# GD2.net
KiCad netlist of a schematic drawn in Altium Designer
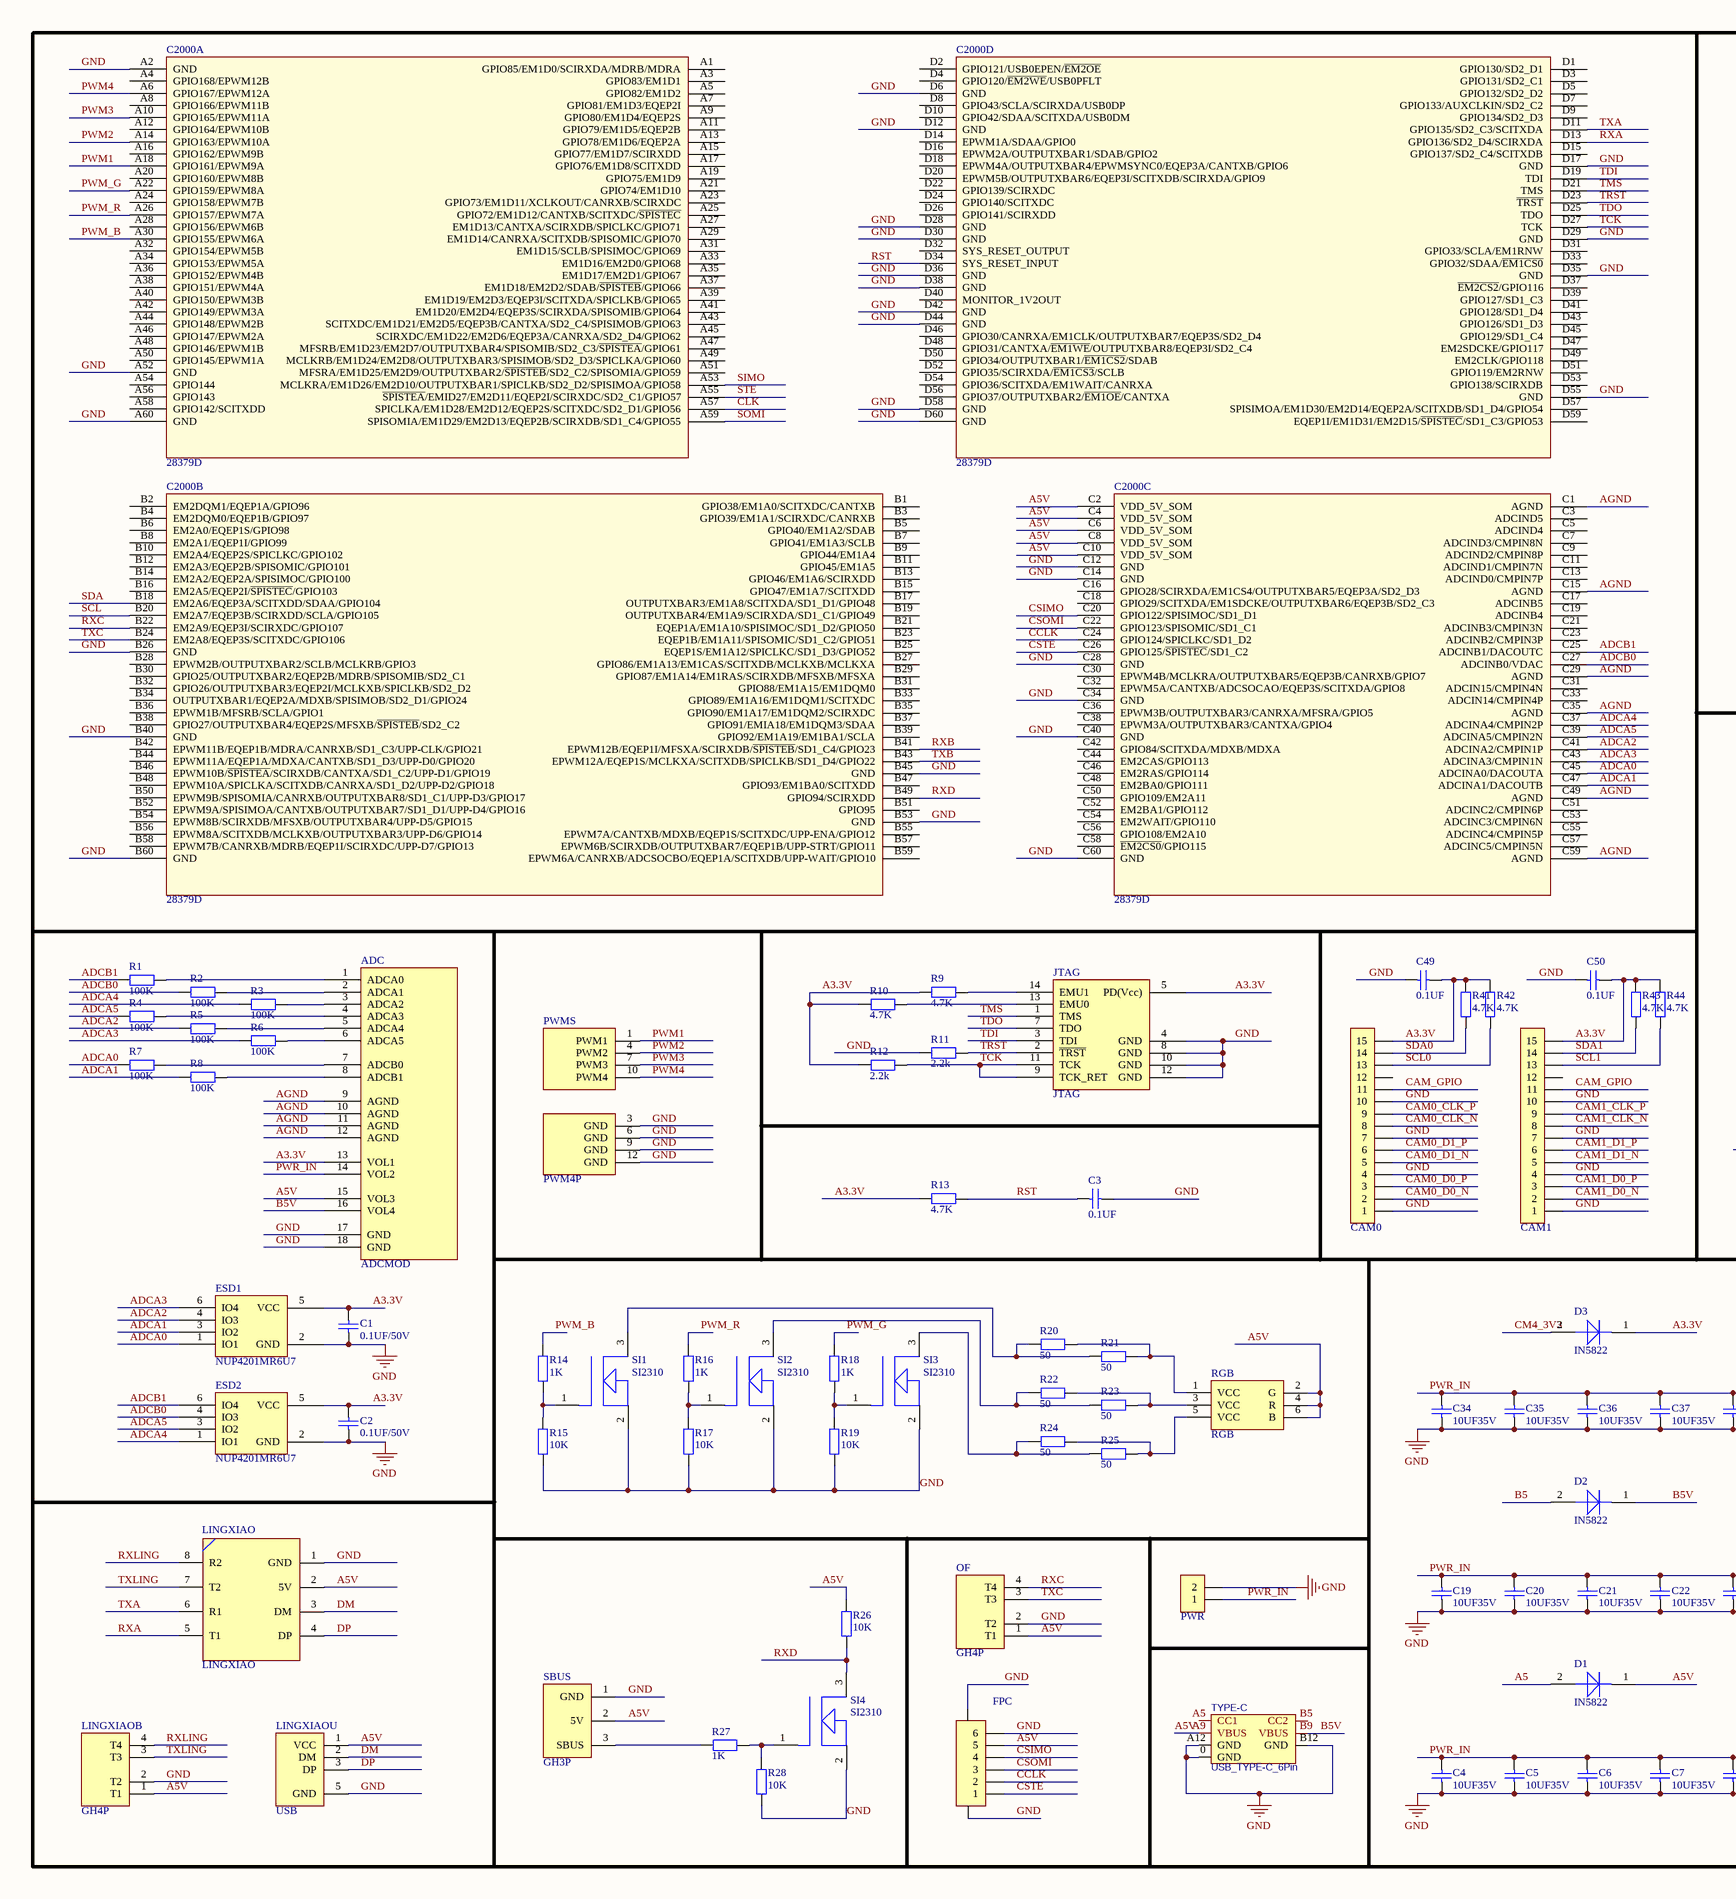
[diagram p0: GD2.SchDoc, left]
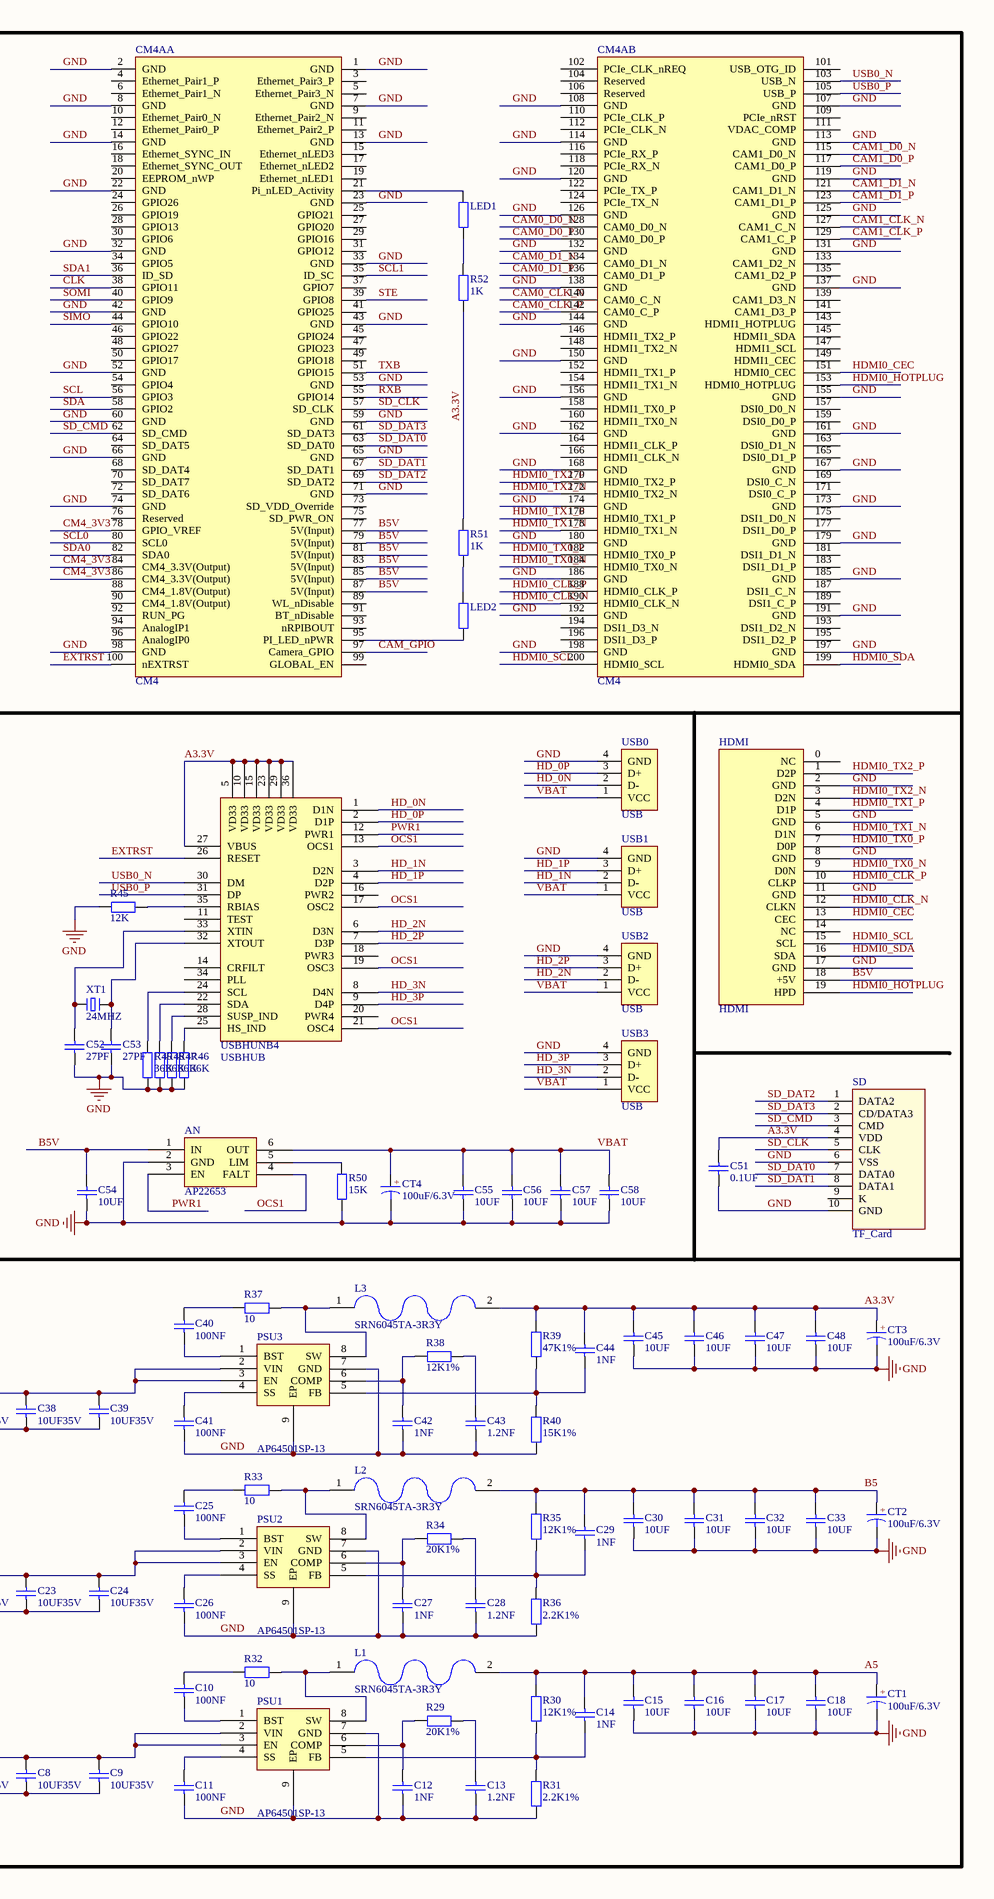
[diagram p1: GD2.SchDoc, right]

(export (version "E")
  (design (tool "Eeschema 10.0.6"))
  (components
    (comp (ref "ADC") (value "ADCMOD") (footprint "ADCMOD") (libsource (lib "LINGXIAO") (part "ADCMOD")))
    (comp (ref "AN") (value "AP22653") (footprint "SOT23-6") (libsource (lib "LINGXIAO") (part "AP22653")))
    (comp (ref "C1")
      (value "0.1UF/50V")
      (footprint "C0603_L")
      (description "贴片电容/MLCC电容")
      (libsource (lib "0.1 - 电阻-电容-电感-晶振-晶体-磁珠-电位器-法拉电容-馈通电容") (part "C"))
    )
    (comp (ref "C2")
      (value "0.1UF/50V")
      (footprint "C0603_L")
      (description "贴片电容/MLCC电容")
      (libsource (lib "0.1 - 电阻-电容-电感-晶振-晶体-磁珠-电位器-法拉电容-馈通电容") (part "C"))
    )
    (comp (ref "C3")
      (value "0.1UF")
      (footprint "C0603_L")
      (description "贴片电容/MLCC电容")
      (libsource (lib "0.1 - 电阻-电容-电感-晶振-晶体-磁珠-电位器-法拉电容-馈通电容") (part "C"))
    )
    (comp (ref "C4")
      (value "10UF35V")
      (footprint "C0603_L")
      (description "贴片电容/MLCC电容")
      (libsource (lib "0.1 - 电阻-电容-电感-晶振-晶体-磁珠-电位器-法拉电容-馈通电容") (part "C"))
    )
    (comp (ref "C5")
      (value "10UF35V")
      (footprint "C0603_L")
      (description "贴片电容/MLCC电容")
      (libsource (lib "0.1 - 电阻-电容-电感-晶振-晶体-磁珠-电位器-法拉电容-馈通电容") (part "C"))
    )
    (comp (ref "C6")
      (value "10UF35V")
      (footprint "C0603_L")
      (description "贴片电容/MLCC电容")
      (libsource (lib "0.1 - 电阻-电容-电感-晶振-晶体-磁珠-电位器-法拉电容-馈通电容") (part "C"))
    )
    (comp (ref "C7")
      (value "10UF35V")
      (footprint "C0603_L")
      (description "贴片电容/MLCC电容")
      (libsource (lib "0.1 - 电阻-电容-电感-晶振-晶体-磁珠-电位器-法拉电容-馈通电容") (part "C"))
    )
    (comp (ref "C8")
      (value "10UF35V")
      (footprint "C0603_L")
      (description "贴片电容/MLCC电容")
      (libsource (lib "0.1 - 电阻-电容-电感-晶振-晶体-磁珠-电位器-法拉电容-馈通电容") (part "C"))
    )
    (comp (ref "C9")
      (value "10UF35V")
      (footprint "C0603_L")
      (description "贴片电容/MLCC电容")
      (libsource (lib "0.1 - 电阻-电容-电感-晶振-晶体-磁珠-电位器-法拉电容-馈通电容") (part "C"))
    )
    (comp (ref "C10")
      (value "100NF")
      (footprint "C0603_L")
      (description "贴片电容/MLCC电容")
      (libsource (lib "0.1 - 电阻-电容-电感-晶振-晶体-磁珠-电位器-法拉电容-馈通电容") (part "C"))
    )
    (comp (ref "C11")
      (value "100NF")
      (footprint "C0603_L")
      (description "贴片电容/MLCC电容")
      (libsource (lib "0.1 - 电阻-电容-电感-晶振-晶体-磁珠-电位器-法拉电容-馈通电容") (part "C"))
    )
    (comp (ref "C12")
      (value "1NF")
      (footprint "C0603_L")
      (description "贴片电容/MLCC电容")
      (libsource (lib "0.1 - 电阻-电容-电感-晶振-晶体-磁珠-电位器-法拉电容-馈通电容") (part "C"))
    )
    (comp (ref "C13")
      (value "1.2NF")
      (footprint "C0603_L")
      (description "贴片电容/MLCC电容")
      (libsource (lib "0.1 - 电阻-电容-电感-晶振-晶体-磁珠-电位器-法拉电容-馈通电容") (part "C"))
    )
    (comp (ref "C14")
      (value "1NF")
      (footprint "C0603_L")
      (description "贴片电容/MLCC电容")
      (libsource (lib "0.1 - 电阻-电容-电感-晶振-晶体-磁珠-电位器-法拉电容-馈通电容") (part "C"))
    )
    (comp (ref "C15")
      (value "10UF")
      (footprint "C0603_L")
      (description "贴片电容/MLCC电容")
      (libsource (lib "0.1 - 电阻-电容-电感-晶振-晶体-磁珠-电位器-法拉电容-馈通电容") (part "C"))
    )
    (comp (ref "C16")
      (value "10UF")
      (footprint "C0603_L")
      (description "贴片电容/MLCC电容")
      (libsource (lib "0.1 - 电阻-电容-电感-晶振-晶体-磁珠-电位器-法拉电容-馈通电容") (part "C"))
    )
    (comp (ref "C17")
      (value "10UF")
      (footprint "C0603_L")
      (description "贴片电容/MLCC电容")
      (libsource (lib "0.1 - 电阻-电容-电感-晶振-晶体-磁珠-电位器-法拉电容-馈通电容") (part "C"))
    )
    (comp (ref "C18")
      (value "10UF")
      (footprint "C0603_L")
      (description "贴片电容/MLCC电容")
      (libsource (lib "0.1 - 电阻-电容-电感-晶振-晶体-磁珠-电位器-法拉电容-馈通电容") (part "C"))
    )
    (comp (ref "C19")
      (value "10UF35V")
      (footprint "C0603_L")
      (description "贴片电容/MLCC电容")
      (libsource (lib "0.1 - 电阻-电容-电感-晶振-晶体-磁珠-电位器-法拉电容-馈通电容") (part "C"))
    )
    (comp (ref "C20")
      (value "10UF35V")
      (footprint "C0603_L")
      (description "贴片电容/MLCC电容")
      (libsource (lib "0.1 - 电阻-电容-电感-晶振-晶体-磁珠-电位器-法拉电容-馈通电容") (part "C"))
    )
    (comp (ref "C21")
      (value "10UF35V")
      (footprint "C0603_L")
      (description "贴片电容/MLCC电容")
      (libsource (lib "0.1 - 电阻-电容-电感-晶振-晶体-磁珠-电位器-法拉电容-馈通电容") (part "C"))
    )
    (comp (ref "C22")
      (value "10UF35V")
      (footprint "C0603_L")
      (description "贴片电容/MLCC电容")
      (libsource (lib "0.1 - 电阻-电容-电感-晶振-晶体-磁珠-电位器-法拉电容-馈通电容") (part "C"))
    )
    (comp (ref "C23")
      (value "10UF35V")
      (footprint "C0603_L")
      (description "贴片电容/MLCC电容")
      (libsource (lib "0.1 - 电阻-电容-电感-晶振-晶体-磁珠-电位器-法拉电容-馈通电容") (part "C"))
    )
    (comp (ref "C24")
      (value "10UF35V")
      (footprint "C0603_L")
      (description "贴片电容/MLCC电容")
      (libsource (lib "0.1 - 电阻-电容-电感-晶振-晶体-磁珠-电位器-法拉电容-馈通电容") (part "C"))
    )
    (comp (ref "C25")
      (value "100NF")
      (footprint "C0603_L")
      (description "贴片电容/MLCC电容")
      (libsource (lib "0.1 - 电阻-电容-电感-晶振-晶体-磁珠-电位器-法拉电容-馈通电容") (part "C"))
    )
    (comp (ref "C26")
      (value "100NF")
      (footprint "C0603_L")
      (description "贴片电容/MLCC电容")
      (libsource (lib "0.1 - 电阻-电容-电感-晶振-晶体-磁珠-电位器-法拉电容-馈通电容") (part "C"))
    )
    (comp (ref "C27")
      (value "1NF")
      (footprint "C0603_L")
      (description "贴片电容/MLCC电容")
      (libsource (lib "0.1 - 电阻-电容-电感-晶振-晶体-磁珠-电位器-法拉电容-馈通电容") (part "C"))
    )
    (comp (ref "C28")
      (value "1.2NF")
      (footprint "C0603_L")
      (description "贴片电容/MLCC电容")
      (libsource (lib "0.1 - 电阻-电容-电感-晶振-晶体-磁珠-电位器-法拉电容-馈通电容") (part "C"))
    )
    (comp (ref "C29")
      (value "1NF")
      (footprint "C0603_L")
      (description "贴片电容/MLCC电容")
      (libsource (lib "0.1 - 电阻-电容-电感-晶振-晶体-磁珠-电位器-法拉电容-馈通电容") (part "C"))
    )
    (comp (ref "C30")
      (value "10UF")
      (footprint "C0603_L")
      (description "贴片电容/MLCC电容")
      (libsource (lib "0.1 - 电阻-电容-电感-晶振-晶体-磁珠-电位器-法拉电容-馈通电容") (part "C"))
    )
    (comp (ref "C31")
      (value "10UF")
      (footprint "C0603_L")
      (description "贴片电容/MLCC电容")
      (libsource (lib "0.1 - 电阻-电容-电感-晶振-晶体-磁珠-电位器-法拉电容-馈通电容") (part "C"))
    )
    (comp (ref "C32")
      (value "10UF")
      (footprint "C0603_L")
      (description "贴片电容/MLCC电容")
      (libsource (lib "0.1 - 电阻-电容-电感-晶振-晶体-磁珠-电位器-法拉电容-馈通电容") (part "C"))
    )
    (comp (ref "C33")
      (value "10UF")
      (footprint "C0603_L")
      (description "贴片电容/MLCC电容")
      (libsource (lib "0.1 - 电阻-电容-电感-晶振-晶体-磁珠-电位器-法拉电容-馈通电容") (part "C"))
    )
    (comp (ref "C34")
      (value "10UF35V")
      (footprint "C0603_L")
      (description "贴片电容/MLCC电容")
      (libsource (lib "0.1 - 电阻-电容-电感-晶振-晶体-磁珠-电位器-法拉电容-馈通电容") (part "C"))
    )
    (comp (ref "C35")
      (value "10UF35V")
      (footprint "C0603_L")
      (description "贴片电容/MLCC电容")
      (libsource (lib "0.1 - 电阻-电容-电感-晶振-晶体-磁珠-电位器-法拉电容-馈通电容") (part "C"))
    )
    (comp (ref "C36")
      (value "10UF35V")
      (footprint "C0603_L")
      (description "贴片电容/MLCC电容")
      (libsource (lib "0.1 - 电阻-电容-电感-晶振-晶体-磁珠-电位器-法拉电容-馈通电容") (part "C"))
    )
    (comp (ref "C37")
      (value "10UF35V")
      (footprint "C0603_L")
      (description "贴片电容/MLCC电容")
      (libsource (lib "0.1 - 电阻-电容-电感-晶振-晶体-磁珠-电位器-法拉电容-馈通电容") (part "C"))
    )
    (comp (ref "C38")
      (value "10UF35V")
      (footprint "C0603_L")
      (description "贴片电容/MLCC电容")
      (libsource (lib "0.1 - 电阻-电容-电感-晶振-晶体-磁珠-电位器-法拉电容-馈通电容") (part "C"))
    )
    (comp (ref "C39")
      (value "10UF35V")
      (footprint "C0603_L")
      (description "贴片电容/MLCC电容")
      (libsource (lib "0.1 - 电阻-电容-电感-晶振-晶体-磁珠-电位器-法拉电容-馈通电容") (part "C"))
    )
    (comp (ref "C40")
      (value "100NF")
      (footprint "C0603_L")
      (description "贴片电容/MLCC电容")
      (libsource (lib "0.1 - 电阻-电容-电感-晶振-晶体-磁珠-电位器-法拉电容-馈通电容") (part "C"))
    )
    (comp (ref "C41")
      (value "100NF")
      (footprint "C0603_L")
      (description "贴片电容/MLCC电容")
      (libsource (lib "0.1 - 电阻-电容-电感-晶振-晶体-磁珠-电位器-法拉电容-馈通电容") (part "C"))
    )
    (comp (ref "C42")
      (value "1NF")
      (footprint "C0603_L")
      (description "贴片电容/MLCC电容")
      (libsource (lib "0.1 - 电阻-电容-电感-晶振-晶体-磁珠-电位器-法拉电容-馈通电容") (part "C"))
    )
    (comp (ref "C43")
      (value "1.2NF")
      (footprint "C0603_L")
      (description "贴片电容/MLCC电容")
      (libsource (lib "0.1 - 电阻-电容-电感-晶振-晶体-磁珠-电位器-法拉电容-馈通电容") (part "C"))
    )
    (comp (ref "C44")
      (value "1NF")
      (footprint "C0603_L")
      (description "贴片电容/MLCC电容")
      (libsource (lib "0.1 - 电阻-电容-电感-晶振-晶体-磁珠-电位器-法拉电容-馈通电容") (part "C"))
    )
    (comp (ref "C45")
      (value "10UF")
      (footprint "C0603_L")
      (description "贴片电容/MLCC电容")
      (libsource (lib "0.1 - 电阻-电容-电感-晶振-晶体-磁珠-电位器-法拉电容-馈通电容") (part "C"))
    )
    (comp (ref "C46")
      (value "10UF")
      (footprint "C0603_L")
      (description "贴片电容/MLCC电容")
      (libsource (lib "0.1 - 电阻-电容-电感-晶振-晶体-磁珠-电位器-法拉电容-馈通电容") (part "C"))
    )
    (comp (ref "C47")
      (value "10UF")
      (footprint "C0603_L")
      (description "贴片电容/MLCC电容")
      (libsource (lib "0.1 - 电阻-电容-电感-晶振-晶体-磁珠-电位器-法拉电容-馈通电容") (part "C"))
    )
    (comp (ref "C48")
      (value "10UF")
      (footprint "C0603_L")
      (description "贴片电容/MLCC电容")
      (libsource (lib "0.1 - 电阻-电容-电感-晶振-晶体-磁珠-电位器-法拉电容-馈通电容") (part "C"))
    )
    (comp (ref "C49")
      (value "0.1UF")
      (footprint "C0603_L")
      (description "贴片电容/MLCC电容")
      (libsource (lib "0.1 - 电阻-电容-电感-晶振-晶体-磁珠-电位器-法拉电容-馈通电容") (part "C"))
    )
    (comp (ref "C50")
      (value "0.1UF")
      (footprint "C0603_L")
      (description "贴片电容/MLCC电容")
      (libsource (lib "0.1 - 电阻-电容-电感-晶振-晶体-磁珠-电位器-法拉电容-馈通电容") (part "C"))
    )
    (comp (ref "C51")
      (value "0.1UF")
      (footprint "C0603_L")
      (description "贴片电容/MLCC电容")
      (libsource (lib "0.1 - 电阻-电容-电感-晶振-晶体-磁珠-电位器-法拉电容-馈通电容") (part "C"))
    )
    (comp (ref "C52")
      (value "27PF")
      (footprint "C0603_L")
      (description "贴片电容/MLCC电容")
      (libsource (lib "0.1 - 电阻-电容-电感-晶振-晶体-磁珠-电位器-法拉电容-馈通电容") (part "C"))
    )
    (comp (ref "C53")
      (value "27PF")
      (footprint "C0603_L")
      (description "贴片电容/MLCC电容")
      (libsource (lib "0.1 - 电阻-电容-电感-晶振-晶体-磁珠-电位器-法拉电容-馈通电容") (part "C"))
    )
    (comp (ref "C54")
      (value "10UF")
      (footprint "C0603_L")
      (description "贴片电容/MLCC电容")
      (libsource (lib "0.1 - 电阻-电容-电感-晶振-晶体-磁珠-电位器-法拉电容-馈通电容") (part "C"))
    )
    (comp (ref "C55")
      (value "10UF")
      (footprint "C0603_L")
      (description "贴片电容/MLCC电容")
      (libsource (lib "0.1 - 电阻-电容-电感-晶振-晶体-磁珠-电位器-法拉电容-馈通电容") (part "C"))
    )
    (comp (ref "C56")
      (value "10UF")
      (footprint "C0603_L")
      (description "贴片电容/MLCC电容")
      (libsource (lib "0.1 - 电阻-电容-电感-晶振-晶体-磁珠-电位器-法拉电容-馈通电容") (part "C"))
    )
    (comp (ref "C57")
      (value "10UF")
      (footprint "C0603_L")
      (description "贴片电容/MLCC电容")
      (libsource (lib "0.1 - 电阻-电容-电感-晶振-晶体-磁珠-电位器-法拉电容-馈通电容") (part "C"))
    )
    (comp (ref "C58")
      (value "10UF")
      (footprint "C0603_L")
      (description "贴片电容/MLCC电容")
      (libsource (lib "0.1 - 电阻-电容-电感-晶振-晶体-磁珠-电位器-法拉电容-馈通电容") (part "C"))
    )
    (comp (ref "C2000") (value "28379D") (footprint "28379D") (libsource (lib "LINGXIAO") (part "28379D")))
    (comp (ref "CAM0")
      (value "CON-15P")
      (footprint "FPC1.0-WT-15P")
      (description "15P连接器")
      (libsource (lib "5.0 - 1.00mm连接器(FPC1.0_SH1.0_1.0排针排母)") (part "Header 15"))
    )
    (comp (ref "CAM1")
      (value "CON-15P")
      (footprint "FPC1.0-WT-15P")
      (description "15P连接器")
      (libsource (lib "5.0 - 1.00mm连接器(FPC1.0_SH1.0_1.0排针排母)") (part "Header 15"))
    )
    (comp (ref "CM4A") (value "CM4") (footprint "CM4") (libsource (lib "LINGXIAO") (part "CM4")))
    (comp (ref "CT1")
      (value "100uF/6.3V")
      (footprint "C_3216")
      (description "贴片钽电容")
      (libsource (lib "0.1 - 电阻-电容-电感-晶振-晶体-磁珠-电位器-法拉电容-馈通电容") (part "CT"))
    )
    (comp (ref "CT2")
      (value "100uF/6.3V")
      (footprint "C_3216")
      (description "贴片钽电容")
      (libsource (lib "0.1 - 电阻-电容-电感-晶振-晶体-磁珠-电位器-法拉电容-馈通电容") (part "CT"))
    )
    (comp (ref "CT3")
      (value "100uF/6.3V")
      (footprint "C_3216")
      (description "贴片钽电容")
      (libsource (lib "0.1 - 电阻-电容-电感-晶振-晶体-磁珠-电位器-法拉电容-馈通电容") (part "CT"))
    )
    (comp (ref "CT4")
      (value "100uF/6.3V")
      (footprint "C_3216")
      (description "贴片钽电容")
      (libsource (lib "0.1 - 电阻-电容-电感-晶振-晶体-磁珠-电位器-法拉电容-馈通电容") (part "CT"))
    )
    (comp (ref "D1") (value "IN5822") (footprint "IN5819") (libsource (lib "LINGXIAO") (part "IN5819")))
    (comp (ref "D2") (value "IN5822") (footprint "IN5819") (libsource (lib "LINGXIAO") (part "IN5819")))
    (comp (ref "D3") (value "IN5822") (footprint "IN5819") (libsource (lib "LINGXIAO") (part "IN5819")))
    (comp (ref "ESD1")
      (value "NUP4201MR6U7")
      (footprint "TSOP-6")
      (libsource (lib "LINGXIAO") (part "NUP4201MR6U7"))
    )
    (comp (ref "ESD2")
      (value "NUP4201MR6U7")
      (footprint "TSOP-6")
      (libsource (lib "LINGXIAO") (part "NUP4201MR6U7"))
    )
    (comp (ref "FPC")
      (value "CON-6P")
      (footprint "FPC1.0-WT-6P")
      (description "6P连接器")
      (libsource (lib "5.0 - 1.00mm连接器(FPC1.0_SH1.0_1.0排针排母)") (part "Header 6"))
    )
    (comp (ref "HDMI") (value "HDMI") (footprint "HDMI_A") (libsource (lib "LINGXIAO") (part "HDMI")))
    (comp (ref "JTAG") (value "JTAG") (footprint "JTAG") (libsource (lib "LINGXIAO") (part "JTAG")))
    (comp (ref "L1")
      (value "SRN6045TA-3R3Y")
      (footprint "CD42")
      (libsource (lib "LINGXIAO") (part "SRN6045TA-3R3Y"))
    )
    (comp (ref "L2")
      (value "SRN6045TA-3R3Y")
      (footprint "CD42")
      (libsource (lib "LINGXIAO") (part "SRN6045TA-3R3Y"))
    )
    (comp (ref "L3")
      (value "SRN6045TA-3R3Y")
      (footprint "CD42")
      (libsource (lib "LINGXIAO") (part "SRN6045TA-3R3Y"))
    )
    (comp (ref "LED1")
      (value "~")
      (footprint "R0805_L")
      (description "贴片电阻")
      (libsource (lib "0.1 - 电阻-电容-电感-晶振-晶体-磁珠-电位器-法拉电容-馈通电容") (part "R"))
    )
    (comp (ref "LED2")
      (value "~")
      (footprint "R0805_L")
      (description "贴片电阻")
      (libsource (lib "0.1 - 电阻-电容-电感-晶振-晶体-磁珠-电位器-法拉电容-馈通电容") (part "R"))
    )
    (comp (ref "LINGXIAO")
      (value "LINGXIAO")
      (footprint "LINGXIAO")
      (libsource (lib "LINGXIAO") (part "LINGXIAO"))
    )
    (comp (ref "LINGXIAOB") (value "GH4P") (footprint "GH4P") (libsource (lib "LINGXIAO") (part "GH4P")))
    (comp (ref "LINGXIAOU") (value "USB") (footprint "USB") (libsource (lib "LINGXIAO") (part "USB")))
    (comp (ref "OF") (value "GH4P") (footprint "GH4P") (libsource (lib "LINGXIAO") (part "GH4P")))
    (comp (ref "PSU1")
      (value "AP64501SP-13")
      (footprint "SOIP-8")
      (libsource (lib "LINGXIAO") (part "AP64501SP-13"))
    )
    (comp (ref "PSU2")
      (value "AP64501SP-13")
      (footprint "SOIP-8")
      (libsource (lib "LINGXIAO") (part "AP64501SP-13"))
    )
    (comp (ref "PSU3")
      (value "AP64501SP-13")
      (footprint "SOIP-8")
      (libsource (lib "LINGXIAO") (part "AP64501SP-13"))
    )
    (comp (ref "PWMS") (value "PWM4P") (footprint "PWM4P") (libsource (lib "LINGXIAO") (part "PWM4P")))
    (comp (ref "PWR")
      (value "HDR-1X2")
      (footprint "KF2EDGK5.08-WI-2P")
      (description "2P接插件")
      (libsource (lib "6.1 - 5.08mm连接器(KF2EDGK5.08)") (part "Header 2"))
    )
    (comp (ref "R1")
      (value "100K")
      (footprint "R0603_L")
      (description "贴片电阻")
      (libsource (lib "0.1 - 电阻-电容-电感-晶振-晶体-磁珠-电位器-法拉电容-馈通电容") (part "R"))
    )
    (comp (ref "R2")
      (value "100K")
      (footprint "R0603_L")
      (description "贴片电阻")
      (libsource (lib "0.1 - 电阻-电容-电感-晶振-晶体-磁珠-电位器-法拉电容-馈通电容") (part "R"))
    )
    (comp (ref "R3")
      (value "100K")
      (footprint "R0603_L")
      (description "贴片电阻")
      (libsource (lib "0.1 - 电阻-电容-电感-晶振-晶体-磁珠-电位器-法拉电容-馈通电容") (part "R"))
    )
    (comp (ref "R4")
      (value "100K")
      (footprint "R0603_L")
      (description "贴片电阻")
      (libsource (lib "0.1 - 电阻-电容-电感-晶振-晶体-磁珠-电位器-法拉电容-馈通电容") (part "R"))
    )
    (comp (ref "R5")
      (value "100K")
      (footprint "R0603_L")
      (description "贴片电阻")
      (libsource (lib "0.1 - 电阻-电容-电感-晶振-晶体-磁珠-电位器-法拉电容-馈通电容") (part "R"))
    )
    (comp (ref "R6")
      (value "100K")
      (footprint "R0603_L")
      (description "贴片电阻")
      (libsource (lib "0.1 - 电阻-电容-电感-晶振-晶体-磁珠-电位器-法拉电容-馈通电容") (part "R"))
    )
    (comp (ref "R7")
      (value "100K")
      (footprint "R0603_L")
      (description "贴片电阻")
      (libsource (lib "0.1 - 电阻-电容-电感-晶振-晶体-磁珠-电位器-法拉电容-馈通电容") (part "R"))
    )
    (comp (ref "R8")
      (value "100K")
      (footprint "R0603_L")
      (description "贴片电阻")
      (libsource (lib "0.1 - 电阻-电容-电感-晶振-晶体-磁珠-电位器-法拉电容-馈通电容") (part "R"))
    )
    (comp (ref "R9")
      (value "4.7K")
      (footprint "R0603_L")
      (description "贴片电阻")
      (libsource (lib "0.1 - 电阻-电容-电感-晶振-晶体-磁珠-电位器-法拉电容-馈通电容") (part "R"))
    )
    (comp (ref "R10")
      (value "4.7K")
      (footprint "R0603_L")
      (description "贴片电阻")
      (libsource (lib "0.1 - 电阻-电容-电感-晶振-晶体-磁珠-电位器-法拉电容-馈通电容") (part "R"))
    )
    (comp (ref "R11")
      (value "2.2k")
      (footprint "R0603_L")
      (description "贴片电阻")
      (libsource (lib "0.1 - 电阻-电容-电感-晶振-晶体-磁珠-电位器-法拉电容-馈通电容") (part "R"))
    )
    (comp (ref "R12")
      (value "2.2k")
      (footprint "R0603_L")
      (description "贴片电阻")
      (libsource (lib "0.1 - 电阻-电容-电感-晶振-晶体-磁珠-电位器-法拉电容-馈通电容") (part "R"))
    )
    (comp (ref "R13")
      (value "4.7K")
      (footprint "R0603_L")
      (description "贴片电阻")
      (libsource (lib "0.1 - 电阻-电容-电感-晶振-晶体-磁珠-电位器-法拉电容-馈通电容") (part "R"))
    )
    (comp (ref "R14")
      (value "1K")
      (footprint "R0603_L")
      (description "贴片电阻")
      (libsource (lib "0.1 - 电阻-电容-电感-晶振-晶体-磁珠-电位器-法拉电容-馈通电容") (part "R"))
    )
    (comp (ref "R15")
      (value "10K")
      (footprint "R0603_L")
      (description "贴片电阻")
      (libsource (lib "0.1 - 电阻-电容-电感-晶振-晶体-磁珠-电位器-法拉电容-馈通电容") (part "R"))
    )
    (comp (ref "R16")
      (value "1K")
      (footprint "R0603_L")
      (description "贴片电阻")
      (libsource (lib "0.1 - 电阻-电容-电感-晶振-晶体-磁珠-电位器-法拉电容-馈通电容") (part "R"))
    )
    (comp (ref "R17")
      (value "10K")
      (footprint "R0603_L")
      (description "贴片电阻")
      (libsource (lib "0.1 - 电阻-电容-电感-晶振-晶体-磁珠-电位器-法拉电容-馈通电容") (part "R"))
    )
    (comp (ref "R18")
      (value "1K")
      (footprint "R0603_L")
      (description "贴片电阻")
      (libsource (lib "0.1 - 电阻-电容-电感-晶振-晶体-磁珠-电位器-法拉电容-馈通电容") (part "R"))
    )
    (comp (ref "R19")
      (value "10K")
      (footprint "R0603_L")
      (description "贴片电阻")
      (libsource (lib "0.1 - 电阻-电容-电感-晶振-晶体-磁珠-电位器-法拉电容-馈通电容") (part "R"))
    )
    (comp (ref "R20")
      (value "50")
      (footprint "R0603_L")
      (description "贴片电阻")
      (libsource (lib "0.1 - 电阻-电容-电感-晶振-晶体-磁珠-电位器-法拉电容-馈通电容") (part "R"))
    )
    (comp (ref "R21")
      (value "50")
      (footprint "R0603_L")
      (description "贴片电阻")
      (libsource (lib "0.1 - 电阻-电容-电感-晶振-晶体-磁珠-电位器-法拉电容-馈通电容") (part "R"))
    )
    (comp (ref "R22")
      (value "50")
      (footprint "R0603_L")
      (description "贴片电阻")
      (libsource (lib "0.1 - 电阻-电容-电感-晶振-晶体-磁珠-电位器-法拉电容-馈通电容") (part "R"))
    )
    (comp (ref "R23")
      (value "50")
      (footprint "R0603_L")
      (description "贴片电阻")
      (libsource (lib "0.1 - 电阻-电容-电感-晶振-晶体-磁珠-电位器-法拉电容-馈通电容") (part "R"))
    )
    (comp (ref "R24")
      (value "50")
      (footprint "R0603_L")
      (description "贴片电阻")
      (libsource (lib "0.1 - 电阻-电容-电感-晶振-晶体-磁珠-电位器-法拉电容-馈通电容") (part "R"))
    )
    (comp (ref "R25")
      (value "50")
      (footprint "R0603_L")
      (description "贴片电阻")
      (libsource (lib "0.1 - 电阻-电容-电感-晶振-晶体-磁珠-电位器-法拉电容-馈通电容") (part "R"))
    )
    (comp (ref "R26")
      (value "10K")
      (footprint "R0603_L")
      (description "贴片电阻")
      (libsource (lib "0.1 - 电阻-电容-电感-晶振-晶体-磁珠-电位器-法拉电容-馈通电容") (part "R"))
    )
    (comp (ref "R27")
      (value "1K")
      (footprint "R0603_L")
      (description "贴片电阻")
      (libsource (lib "0.1 - 电阻-电容-电感-晶振-晶体-磁珠-电位器-法拉电容-馈通电容") (part "R"))
    )
    (comp (ref "R28")
      (value "10K")
      (footprint "R0603_L")
      (description "贴片电阻")
      (libsource (lib "0.1 - 电阻-电容-电感-晶振-晶体-磁珠-电位器-法拉电容-馈通电容") (part "R"))
    )
    (comp (ref "R29")
      (value "20K1%")
      (footprint "R0603_L")
      (description "贴片电阻")
      (libsource (lib "0.1 - 电阻-电容-电感-晶振-晶体-磁珠-电位器-法拉电容-馈通电容") (part "R"))
    )
    (comp (ref "R30")
      (value "12K1%")
      (footprint "R0603_L")
      (description "贴片电阻")
      (libsource (lib "0.1 - 电阻-电容-电感-晶振-晶体-磁珠-电位器-法拉电容-馈通电容") (part "R"))
    )
    (comp (ref "R31")
      (value "2.2K1%")
      (footprint "R0603_L")
      (description "贴片电阻")
      (libsource (lib "0.1 - 电阻-电容-电感-晶振-晶体-磁珠-电位器-法拉电容-馈通电容") (part "R"))
    )
    (comp (ref "R32")
      (value "10")
      (footprint "R0603_L")
      (description "贴片电阻")
      (libsource (lib "0.1 - 电阻-电容-电感-晶振-晶体-磁珠-电位器-法拉电容-馈通电容") (part "R"))
    )
    (comp (ref "R33")
      (value "10")
      (footprint "R0603_L")
      (description "贴片电阻")
      (libsource (lib "0.1 - 电阻-电容-电感-晶振-晶体-磁珠-电位器-法拉电容-馈通电容") (part "R"))
    )
    (comp (ref "R34")
      (value "20K1%")
      (footprint "R0603_L")
      (description "贴片电阻")
      (libsource (lib "0.1 - 电阻-电容-电感-晶振-晶体-磁珠-电位器-法拉电容-馈通电容") (part "R"))
    )
    (comp (ref "R35")
      (value "12K1%")
      (footprint "R0603_L")
      (description "贴片电阻")
      (libsource (lib "0.1 - 电阻-电容-电感-晶振-晶体-磁珠-电位器-法拉电容-馈通电容") (part "R"))
    )
    (comp (ref "R36")
      (value "2.2K1%")
      (footprint "R0603_L")
      (description "贴片电阻")
      (libsource (lib "0.1 - 电阻-电容-电感-晶振-晶体-磁珠-电位器-法拉电容-馈通电容") (part "R"))
    )
    (comp (ref "R37")
      (value "10")
      (footprint "R0603_L")
      (description "贴片电阻")
      (libsource (lib "0.1 - 电阻-电容-电感-晶振-晶体-磁珠-电位器-法拉电容-馈通电容") (part "R"))
    )
    (comp (ref "R38")
      (value "12K1%")
      (footprint "R0603_L")
      (description "贴片电阻")
      (libsource (lib "0.1 - 电阻-电容-电感-晶振-晶体-磁珠-电位器-法拉电容-馈通电容") (part "R"))
    )
    (comp (ref "R39")
      (value "47K1%")
      (footprint "R0603_L")
      (description "贴片电阻")
      (libsource (lib "0.1 - 电阻-电容-电感-晶振-晶体-磁珠-电位器-法拉电容-馈通电容") (part "R"))
    )
    (comp (ref "R40")
      (value "15K1%")
      (footprint "R0603_L")
      (description "贴片电阻")
      (libsource (lib "0.1 - 电阻-电容-电感-晶振-晶体-磁珠-电位器-法拉电容-馈通电容") (part "R"))
    )
    (comp (ref "R41")
      (value "4.7K")
      (footprint "R0603_L")
      (description "贴片电阻")
      (libsource (lib "0.1 - 电阻-电容-电感-晶振-晶体-磁珠-电位器-法拉电容-馈通电容") (part "R"))
    )
    (comp (ref "R42")
      (value "4.7K")
      (footprint "R0603_L")
      (description "贴片电阻")
      (libsource (lib "0.1 - 电阻-电容-电感-晶振-晶体-磁珠-电位器-法拉电容-馈通电容") (part "R"))
    )
    (comp (ref "R43")
      (value "4.7K")
      (footprint "R0603_L")
      (description "贴片电阻")
      (libsource (lib "0.1 - 电阻-电容-电感-晶振-晶体-磁珠-电位器-法拉电容-馈通电容") (part "R"))
    )
    (comp (ref "R44")
      (value "4.7K")
      (footprint "R0603_L")
      (description "贴片电阻")
      (libsource (lib "0.1 - 电阻-电容-电感-晶振-晶体-磁珠-电位器-法拉电容-馈通电容") (part "R"))
    )
    (comp (ref "R45")
      (value "12K")
      (footprint "R0603_L")
      (description "贴片电阻")
      (libsource (lib "0.1 - 电阻-电容-电感-晶振-晶体-磁珠-电位器-法拉电容-馈通电容") (part "R"))
    )
    (comp (ref "R46")
      (value "36K")
      (footprint "R0603_L")
      (description "贴片电阻")
      (libsource (lib "0.1 - 电阻-电容-电感-晶振-晶体-磁珠-电位器-法拉电容-馈通电容") (part "R"))
    )
    (comp (ref "R47")
      (value "36K")
      (footprint "R0603_L")
      (description "贴片电阻")
      (libsource (lib "0.1 - 电阻-电容-电感-晶振-晶体-磁珠-电位器-法拉电容-馈通电容") (part "R"))
    )
    (comp (ref "R48")
      (value "36K")
      (footprint "R0603_L")
      (description "贴片电阻")
      (libsource (lib "0.1 - 电阻-电容-电感-晶振-晶体-磁珠-电位器-法拉电容-馈通电容") (part "R"))
    )
    (comp (ref "R49")
      (value "36K")
      (footprint "R0603_L")
      (description "贴片电阻")
      (libsource (lib "0.1 - 电阻-电容-电感-晶振-晶体-磁珠-电位器-法拉电容-馈通电容") (part "R"))
    )
    (comp (ref "R50")
      (value "15K")
      (footprint "R0603_L")
      (description "贴片电阻")
      (libsource (lib "0.1 - 电阻-电容-电感-晶振-晶体-磁珠-电位器-法拉电容-馈通电容") (part "R"))
    )
    (comp (ref "R51")
      (value "1K")
      (footprint "R0603_L")
      (description "贴片电阻")
      (libsource (lib "0.1 - 电阻-电容-电感-晶振-晶体-磁珠-电位器-法拉电容-馈通电容") (part "R"))
    )
    (comp (ref "R52")
      (value "1K")
      (footprint "R0603_L")
      (description "贴片电阻")
      (libsource (lib "0.1 - 电阻-电容-电感-晶振-晶体-磁珠-电位器-法拉电容-馈通电容") (part "R"))
    )
    (comp (ref "RGB") (value "RGB") (footprint "RGB") (libsource (lib "LINGXIAO") (part "RGB")))
    (comp (ref "SBUS") (value "GH3P") (footprint "GH3P") (libsource (lib "LINGXIAO") (part "GH3P")))
    (comp (ref "SD")
      (value "TF_Card")
      (footprint "Micro SD")
      (description "TF卡座")
      (libsource (lib "0.6 - 电源_RJ45以太网_音频_SD-TF_SIM_ USB Type-C_HDMI插座") (part "TF_Card"))
    )
    (comp (ref "SI1") (value "SI2310") (footprint "SI2310") (libsource (lib "LINGXIAO") (part "SI2310")))
    (comp (ref "SI2") (value "SI2310") (footprint "SI2310") (libsource (lib "LINGXIAO") (part "SI2310")))
    (comp (ref "SI3") (value "SI2310") (footprint "SI2310") (libsource (lib "LINGXIAO") (part "SI2310")))
    (comp (ref "SI4") (value "SI2310") (footprint "SI2310") (libsource (lib "LINGXIAO") (part "SI2310")))
    (comp (ref "TYPE-C")
      (value "USB_TYPE-C_6Pin")
      (footprint "USB-C-SMD_6P")
      (description "USB_TYPE-C_6Pin母座")
      (libsource (lib "0.6 - 电源_RJ45以太网_音频_SD-TF_SIM_ USB Type-C_HDMI插座") (part "USB_TYPE-C_6Pin"))
    )
    (comp (ref "USB0")
      (value "USB")
      (footprint "USB2.0_Type-A_DIP_F_1")
      (description "USB2.0_Type-A母座")
      (libsource (lib "0.6 - 电源_RJ45以太网_音频_SD-TF_SIM_ USB Type-C_HDMI插座") (part "USB2.0_Type-A_F"))
    )
    (comp (ref "USB1")
      (value "USB")
      (footprint "USB2.0_Type-A_DIP_F_1")
      (description "USB2.0_Type-A母座")
      (libsource (lib "0.6 - 电源_RJ45以太网_音频_SD-TF_SIM_ USB Type-C_HDMI插座") (part "USB2.0_Type-A_F"))
    )
    (comp (ref "USB2")
      (value "USB")
      (footprint "USB2.0_Type-A_DIP_F_1")
      (description "USB2.0_Type-A母座")
      (libsource (lib "0.6 - 电源_RJ45以太网_音频_SD-TF_SIM_ USB Type-C_HDMI插座") (part "USB2.0_Type-A_F"))
    )
    (comp (ref "USB3")
      (value "USB")
      (footprint "USB2.0_Type-A_DIP_F_1")
      (description "USB2.0_Type-A母座")
      (libsource (lib "0.6 - 电源_RJ45以太网_音频_SD-TF_SIM_ USB Type-C_HDMI插座") (part "USB2.0_Type-A_F"))
    )
    (comp (ref "USBHUNB4") (value "USBHUB") (footprint "QFN36") (libsource (lib "LINGXIAO") (part "USBHUB")))
    (comp (ref "XT1")
      (value "24MHZ")
      (footprint "XTAL-5032-2P")
      (description "2脚无源晶振(谐振器）")
      (libsource (lib "0.1 - 电阻-电容-电感-晶振-晶体-磁珠-电位器-法拉电容-馈通电容") (part "XTAL-2P"))
    )
  )
  (nets
    (net (code "1") (name "/A3.3V") (class "Default")
      (node (ref "ADC") (pin "13") (pinfunction "VOL1_13") (pintype "passive"))
      (node (ref "C1") (pin "2") (pinfunction "2_2") (pintype "passive"))
      (node (ref "C2") (pin "2") (pinfunction "2_2") (pintype "passive"))
      (node (ref "C44") (pin "2") (pinfunction "2_2") (pintype "passive"))
      (node (ref "C45") (pin "2") (pinfunction "2_2") (pintype "passive"))
      (node (ref "C46") (pin "2") (pinfunction "2_2") (pintype "passive"))
      (node (ref "C47") (pin "2") (pinfunction "2_2") (pintype "passive"))
      (node (ref "C48") (pin "2") (pinfunction "2_2") (pintype "passive"))
      (node (ref "C49") (pin "1") (pinfunction "1_1") (pintype "passive"))
      (node (ref "C50") (pin "1") (pinfunction "1_1") (pintype "passive"))
      (node (ref "C51") (pin "2") (pinfunction "2_2") (pintype "passive"))
      (node (ref "CAM0") (pin "15") (pinfunction "15_15") (pintype "passive"))
      (node (ref "CAM1") (pin "15") (pinfunction "15_15") (pintype "passive"))
      (node (ref "CT3") (pin "1") (pinfunction "A_1") (pintype "passive"))
      (node (ref "D3") (pin "1") (pinfunction "T1_1") (pintype "passive"))
      (node (ref "ESD1") (pin "5") (pinfunction "VCC_5") (pintype "passive"))
      (node (ref "ESD2") (pin "5") (pinfunction "VCC_5") (pintype "passive"))
      (node (ref "JTAG") (pin "5") (pinfunction "PD(Vcc)_5") (pintype "passive"))
      (node (ref "L3") (pin "2") (pinfunction "T3_2") (pintype "passive"))
      (node (ref "R10") (pin "1") (pinfunction "1_1") (pintype "passive"))
      (node (ref "R12") (pin "1") (pinfunction "1_1") (pintype "passive"))
      (node (ref "R13") (pin "2") (pinfunction "2_2") (pintype "passive"))
      (node (ref "R39") (pin "2") (pinfunction "2_2") (pintype "passive"))
      (node (ref "R41") (pin "2") (pinfunction "2_2") (pintype "passive"))
      (node (ref "R42") (pin "2") (pinfunction "2_2") (pintype "passive"))
      (node (ref "R43") (pin "2") (pinfunction "2_2") (pintype "passive"))
      (node (ref "R44") (pin "2") (pinfunction "2_2") (pintype "passive"))
      (node (ref "R51") (pin "2") (pinfunction "2_2") (pintype "passive"))
      (node (ref "R52") (pin "1") (pinfunction "1_1") (pintype "passive"))
      (node (ref "R9") (pin "1") (pinfunction "1_1") (pintype "passive"))
      (node (ref "SD") (pin "4") (pinfunction "VDD_4") (pintype "passive"))
      (node (ref "USBHUNB4") (pin "10") (pinfunction "VD33_10") (pintype "passive"))
      (node (ref "USBHUNB4") (pin "15") (pinfunction "VD33_15") (pintype "passive"))
      (node (ref "USBHUNB4") (pin "23") (pinfunction "VD33_23") (pintype "passive"))
      (node (ref "USBHUNB4") (pin "27") (pinfunction "VBUS_27") (pintype "passive"))
      (node (ref "USBHUNB4") (pin "29") (pinfunction "VD33_29") (pintype "passive"))
      (node (ref "USBHUNB4") (pin "36") (pinfunction "VD33_36") (pintype "passive"))
      (node (ref "USBHUNB4") (pin "5") (pinfunction "VD33_5") (pintype "passive"))
    )
    (net (code "2") (name "/A5") (class "Default")
      (node (ref "C14") (pin "2") (pinfunction "2_2") (pintype "passive"))
      (node (ref "C15") (pin "2") (pinfunction "2_2") (pintype "passive"))
      (node (ref "C16") (pin "2") (pinfunction "2_2") (pintype "passive"))
      (node (ref "C17") (pin "2") (pinfunction "2_2") (pintype "passive"))
      (node (ref "C18") (pin "2") (pinfunction "2_2") (pintype "passive"))
      (node (ref "CT1") (pin "1") (pinfunction "A_1") (pintype "passive"))
      (node (ref "D1") (pin "2") (pinfunction "T2_2") (pintype "passive"))
      (node (ref "L1") (pin "2") (pinfunction "T3_2") (pintype "passive"))
      (node (ref "R30") (pin "2") (pinfunction "2_2") (pintype "passive"))
    )
    (net (code "3") (name "/A5V") (class "Default")
      (node (ref "ADC") (pin "15") (pinfunction "VOL3_15") (pintype "passive"))
      (node (ref "C2000") (pin "C10") (pinfunction "VDD_5V_SOM_C10") (pintype "power_in"))
      (node (ref "C2000") (pin "C2") (pinfunction "VDD_5V_SOM_C2") (pintype "power_in"))
      (node (ref "C2000") (pin "C4") (pinfunction "VDD_5V_SOM_C4") (pintype "power_in"))
      (node (ref "C2000") (pin "C6") (pinfunction "VDD_5V_SOM_C6") (pintype "power_in"))
      (node (ref "C2000") (pin "C8") (pinfunction "VDD_5V_SOM_C8") (pintype "power_in"))
      (node (ref "D1") (pin "1") (pinfunction "T1_1") (pintype "passive"))
      (node (ref "FPC") (pin "5") (pinfunction "5_5") (pintype "passive"))
      (node (ref "LINGXIAO") (pin "2") (pinfunction "5V_2") (pintype "passive"))
      (node (ref "LINGXIAOB") (pin "1") (pinfunction "T1_1") (pintype "passive"))
      (node (ref "LINGXIAOU") (pin "1") (pinfunction "VCC_1") (pintype "passive"))
      (node (ref "OF") (pin "1") (pinfunction "T1_1") (pintype "passive"))
      (node (ref "R26") (pin "2") (pinfunction "2_2") (pintype "passive"))
      (node (ref "RGB") (pin "2") (pinfunction "G_2") (pintype "passive"))
      (node (ref "RGB") (pin "4") (pinfunction "R_4") (pintype "passive"))
      (node (ref "RGB") (pin "6") (pinfunction "B_6") (pintype "passive"))
      (node (ref "SBUS") (pin "2") (pinfunction "5V_2") (pintype "passive"))
      (node (ref "TYPE-C") (pin "A9") (pinfunction "VBUS_A9") (pintype "passive"))
    )
    (net (code "4") (name "/ADCA0") (class "Default")
      (node (ref "C2000") (pin "C45") (pinfunction "ADCINA0/DACOUTA_C45") (pintype "passive"))
      (node (ref "ESD1") (pin "1") (pinfunction "IO1_1") (pintype "passive"))
      (node (ref "R7") (pin "1") (pinfunction "1_1") (pintype "passive"))
    )
    (net (code "5") (name "/ADCA1") (class "Default")
      (node (ref "C2000") (pin "C47") (pinfunction "ADCINA1/DACOUTB_C47") (pintype "passive"))
      (node (ref "ESD1") (pin "3") (pinfunction "IO2_3") (pintype "passive"))
      (node (ref "R8") (pin "1") (pinfunction "1_1") (pintype "passive"))
    )
    (net (code "6") (name "/ADCA2") (class "Default")
      (node (ref "C2000") (pin "C41") (pinfunction "ADCINA2/CMPIN1P_C41") (pintype "passive"))
      (node (ref "ESD1") (pin "4") (pinfunction "IO3_4") (pintype "passive"))
      (node (ref "R5") (pin "1") (pinfunction "1_1") (pintype "passive"))
    )
    (net (code "7") (name "/ADCA3") (class "Default")
      (node (ref "C2000") (pin "C43") (pinfunction "ADCINA3/CMPIN1N_C43") (pintype "passive"))
      (node (ref "ESD1") (pin "6") (pinfunction "IO4_6") (pintype "passive"))
      (node (ref "R6") (pin "1") (pinfunction "1_1") (pintype "passive"))
    )
    (net (code "8") (name "/ADCA4") (class "Default")
      (node (ref "C2000") (pin "C37") (pinfunction "ADCINA4/CMPIN2P_C37") (pintype "passive"))
      (node (ref "ESD2") (pin "1") (pinfunction "IO1_1") (pintype "passive"))
      (node (ref "R3") (pin "1") (pinfunction "1_1") (pintype "passive"))
    )
    (net (code "9") (name "/ADCA5") (class "Default")
      (node (ref "C2000") (pin "C39") (pinfunction "ADCINA5/CMPIN2N_C39") (pintype "passive"))
      (node (ref "ESD2") (pin "3") (pinfunction "IO2_3") (pintype "passive"))
      (node (ref "R4") (pin "1") (pinfunction "1_1") (pintype "passive"))
    )
    (net (code "10") (name "/ADCB0") (class "Default")
      (node (ref "C2000") (pin "C27") (pinfunction "ADCINB0/VDAC_C27") (pintype "passive"))
      (node (ref "ESD2") (pin "4") (pinfunction "IO3_4") (pintype "passive"))
      (node (ref "R2") (pin "1") (pinfunction "1_1") (pintype "passive"))
    )
    (net (code "11") (name "/ADCB1") (class "Default")
      (node (ref "C2000") (pin "C25") (pinfunction "ADCINB1/DACOUTC_C25") (pintype "passive"))
      (node (ref "ESD2") (pin "6") (pinfunction "IO4_6") (pintype "passive"))
      (node (ref "R1") (pin "1") (pinfunction "1_1") (pintype "passive"))
    )
    (net (code "12") (name "/AGND") (class "Default")
      (node (ref "ADC") (pin "10") (pinfunction "AGND_10") (pintype "passive"))
      (node (ref "ADC") (pin "11") (pinfunction "AGND_11") (pintype "passive"))
      (node (ref "ADC") (pin "12") (pinfunction "AGND_12") (pintype "passive"))
      (node (ref "ADC") (pin "9") (pinfunction "AGND_9") (pintype "passive"))
      (node (ref "C2000") (pin "C1") (pinfunction "AGND_C1") (pintype "power_in"))
      (node (ref "C2000") (pin "C15") (pinfunction "AGND_C15") (pintype "power_in"))
      (node (ref "C2000") (pin "C29") (pinfunction "AGND_C29") (pintype "power_in"))
      (node (ref "C2000") (pin "C35") (pinfunction "AGND_C35") (pintype "power_in"))
      (node (ref "C2000") (pin "C49") (pinfunction "AGND_C49") (pintype "power_in"))
      (node (ref "C2000") (pin "C59") (pinfunction "AGND_C59") (pintype "power_in"))
    )
    (net (code "13") (name "/B5") (class "Default")
      (node (ref "C29") (pin "2") (pinfunction "2_2") (pintype "passive"))
      (node (ref "C30") (pin "2") (pinfunction "2_2") (pintype "passive"))
      (node (ref "C31") (pin "2") (pinfunction "2_2") (pintype "passive"))
      (node (ref "C32") (pin "2") (pinfunction "2_2") (pintype "passive"))
      (node (ref "C33") (pin "2") (pinfunction "2_2") (pintype "passive"))
      (node (ref "CT2") (pin "1") (pinfunction "A_1") (pintype "passive"))
      (node (ref "D2") (pin "2") (pinfunction "T2_2") (pintype "passive"))
      (node (ref "L2") (pin "2") (pinfunction "T3_2") (pintype "passive"))
      (node (ref "R35") (pin "2") (pinfunction "2_2") (pintype "passive"))
    )
    (net (code "14") (name "/B5V") (class "Default")
      (node (ref "ADC") (pin "16") (pinfunction "VOL4_16") (pintype "passive"))
      (node (ref "AN") (pin "1") (pinfunction "IN_1") (pintype "passive"))
      (node (ref "C54") (pin "2") (pinfunction "2_2") (pintype "passive"))
      (node (ref "CM4A") (pin "77") (pinfunction "5V(Input)_77") (pintype "passive"))
      (node (ref "CM4A") (pin "79") (pinfunction "5V(Input)_79") (pintype "passive"))
      (node (ref "CM4A") (pin "81") (pinfunction "5V(Input)_81") (pintype "passive"))
      (node (ref "CM4A") (pin "83") (pinfunction "5V(Input)_83") (pintype "passive"))
      (node (ref "CM4A") (pin "85") (pinfunction "5V(Input)_85") (pintype "passive"))
      (node (ref "CM4A") (pin "87") (pinfunction "5V(Input)_87") (pintype "passive"))
      (node (ref "D2") (pin "1") (pinfunction "T1_1") (pintype "passive"))
      (node (ref "HDMI") (pin "18") (pinfunction "+5V_18") (pintype "passive"))
      (node (ref "TYPE-C") (pin "B9") (pinfunction "VBUS_B9") (pintype "passive"))
    )
    (net (code "15") (name "/CAM0_CLK_N") (class "Default")
      (node (ref "CAM0") (pin "8") (pinfunction "8_8") (pintype "passive"))
      (node (ref "CM4A") (pin "140") (pinfunction "CAM0_C_N_140") (pintype "passive"))
    )
    (net (code "16") (name "/CAM0_CLK_P") (class "Default")
      (node (ref "CAM0") (pin "9") (pinfunction "9_9") (pintype "passive"))
      (node (ref "CM4A") (pin "142") (pinfunction "CAM0_C_P_142") (pintype "passive"))
    )
    (net (code "17") (name "/CAM0_D0_N") (class "Default")
      (node (ref "CAM0") (pin "2") (pinfunction "2_2") (pintype "passive"))
      (node (ref "CM4A") (pin "128") (pinfunction "CAM0_D0_N_128") (pintype "passive"))
    )
    (net (code "18") (name "/CAM0_D0_P") (class "Default")
      (node (ref "CAM0") (pin "3") (pinfunction "3_3") (pintype "passive"))
      (node (ref "CM4A") (pin "130") (pinfunction "CAM0_D0_P_130") (pintype "passive"))
    )
    (net (code "19") (name "/CAM0_D1_N") (class "Default")
      (node (ref "CAM0") (pin "5") (pinfunction "5_5") (pintype "passive"))
      (node (ref "CM4A") (pin "134") (pinfunction "CAM0_D1_N_134") (pintype "passive"))
    )
    (net (code "20") (name "/CAM0_D1_P") (class "Default")
      (node (ref "CAM0") (pin "6") (pinfunction "6_6") (pintype "passive"))
      (node (ref "CM4A") (pin "136") (pinfunction "CAM0_D1_P_136") (pintype "passive"))
    )
    (net (code "21") (name "/CAM1_CLK_N") (class "Default")
      (node (ref "CAM1") (pin "8") (pinfunction "8_8") (pintype "passive"))
      (node (ref "CM4A") (pin "127") (pinfunction "CAM1_C_N_127") (pintype "passive"))
    )
    (net (code "22") (name "/CAM1_CLK_P") (class "Default")
      (node (ref "CAM1") (pin "9") (pinfunction "9_9") (pintype "passive"))
      (node (ref "CM4A") (pin "129") (pinfunction "CAM1_C_P_129") (pintype "passive"))
    )
    (net (code "23") (name "/CAM1_D0_N") (class "Default")
      (node (ref "CAM1") (pin "2") (pinfunction "2_2") (pintype "passive"))
      (node (ref "CM4A") (pin "115") (pinfunction "CAM1_D0_N_115") (pintype "passive"))
    )
    (net (code "24") (name "/CAM1_D0_P") (class "Default")
      (node (ref "CAM1") (pin "3") (pinfunction "3_3") (pintype "passive"))
      (node (ref "CM4A") (pin "117") (pinfunction "CAM1_D0_P_117") (pintype "passive"))
    )
    (net (code "25") (name "/CAM1_D1_N") (class "Default")
      (node (ref "CAM1") (pin "5") (pinfunction "5_5") (pintype "passive"))
      (node (ref "CM4A") (pin "121") (pinfunction "CAM1_D1_N_121") (pintype "passive"))
    )
    (net (code "26") (name "/CAM1_D1_P") (class "Default")
      (node (ref "CAM1") (pin "6") (pinfunction "6_6") (pintype "passive"))
      (node (ref "CM4A") (pin "123") (pinfunction "CAM1_D1_P_123") (pintype "passive"))
    )
    (net (code "27") (name "/CAM_GPIO") (class "Default")
      (node (ref "CAM0") (pin "11") (pinfunction "11_11") (pintype "passive"))
      (node (ref "CAM1") (pin "11") (pinfunction "11_11") (pintype "passive"))
      (node (ref "CM4A") (pin "97") (pinfunction "Camera_GPIO_97") (pintype "passive"))
    )
    (net (code "28") (name "/CCLK") (class "Default")
      (node (ref "C2000") (pin "C24") (pinfunction "GPIO124/SPICLKC/SD1_D2_C24") (pintype "passive"))
      (node (ref "FPC") (pin "2") (pinfunction "2_2") (pintype "passive"))
    )
    (net (code "29") (name "/CLK") (class "Default")
      (node (ref "C2000") (pin "A57") (pinfunction "SPICLKA/EM1D28/EM2D12/EQEP2S/SCITXDC/SD2_D1/GPIO56_A57") (pintype "passive"))
      (node (ref "CM4A") (pin "38") (pinfunction "GPIO11_38") (pintype "passive"))
    )
    (net (code "30") (name "/CM4_3V3") (class "Default")
      (node (ref "CM4A") (pin "78") (pinfunction "GPIO_VREF_78") (pintype "passive"))
      (node (ref "CM4A") (pin "84") (pinfunction "CM4_3.3V(Output)_84") (pintype "passive"))
      (node (ref "CM4A") (pin "86") (pinfunction "CM4_3.3V(Output)_86") (pintype "passive"))
      (node (ref "D3") (pin "2") (pinfunction "T2_2") (pintype "passive"))
    )
    (net (code "31") (name "/CSIMO") (class "Default")
      (node (ref "C2000") (pin "C20") (pinfunction "GPIO122/SPISIMOC/SD1_D1_C20") (pintype "passive"))
      (node (ref "FPC") (pin "4") (pinfunction "4_4") (pintype "passive"))
    )
    (net (code "32") (name "/CSOMI") (class "Default")
      (node (ref "C2000") (pin "C22") (pinfunction "GPIO123/SPISOMIC/SD1_C1_C22") (pintype "passive"))
      (node (ref "FPC") (pin "3") (pinfunction "3_3") (pintype "passive"))
    )
    (net (code "33") (name "/CSTE") (class "Default")
      (node (ref "C2000") (pin "C26") (pinfunction "GPIO125/~{SPISTEC}/SD1_C2_C26") (pintype "passive"))
      (node (ref "FPC") (pin "1") (pinfunction "1_1") (pintype "passive"))
    )
    (net (code "34") (name "/DM") (class "Default")
      (node (ref "LINGXIAO") (pin "3") (pinfunction "DM_3") (pintype "passive"))
      (node (ref "LINGXIAOU") (pin "2") (pinfunction "DM_2") (pintype "passive"))
    )
    (net (code "35") (name "/DP") (class "Default")
      (node (ref "LINGXIAO") (pin "4") (pinfunction "DP_4") (pintype "passive"))
      (node (ref "LINGXIAOU") (pin "3") (pinfunction "DP_3") (pintype "passive"))
    )
    (net (code "36") (name "/EXTRST") (class "Default")
      (node (ref "CM4A") (pin "100") (pinfunction "nEXTRST_100") (pintype "passive"))
      (node (ref "USBHUNB4") (pin "26") (pinfunction "RESET_26") (pintype "passive"))
    )
    (net (code "37") (name "/HDMI0_CEC") (class "Default")
      (node (ref "CM4A") (pin "151") (pinfunction "HDMI0_CEC_151") (pintype "passive"))
      (node (ref "HDMI") (pin "13") (pinfunction "CEC_13") (pintype "passive"))
    )
    (net (code "38") (name "/HDMI0_CLK_N") (class "Default")
      (node (ref "CM4A") (pin "190") (pinfunction "HDMI0_CLK_N_190") (pintype "passive"))
      (node (ref "HDMI") (pin "12") (pinfunction "CLKN_12") (pintype "passive"))
    )
    (net (code "39") (name "/HDMI0_CLK_P") (class "Default")
      (node (ref "CM4A") (pin "188") (pinfunction "HDMI0_CLK_P_188") (pintype "passive"))
      (node (ref "HDMI") (pin "10") (pinfunction "CLKP_10") (pintype "passive"))
    )
    (net (code "40") (name "/HDMI0_HOTPLUG") (class "Default")
      (node (ref "CM4A") (pin "153") (pinfunction "HDMI0_HOTPLUG_153") (pintype "passive"))
      (node (ref "HDMI") (pin "19") (pinfunction "HPD_19") (pintype "passive"))
    )
    (net (code "41") (name "/HDMI0_SCL") (class "Default")
      (node (ref "CM4A") (pin "200") (pinfunction "HDMI0_SCL_200") (pintype "passive"))
      (node (ref "HDMI") (pin "15") (pinfunction "SCL_15") (pintype "passive"))
    )
    (net (code "42") (name "/HDMI0_SDA") (class "Default")
      (node (ref "CM4A") (pin "199") (pinfunction "HDMI0_SDA_199") (pintype "passive"))
      (node (ref "HDMI") (pin "16") (pinfunction "SDA_16") (pintype "passive"))
    )
    (net (code "43") (name "/HDMI0_TX0_N") (class "Default")
      (node (ref "CM4A") (pin "184") (pinfunction "HDMI0_TX0_N_184") (pintype "passive"))
      (node (ref "HDMI") (pin "9") (pinfunction "D0N_9") (pintype "passive"))
    )
    (net (code "44") (name "/HDMI0_TX0_P") (class "Default")
      (node (ref "CM4A") (pin "182") (pinfunction "HDMI0_TX0_P_182") (pintype "passive"))
      (node (ref "HDMI") (pin "7") (pinfunction "D0P_7") (pintype "passive"))
    )
    (net (code "45") (name "/HDMI0_TX1_N") (class "Default")
      (node (ref "CM4A") (pin "178") (pinfunction "HDMI0_TX1_N_178") (pintype "passive"))
      (node (ref "HDMI") (pin "6") (pinfunction "D1N_6") (pintype "passive"))
    )
    (net (code "46") (name "/HDMI0_TX1_P") (class "Default")
      (node (ref "CM4A") (pin "176") (pinfunction "HDMI0_TX1_P_176") (pintype "passive"))
      (node (ref "HDMI") (pin "4") (pinfunction "D1P_4") (pintype "passive"))
    )
    (net (code "47") (name "/HDMI0_TX2_N") (class "Default")
      (node (ref "CM4A") (pin "172") (pinfunction "HDMI0_TX2_N_172") (pintype "passive"))
      (node (ref "HDMI") (pin "3") (pinfunction "D2N_3") (pintype "passive"))
    )
    (net (code "48") (name "/HDMI0_TX2_P") (class "Default")
      (node (ref "CM4A") (pin "170") (pinfunction "HDMI0_TX2_P_170") (pintype "passive"))
      (node (ref "HDMI") (pin "1") (pinfunction "D2P_1") (pintype "passive"))
    )
    (net (code "49") (name "/HD_0N") (class "Default")
      (node (ref "USB0") (pin "2") (pinfunction "D-_2") (pintype "passive"))
      (node (ref "USBHUNB4") (pin "1") (pinfunction "D1N_1") (pintype "passive"))
    )
    (net (code "50") (name "/HD_0P") (class "Default")
      (node (ref "USB0") (pin "3") (pinfunction "D+_3") (pintype "passive"))
      (node (ref "USBHUNB4") (pin "2") (pinfunction "D1P_2") (pintype "passive"))
    )
    (net (code "51") (name "/HD_1N") (class "Default")
      (node (ref "USB1") (pin "2") (pinfunction "D-_2") (pintype "passive"))
      (node (ref "USBHUNB4") (pin "3") (pinfunction "D2N_3") (pintype "passive"))
    )
    (net (code "52") (name "/HD_1P") (class "Default")
      (node (ref "USB1") (pin "3") (pinfunction "D+_3") (pintype "passive"))
      (node (ref "USBHUNB4") (pin "4") (pinfunction "D2P_4") (pintype "passive"))
    )
    (net (code "53") (name "/HD_2N") (class "Default")
      (node (ref "USB2") (pin "2") (pinfunction "D-_2") (pintype "passive"))
      (node (ref "USBHUNB4") (pin "6") (pinfunction "D3N_6") (pintype "passive"))
    )
    (net (code "54") (name "/HD_2P") (class "Default")
      (node (ref "USB2") (pin "3") (pinfunction "D+_3") (pintype "passive"))
      (node (ref "USBHUNB4") (pin "7") (pinfunction "D3P_7") (pintype "passive"))
    )
    (net (code "55") (name "/HD_3N") (class "Default")
      (node (ref "USB3") (pin "2") (pinfunction "D-_2") (pintype "passive"))
      (node (ref "USBHUNB4") (pin "8") (pinfunction "D4N_8") (pintype "passive"))
    )
    (net (code "56") (name "/HD_3P") (class "Default")
      (node (ref "USB3") (pin "3") (pinfunction "D+_3") (pintype "passive"))
      (node (ref "USBHUNB4") (pin "9") (pinfunction "D4P_9") (pintype "passive"))
    )
    (net (code "57") (name "/OCS1") (class "Default")
      (node (ref "AN") (pin "4") (pinfunction "FALT_4") (pintype "passive"))
      (node (ref "USBHUNB4") (pin "13") (pinfunction "OCS1_13") (pintype "passive"))
      (node (ref "USBHUNB4") (pin "17") (pinfunction "OSC2_17") (pintype "passive"))
      (node (ref "USBHUNB4") (pin "19") (pinfunction "OSC3_19") (pintype "passive"))
      (node (ref "USBHUNB4") (pin "21") (pinfunction "OSC4_21") (pintype "passive"))
    )
    (net (code "58") (name "/PWM1") (class "Default")
      (node (ref "C2000") (pin "A18") (pinfunction "GPIO161/EPWM9A_A18") (pintype "passive"))
      (node (ref "PWMS") (pin "1") (pinfunction "PWM1_1") (pintype "passive"))
    )
    (net (code "59") (name "/PWM2") (class "Default")
      (node (ref "C2000") (pin "A14") (pinfunction "GPIO163/EPWM10A_A14") (pintype "passive"))
      (node (ref "PWMS") (pin "4") (pinfunction "PWM2_4") (pintype "passive"))
    )
    (net (code "60") (name "/PWM3") (class "Default")
      (node (ref "C2000") (pin "A10") (pinfunction "GPIO165/EPWM11A_A10") (pintype "passive"))
      (node (ref "PWMS") (pin "7") (pinfunction "PWM3_7") (pintype "passive"))
    )
    (net (code "61") (name "/PWM4") (class "Default")
      (node (ref "C2000") (pin "A6") (pinfunction "GPIO167/EPWM12A_A6") (pintype "passive"))
      (node (ref "PWMS") (pin "10") (pinfunction "PWM4_10") (pintype "passive"))
    )
    (net (code "62") (name "/PWM_B") (class "Default")
      (node (ref "C2000") (pin "A30") (pinfunction "GPIO155/EPWM6A_A30") (pintype "passive"))
      (node (ref "R14") (pin "2") (pinfunction "2_2") (pintype "passive"))
    )
    (net (code "63") (name "/PWM_G") (class "Default")
      (node (ref "C2000") (pin "A22") (pinfunction "GPIO159/EPWM8A_A22") (pintype "passive"))
      (node (ref "R18") (pin "2") (pinfunction "2_2") (pintype "passive"))
    )
    (net (code "64") (name "/PWM_R") (class "Default")
      (node (ref "C2000") (pin "A26") (pinfunction "GPIO157/EPWM7A_A26") (pintype "passive"))
      (node (ref "R16") (pin "2") (pinfunction "2_2") (pintype "passive"))
    )
    (net (code "65") (name "/PWR1") (class "Default")
      (node (ref "AN") (pin "3") (pinfunction "EN_3") (pintype "passive"))
      (node (ref "USBHUNB4") (pin "12") (pinfunction "PWR1_12") (pintype "passive"))
    )
    (net (code "66") (name "/PWR_IN") (class "Default")
      (node (ref "ADC") (pin "14") (pinfunction "VOL2_14") (pintype "passive"))
      (node (ref "C19") (pin "2") (pinfunction "2_2") (pintype "passive"))
      (node (ref "C20") (pin "2") (pinfunction "2_2") (pintype "passive"))
      (node (ref "C21") (pin "2") (pinfunction "2_2") (pintype "passive"))
      (node (ref "C22") (pin "2") (pinfunction "2_2") (pintype "passive"))
      (node (ref "C23") (pin "2") (pinfunction "2_2") (pintype "passive"))
      (node (ref "C24") (pin "2") (pinfunction "2_2") (pintype "passive"))
      (node (ref "C34") (pin "2") (pinfunction "2_2") (pintype "passive"))
      (node (ref "C35") (pin "2") (pinfunction "2_2") (pintype "passive"))
      (node (ref "C36") (pin "2") (pinfunction "2_2") (pintype "passive"))
      (node (ref "C37") (pin "2") (pinfunction "2_2") (pintype "passive"))
      (node (ref "C38") (pin "2") (pinfunction "2_2") (pintype "passive"))
      (node (ref "C39") (pin "2") (pinfunction "2_2") (pintype "passive"))
      (node (ref "C4") (pin "2") (pinfunction "2_2") (pintype "passive"))
      (node (ref "C5") (pin "2") (pinfunction "2_2") (pintype "passive"))
      (node (ref "C6") (pin "2") (pinfunction "2_2") (pintype "passive"))
      (node (ref "C7") (pin "2") (pinfunction "2_2") (pintype "passive"))
      (node (ref "C8") (pin "2") (pinfunction "2_2") (pintype "passive"))
      (node (ref "C9") (pin "2") (pinfunction "2_2") (pintype "passive"))
      (node (ref "PSU1") (pin "2") (pinfunction "VIN_2") (pintype "passive"))
      (node (ref "PSU1") (pin "3") (pinfunction "EN_3") (pintype "passive"))
      (node (ref "PSU2") (pin "2") (pinfunction "VIN_2") (pintype "passive"))
      (node (ref "PSU2") (pin "3") (pinfunction "EN_3") (pintype "passive"))
      (node (ref "PSU3") (pin "2") (pinfunction "VIN_2") (pintype "passive"))
      (node (ref "PSU3") (pin "3") (pinfunction "EN_3") (pintype "passive"))
      (node (ref "PWR") (pin "1") (pinfunction "1_1") (pintype "passive"))
    )
    (net (code "67") (name "/RST") (class "Default")
      (node (ref "C2000") (pin "D34") (pinfunction "SYS_RESET_INPUT_D34") (pintype "passive"))
      (node (ref "C3") (pin "2") (pinfunction "2_2") (pintype "passive"))
      (node (ref "R13") (pin "1") (pinfunction "1_1") (pintype "passive"))
    )
    (net (code "68") (name "/RXA") (class "Default")
      (node (ref "C2000") (pin "D13") (pinfunction "GPIO136/SD2_D4/SCIRXDA_D13") (pintype "passive"))
      (node (ref "LINGXIAO") (pin "5") (pinfunction "T1_5") (pintype "passive"))
    )
    (net (code "69") (name "/RXB") (class "Default")
      (node (ref "C2000") (pin "B41") (pinfunction "EPWM12B/EQEP1I/MFSXA/SCIRXDB/~{SPISTEB}/SD1_C4/GPIO23_B41") (pintype "passive"))
      (node (ref "CM4A") (pin "55") (pinfunction "GPIO14_55") (pintype "passive"))
    )
    (net (code "70") (name "/RXC") (class "Default")
      (node (ref "C2000") (pin "B22") (pinfunction "EM2A9/EQEP3I/SCIRXDC/GPIO107_B22") (pintype "passive"))
      (node (ref "OF") (pin "4") (pinfunction "T4_4") (pintype "passive"))
    )
    (net (code "71") (name "/RXD") (class "Default")
      (node (ref "C2000") (pin "B49") (pinfunction "GPIO94/SCIRXDD_B49") (pintype "passive"))
      (node (ref "R26") (pin "1") (pinfunction "1_1") (pintype "passive"))
      (node (ref "SI4") (pin "3") (pinfunction "B_3") (pintype "passive"))
    )
    (net (code "72") (name "/RXLING") (class "Default")
      (node (ref "LINGXIAO") (pin "8") (pinfunction "R2_8") (pintype "passive"))
      (node (ref "LINGXIAOB") (pin "4") (pinfunction "T4_4") (pintype "passive"))
    )
    (net (code "73") (name "/SCL") (class "Default")
      (node (ref "C2000") (pin "B20") (pinfunction "EM2A7/EQEP3B/SCIRXDD/SCLA/GPIO105_B20") (pintype "passive"))
      (node (ref "CM4A") (pin "56") (pinfunction "GPIO3_56") (pintype "passive"))
    )
    (net (code "74") (name "/SCL0") (class "Default")
      (node (ref "CAM0") (pin "13") (pinfunction "13_13") (pintype "passive"))
      (node (ref "CM4A") (pin "80") (pinfunction "SCL0_80") (pintype "passive"))
      (node (ref "R42") (pin "1") (pinfunction "1_1") (pintype "passive"))
    )
    (net (code "75") (name "/SCL1") (class "Default")
      (node (ref "CAM1") (pin "13") (pinfunction "13_13") (pintype "passive"))
      (node (ref "CM4A") (pin "35") (pinfunction "ID_SC_35") (pintype "passive"))
      (node (ref "R44") (pin "1") (pinfunction "1_1") (pintype "passive"))
    )
    (net (code "76") (name "/SDA") (class "Default")
      (node (ref "C2000") (pin "B18") (pinfunction "EM2A6/EQEP3A/SCITXDD/SDAA/GPIO104_B18") (pintype "passive"))
      (node (ref "CM4A") (pin "58") (pinfunction "GPIO2_58") (pintype "passive"))
    )
    (net (code "77") (name "/SDA0") (class "Default")
      (node (ref "CAM0") (pin "14") (pinfunction "14_14") (pintype "passive"))
      (node (ref "CM4A") (pin "82") (pinfunction "SDA0_82") (pintype "passive"))
      (node (ref "R41") (pin "1") (pinfunction "1_1") (pintype "passive"))
    )
    (net (code "78") (name "/SDA1") (class "Default")
      (node (ref "CAM1") (pin "14") (pinfunction "14_14") (pintype "passive"))
      (node (ref "CM4A") (pin "36") (pinfunction "ID_SD_36") (pintype "passive"))
      (node (ref "R43") (pin "1") (pinfunction "1_1") (pintype "passive"))
    )
    (net (code "79") (name "/SD_CLK") (class "Default")
      (node (ref "CM4A") (pin "57") (pinfunction "SD_CLK_57") (pintype "passive"))
      (node (ref "SD") (pin "5") (pinfunction "CLK_5") (pintype "passive"))
    )
    (net (code "80") (name "/SD_CMD") (class "Default")
      (node (ref "CM4A") (pin "62") (pinfunction "SD_CMD_62") (pintype "passive"))
      (node (ref "SD") (pin "3") (pinfunction "CMD_3") (pintype "passive"))
    )
    (net (code "81") (name "/SD_DAT0") (class "Default")
      (node (ref "CM4A") (pin "63") (pinfunction "SD_DAT0_63") (pintype "passive"))
      (node (ref "SD") (pin "7") (pinfunction "DATA0_7") (pintype "passive"))
    )
    (net (code "82") (name "/SD_DAT1") (class "Default")
      (node (ref "CM4A") (pin "67") (pinfunction "SD_DAT1_67") (pintype "passive"))
      (node (ref "SD") (pin "8") (pinfunction "DATA1_8") (pintype "passive"))
    )
    (net (code "83") (name "/SD_DAT2") (class "Default")
      (node (ref "CM4A") (pin "69") (pinfunction "SD_DAT2_69") (pintype "passive"))
      (node (ref "SD") (pin "1") (pinfunction "DATA2_1") (pintype "passive"))
    )
    (net (code "84") (name "/SD_DAT3") (class "Default")
      (node (ref "CM4A") (pin "61") (pinfunction "SD_DAT3_61") (pintype "passive"))
      (node (ref "SD") (pin "2") (pinfunction "CD/DATA3_2") (pintype "passive"))
    )
    (net (code "85") (name "/SIMO") (class "Default")
      (node (ref "C2000") (pin "A53") (pinfunction "MCLKRA/EM1D26/EM2D10/OUTPUTXBAR1/SPICLKB/SD2_D2/SPISIMOA/GPIO58_A53") (pintype "passive"))
      (node (ref "CM4A") (pin "44") (pinfunction "GPIO10_44") (pintype "passive"))
    )
    (net (code "86") (name "/SOMI") (class "Default")
      (node (ref "C2000") (pin "A59") (pinfunction "SPISOMIA/EM1D29/EM2D13/EQEP2B/SCIRXDB/SD1_C4/GPIO55_A59") (pintype "passive"))
      (node (ref "CM4A") (pin "40") (pinfunction "GPIO9_40") (pintype "passive"))
    )
    (net (code "87") (name "/STE") (class "Default")
      (node (ref "C2000") (pin "A55") (pinfunction "~{SPISTEA}/EMID27/EM2D11/EQEP2I/SCIRXDC/SD2_C1/GPIO57_A55") (pintype "passive"))
      (node (ref "CM4A") (pin "39") (pinfunction "GPIO8_39") (pintype "passive"))
    )
    (net (code "88") (name "/TCK") (class "Default")
      (node (ref "C2000") (pin "D27") (pinfunction "TCK_D27") (pintype "passive"))
      (node (ref "JTAG") (pin "11") (pinfunction "TCK_11") (pintype "passive"))
      (node (ref "JTAG") (pin "9") (pinfunction "TCK_RET_9") (pintype "passive"))
      (node (ref "R12") (pin "2") (pinfunction "2_2") (pintype "passive"))
    )
    (net (code "89") (name "/TDI") (class "Default")
      (node (ref "C2000") (pin "D19") (pinfunction "TDI_D19") (pintype "passive"))
      (node (ref "JTAG") (pin "3") (pinfunction "TDI_3") (pintype "passive"))
    )
    (net (code "90") (name "/TDO") (class "Default")
      (node (ref "C2000") (pin "D25") (pinfunction "TDO_D25") (pintype "passive"))
      (node (ref "JTAG") (pin "7") (pinfunction "TDO_7") (pintype "passive"))
    )
    (net (code "91") (name "/TMS") (class "Default")
      (node (ref "C2000") (pin "D21") (pinfunction "TMS_D21") (pintype "passive"))
      (node (ref "JTAG") (pin "1") (pinfunction "TMS_1") (pintype "passive"))
    )
    (net (code "92") (name "/TRST") (class "Default")
      (node (ref "C2000") (pin "D23") (pinfunction "~{TRST}_D23") (pintype "passive"))
      (node (ref "JTAG") (pin "2") (pinfunction "~{TRST}_2") (pintype "passive"))
      (node (ref "R11") (pin "2") (pinfunction "2_2") (pintype "passive"))
    )
    (net (code "93") (name "/TXA") (class "Default")
      (node (ref "C2000") (pin "D11") (pinfunction "GPIO135/SD2_C3/SCITXDA_D11") (pintype "passive"))
      (node (ref "LINGXIAO") (pin "6") (pinfunction "R1_6") (pintype "passive"))
    )
    (net (code "94") (name "/TXB") (class "Default")
      (node (ref "C2000") (pin "B43") (pinfunction "EPWM12A/EQEP1S/MCLKXA/SCITXDB/SPICLKB/SD1_D4/GPIO22_B43") (pintype "passive"))
      (node (ref "CM4A") (pin "51") (pinfunction "GPIO15_51") (pintype "passive"))
    )
    (net (code "95") (name "/TXC") (class "Default")
      (node (ref "C2000") (pin "B24") (pinfunction "EM2A8/EQEP3S/SCITXDC/GPIO106_B24") (pintype "passive"))
      (node (ref "OF") (pin "3") (pinfunction "T3_3") (pintype "passive"))
    )
    (net (code "96") (name "/TXLING") (class "Default")
      (node (ref "LINGXIAO") (pin "7") (pinfunction "T2_7") (pintype "passive"))
      (node (ref "LINGXIAOB") (pin "3") (pinfunction "T3_3") (pintype "passive"))
    )
    (net (code "97") (name "/USB0_N") (class "Default")
      (node (ref "CM4A") (pin "103") (pinfunction "USB_N_103") (pintype "passive"))
      (node (ref "USBHUNB4") (pin "30") (pinfunction "DM_30") (pintype "passive"))
    )
    (net (code "98") (name "/USB0_P") (class "Default")
      (node (ref "CM4A") (pin "105") (pinfunction "USB_P_105") (pintype "passive"))
      (node (ref "USBHUNB4") (pin "31") (pinfunction "DP_31") (pintype "passive"))
    )
    (net (code "99") (name "/VBAT") (class "Default")
      (node (ref "AN") (pin "6") (pinfunction "OUT_6") (pintype "passive"))
      (node (ref "C55") (pin "2") (pinfunction "2_2") (pintype "passive"))
      (node (ref "C56") (pin "2") (pinfunction "2_2") (pintype "passive"))
      (node (ref "C57") (pin "2") (pinfunction "2_2") (pintype "passive"))
      (node (ref "C58") (pin "2") (pinfunction "2_2") (pintype "passive"))
      (node (ref "CT4") (pin "1") (pinfunction "A_1") (pintype "passive"))
      (node (ref "USB0") (pin "1") (pinfunction "VCC_1") (pintype "passive"))
      (node (ref "USB1") (pin "1") (pinfunction "VCC_1") (pintype "passive"))
      (node (ref "USB2") (pin "1") (pinfunction "VCC_1") (pintype "passive"))
      (node (ref "USB3") (pin "1") (pinfunction "VCC_1") (pintype "passive"))
    )
    (net (code "100") (name "GND") (class "Default")
      (node (ref "ADC") (pin "17") (pinfunction "GND_17") (pintype "passive"))
      (node (ref "ADC") (pin "18") (pinfunction "GND_18") (pintype "passive"))
      (node (ref "AN") (pin "2") (pinfunction "GND_2") (pintype "passive"))
      (node (ref "C1") (pin "1") (pinfunction "1_1") (pintype "passive"))
      (node (ref "C11") (pin "1") (pinfunction "1_1") (pintype "passive"))
      (node (ref "C12") (pin "1") (pinfunction "1_1") (pintype "passive"))
      (node (ref "C13") (pin "1") (pinfunction "1_1") (pintype "passive"))
      (node (ref "C15") (pin "1") (pinfunction "1_1") (pintype "passive"))
      (node (ref "C16") (pin "1") (pinfunction "1_1") (pintype "passive"))
      (node (ref "C17") (pin "1") (pinfunction "1_1") (pintype "passive"))
      (node (ref "C18") (pin "1") (pinfunction "1_1") (pintype "passive"))
      (node (ref "C19") (pin "1") (pinfunction "1_1") (pintype "passive"))
      (node (ref "C2") (pin "1") (pinfunction "1_1") (pintype "passive"))
      (node (ref "C20") (pin "1") (pinfunction "1_1") (pintype "passive"))
      (node (ref "C2000") (pin "A2") (pinfunction "GND_A2") (pintype "power_in"))
      (node (ref "C2000") (pin "A52") (pinfunction "GND_A52") (pintype "power_in"))
      (node (ref "C2000") (pin "A60") (pinfunction "GND_A60") (pintype "power_in"))
      (node (ref "C2000") (pin "B26") (pinfunction "GND_B26") (pintype "power_in"))
      (node (ref "C2000") (pin "B40") (pinfunction "GND_B40") (pintype "power_in"))
      (node (ref "C2000") (pin "B45") (pinfunction "GND_B45") (pintype "power_in"))
      (node (ref "C2000") (pin "B53") (pinfunction "GND_B53") (pintype "power_in"))
      (node (ref "C2000") (pin "B60") (pinfunction "GND_B60") (pintype "power_in"))
      (node (ref "C2000") (pin "C12") (pinfunction "GND_C12") (pintype "power_in"))
      (node (ref "C2000") (pin "C14") (pinfunction "GND_C14") (pintype "power_in"))
      (node (ref "C2000") (pin "C28") (pinfunction "GND_C28") (pintype "power_in"))
      (node (ref "C2000") (pin "C34") (pinfunction "GND_C34") (pintype "power_in"))
      (node (ref "C2000") (pin "C40") (pinfunction "GND_C40") (pintype "power_in"))
      (node (ref "C2000") (pin "C60") (pinfunction "GND_C60") (pintype "power_in"))
      (node (ref "C2000") (pin "D12") (pinfunction "GND_D12") (pintype "power_in"))
      (node (ref "C2000") (pin "D17") (pinfunction "GND_D17") (pintype "power_in"))
      (node (ref "C2000") (pin "D28") (pinfunction "GND_D28") (pintype "power_in"))
      (node (ref "C2000") (pin "D29") (pinfunction "GND_D29") (pintype "power_in"))
      (node (ref "C2000") (pin "D30") (pinfunction "GND_D30") (pintype "power_in"))
      (node (ref "C2000") (pin "D35") (pinfunction "GND_D35") (pintype "power_in"))
      (node (ref "C2000") (pin "D36") (pinfunction "GND_D36") (pintype "power_in"))
      (node (ref "C2000") (pin "D38") (pinfunction "GND_D38") (pintype "power_in"))
      (node (ref "C2000") (pin "D42") (pinfunction "GND_D42") (pintype "power_in"))
      (node (ref "C2000") (pin "D44") (pinfunction "GND_D44") (pintype "power_in"))
      (node (ref "C2000") (pin "D55") (pinfunction "GND_D55") (pintype "power_in"))
      (node (ref "C2000") (pin "D58") (pinfunction "GND_D58") (pintype "power_in"))
      (node (ref "C2000") (pin "D6") (pinfunction "GND_D6") (pintype "power_in"))
      (node (ref "C2000") (pin "D60") (pinfunction "GND_D60") (pintype "power_in"))
      (node (ref "C21") (pin "1") (pinfunction "1_1") (pintype "passive"))
      (node (ref "C22") (pin "1") (pinfunction "1_1") (pintype "passive"))
      (node (ref "C23") (pin "1") (pinfunction "1_1") (pintype "passive"))
      (node (ref "C24") (pin "1") (pinfunction "1_1") (pintype "passive"))
      (node (ref "C26") (pin "1") (pinfunction "1_1") (pintype "passive"))
      (node (ref "C27") (pin "1") (pinfunction "1_1") (pintype "passive"))
      (node (ref "C28") (pin "1") (pinfunction "1_1") (pintype "passive"))
      (node (ref "C3") (pin "1") (pinfunction "1_1") (pintype "passive"))
      (node (ref "C30") (pin "1") (pinfunction "1_1") (pintype "passive"))
      (node (ref "C31") (pin "1") (pinfunction "1_1") (pintype "passive"))
      (node (ref "C32") (pin "1") (pinfunction "1_1") (pintype "passive"))
      (node (ref "C33") (pin "1") (pinfunction "1_1") (pintype "passive"))
      (node (ref "C34") (pin "1") (pinfunction "1_1") (pintype "passive"))
      (node (ref "C35") (pin "1") (pinfunction "1_1") (pintype "passive"))
      (node (ref "C36") (pin "1") (pinfunction "1_1") (pintype "passive"))
      (node (ref "C37") (pin "1") (pinfunction "1_1") (pintype "passive"))
      (node (ref "C38") (pin "1") (pinfunction "1_1") (pintype "passive"))
      (node (ref "C39") (pin "1") (pinfunction "1_1") (pintype "passive"))
      (node (ref "C4") (pin "1") (pinfunction "1_1") (pintype "passive"))
      (node (ref "C41") (pin "1") (pinfunction "1_1") (pintype "passive"))
      (node (ref "C42") (pin "1") (pinfunction "1_1") (pintype "passive"))
      (node (ref "C43") (pin "1") (pinfunction "1_1") (pintype "passive"))
      (node (ref "C45") (pin "1") (pinfunction "1_1") (pintype "passive"))
      (node (ref "C46") (pin "1") (pinfunction "1_1") (pintype "passive"))
      (node (ref "C47") (pin "1") (pinfunction "1_1") (pintype "passive"))
      (node (ref "C48") (pin "1") (pinfunction "1_1") (pintype "passive"))
      (node (ref "C49") (pin "2") (pinfunction "2_2") (pintype "passive"))
      (node (ref "C5") (pin "1") (pinfunction "1_1") (pintype "passive"))
      (node (ref "C50") (pin "2") (pinfunction "2_2") (pintype "passive"))
      (node (ref "C51") (pin "1") (pinfunction "1_1") (pintype "passive"))
      (node (ref "C52") (pin "1") (pinfunction "1_1") (pintype "passive"))
      (node (ref "C53") (pin "1") (pinfunction "1_1") (pintype "passive"))
      (node (ref "C54") (pin "1") (pinfunction "1_1") (pintype "passive"))
      (node (ref "C55") (pin "1") (pinfunction "1_1") (pintype "passive"))
      (node (ref "C56") (pin "1") (pinfunction "1_1") (pintype "passive"))
      (node (ref "C57") (pin "1") (pinfunction "1_1") (pintype "passive"))
      (node (ref "C58") (pin "1") (pinfunction "1_1") (pintype "passive"))
      (node (ref "C6") (pin "1") (pinfunction "1_1") (pintype "passive"))
      (node (ref "C7") (pin "1") (pinfunction "1_1") (pintype "passive"))
      (node (ref "C8") (pin "1") (pinfunction "1_1") (pintype "passive"))
      (node (ref "C9") (pin "1") (pinfunction "1_1") (pintype "passive"))
      (node (ref "CAM0") (pin "1") (pinfunction "1_1") (pintype "passive"))
      (node (ref "CAM0") (pin "10") (pinfunction "10_10") (pintype "passive"))
      (node (ref "CAM0") (pin "4") (pinfunction "4_4") (pintype "passive"))
      (node (ref "CAM0") (pin "7") (pinfunction "7_7") (pintype "passive"))
      (node (ref "CAM1") (pin "1") (pinfunction "1_1") (pintype "passive"))
      (node (ref "CAM1") (pin "10") (pinfunction "10_10") (pintype "passive"))
      (node (ref "CAM1") (pin "4") (pinfunction "4_4") (pintype "passive"))
      (node (ref "CAM1") (pin "7") (pinfunction "7_7") (pintype "passive"))
      (node (ref "CM4A") (pin "1") (pinfunction "GND_1") (pintype "passive"))
      (node (ref "CM4A") (pin "107") (pinfunction "GND_107") (pintype "passive"))
      (node (ref "CM4A") (pin "108") (pinfunction "GND_108") (pintype "passive"))
      (node (ref "CM4A") (pin "113") (pinfunction "GND_113") (pintype "passive"))
      (node (ref "CM4A") (pin "114") (pinfunction "GND_114") (pintype "passive"))
      (node (ref "CM4A") (pin "119") (pinfunction "GND_119") (pintype "passive"))
      (node (ref "CM4A") (pin "120") (pinfunction "GND_120") (pintype "passive"))
      (node (ref "CM4A") (pin "125") (pinfunction "GND_125") (pintype "passive"))
      (node (ref "CM4A") (pin "126") (pinfunction "GND_126") (pintype "passive"))
      (node (ref "CM4A") (pin "13") (pinfunction "GND_13") (pintype "passive"))
      (node (ref "CM4A") (pin "131") (pinfunction "GND_131") (pintype "passive"))
      (node (ref "CM4A") (pin "132") (pinfunction "GND_132") (pintype "passive"))
      (node (ref "CM4A") (pin "137") (pinfunction "GND_137") (pintype "passive"))
      (node (ref "CM4A") (pin "138") (pinfunction "GND_138") (pintype "passive"))
      (node (ref "CM4A") (pin "14") (pinfunction "GND_14") (pintype "passive"))
      (node (ref "CM4A") (pin "144") (pinfunction "GND_144") (pintype "passive"))
      (node (ref "CM4A") (pin "150") (pinfunction "GND_150") (pintype "passive"))
      (node (ref "CM4A") (pin "155") (pinfunction "GND_155") (pintype "passive"))
      (node (ref "CM4A") (pin "156") (pinfunction "GND_156") (pintype "passive"))
      (node (ref "CM4A") (pin "161") (pinfunction "GND_161") (pintype "passive"))
      (node (ref "CM4A") (pin "162") (pinfunction "GND_162") (pintype "passive"))
      (node (ref "CM4A") (pin "167") (pinfunction "GND_167") (pintype "passive"))
      (node (ref "CM4A") (pin "168") (pinfunction "GND_168") (pintype "passive"))
      (node (ref "CM4A") (pin "173") (pinfunction "GND_173") (pintype "passive"))
      (node (ref "CM4A") (pin "174") (pinfunction "GND_174") (pintype "passive"))
      (node (ref "CM4A") (pin "179") (pinfunction "GND_179") (pintype "passive"))
      (node (ref "CM4A") (pin "180") (pinfunction "GND_180") (pintype "passive"))
      (node (ref "CM4A") (pin "185") (pinfunction "GND_185") (pintype "passive"))
      (node (ref "CM4A") (pin "186") (pinfunction "GND_186") (pintype "passive"))
      (node (ref "CM4A") (pin "191") (pinfunction "GND_191") (pintype "passive"))
      (node (ref "CM4A") (pin "192") (pinfunction "GND_192") (pintype "passive"))
      (node (ref "CM4A") (pin "197") (pinfunction "GND_197") (pintype "passive"))
      (node (ref "CM4A") (pin "198") (pinfunction "GND_198") (pintype "passive"))
      (node (ref "CM4A") (pin "2") (pinfunction "GND_2") (pintype "passive"))
      (node (ref "CM4A") (pin "22") (pinfunction "GND_22") (pintype "passive"))
      (node (ref "CM4A") (pin "23") (pinfunction "GND_23") (pintype "passive"))
      (node (ref "CM4A") (pin "32") (pinfunction "GND_32") (pintype "passive"))
      (node (ref "CM4A") (pin "33") (pinfunction "GND_33") (pintype "passive"))
      (node (ref "CM4A") (pin "42") (pinfunction "GND_42") (pintype "passive"))
      (node (ref "CM4A") (pin "43") (pinfunction "GND_43") (pintype "passive"))
      (node (ref "CM4A") (pin "52") (pinfunction "GND_52") (pintype "passive"))
      (node (ref "CM4A") (pin "53") (pinfunction "GND_53") (pintype "passive"))
      (node (ref "CM4A") (pin "59") (pinfunction "GND_59") (pintype "passive"))
      (node (ref "CM4A") (pin "60") (pinfunction "GND_60") (pintype "passive"))
      (node (ref "CM4A") (pin "65") (pinfunction "GND_65") (pintype "passive"))
      (node (ref "CM4A") (pin "66") (pinfunction "GND_66") (pintype "passive"))
      (node (ref "CM4A") (pin "7") (pinfunction "GND_7") (pintype "passive"))
      (node (ref "CM4A") (pin "71") (pinfunction "GND_71") (pintype "passive"))
      (node (ref "CM4A") (pin "74") (pinfunction "GND_74") (pintype "passive"))
      (node (ref "CM4A") (pin "8") (pinfunction "GND_8") (pintype "passive"))
      (node (ref "CM4A") (pin "98") (pinfunction "GND_98") (pintype "passive"))
      (node (ref "CT1") (pin "2") (pinfunction "K_2") (pintype "passive"))
      (node (ref "CT2") (pin "2") (pinfunction "K_2") (pintype "passive"))
      (node (ref "CT3") (pin "2") (pinfunction "K_2") (pintype "passive"))
      (node (ref "CT4") (pin "2") (pinfunction "K_2") (pintype "passive"))
      (node (ref "ESD1") (pin "2") (pinfunction "GND_2") (pintype "passive"))
      (node (ref "ESD2") (pin "2") (pinfunction "GND_2") (pintype "passive"))
      (node (ref "FPC") (pin "0") (pinfunction "0_0") (pintype "passive"))
      (node (ref "FPC") (pin "6") (pinfunction "6_6") (pintype "passive"))
      (node (ref "HDMI") (pin "11") (pinfunction "GND_11") (pintype "passive"))
      (node (ref "HDMI") (pin "17") (pinfunction "GND_17") (pintype "passive"))
      (node (ref "HDMI") (pin "2") (pinfunction "GND_2") (pintype "passive"))
      (node (ref "HDMI") (pin "5") (pinfunction "GND_5") (pintype "passive"))
      (node (ref "HDMI") (pin "8") (pinfunction "GND_8") (pintype "passive"))
      (node (ref "JTAG") (pin "10") (pinfunction "GND_10") (pintype "passive"))
      (node (ref "JTAG") (pin "12") (pinfunction "GND_12") (pintype "passive"))
      (node (ref "JTAG") (pin "4") (pinfunction "GND_4") (pintype "passive"))
      (node (ref "JTAG") (pin "8") (pinfunction "GND_8") (pintype "passive"))
      (node (ref "LINGXIAO") (pin "1") (pinfunction "GND_1") (pintype "passive"))
      (node (ref "LINGXIAOB") (pin "2") (pinfunction "T2_2") (pintype "passive"))
      (node (ref "LINGXIAOU") (pin "5") (pinfunction "GND_5") (pintype "passive"))
      (node (ref "OF") (pin "2") (pinfunction "T2_2") (pintype "passive"))
      (node (ref "PSU1") (pin "7") (pinfunction "GND_7") (pintype "passive"))
      (node (ref "PSU1") (pin "9") (pinfunction "EP_9") (pintype "passive"))
      (node (ref "PSU2") (pin "7") (pinfunction "GND_7") (pintype "passive"))
      (node (ref "PSU2") (pin "9") (pinfunction "EP_9") (pintype "passive"))
      (node (ref "PSU3") (pin "7") (pinfunction "GND_7") (pintype "passive"))
      (node (ref "PSU3") (pin "9") (pinfunction "EP_9") (pintype "passive"))
      (node (ref "PWMS") (pin "12") (pinfunction "GND_12") (pintype "passive"))
      (node (ref "PWMS") (pin "3") (pinfunction "GND_3") (pintype "passive"))
      (node (ref "PWMS") (pin "6") (pinfunction "GND_6") (pintype "passive"))
      (node (ref "PWMS") (pin "9") (pinfunction "GND_9") (pintype "passive"))
      (node (ref "PWR") (pin "2") (pinfunction "2_2") (pintype "passive"))
      (node (ref "R11") (pin "1") (pinfunction "1_1") (pintype "passive"))
      (node (ref "R15") (pin "1") (pinfunction "1_1") (pintype "passive"))
      (node (ref "R17") (pin "1") (pinfunction "1_1") (pintype "passive"))
      (node (ref "R19") (pin "1") (pinfunction "1_1") (pintype "passive"))
      (node (ref "R28") (pin "2") (pinfunction "2_2") (pintype "passive"))
      (node (ref "R31") (pin "1") (pinfunction "1_1") (pintype "passive"))
      (node (ref "R36") (pin "1") (pinfunction "1_1") (pintype "passive"))
      (node (ref "R40") (pin "1") (pinfunction "1_1") (pintype "passive"))
      (node (ref "R45") (pin "1") (pinfunction "1_1") (pintype "passive"))
      (node (ref "R46") (pin "1") (pinfunction "1_1") (pintype "passive"))
      (node (ref "R47") (pin "1") (pinfunction "1_1") (pintype "passive"))
      (node (ref "R48") (pin "1") (pinfunction "1_1") (pintype "passive"))
      (node (ref "R49") (pin "1") (pinfunction "1_1") (pintype "passive"))
      (node (ref "R50") (pin "1") (pinfunction "1_1") (pintype "passive"))
      (node (ref "SBUS") (pin "1") (pinfunction "GND_1") (pintype "passive"))
      (node (ref "SD") (pin "10") (pinfunction "GND_10") (pintype "passive"))
      (node (ref "SD") (pin "6") (pinfunction "VSS_6") (pintype "passive"))
      (node (ref "SI1") (pin "2") (pinfunction "B_2") (pintype "passive"))
      (node (ref "SI2") (pin "2") (pinfunction "B_2") (pintype "passive"))
      (node (ref "SI3") (pin "2") (pinfunction "B_2") (pintype "passive"))
      (node (ref "SI4") (pin "2") (pinfunction "B_2") (pintype "passive"))
      (node (ref "TYPE-C") (pin "0") (pinfunction "GND_0") (pintype "passive"))
      (node (ref "TYPE-C") (pin "A12") (pinfunction "GND_A12") (pintype "passive"))
      (node (ref "TYPE-C") (pin "B12") (pinfunction "GND_B12") (pintype "passive"))
      (node (ref "USB0") (pin "4") (pinfunction "GND_4") (pintype "passive"))
      (node (ref "USB1") (pin "4") (pinfunction "GND_4") (pintype "passive"))
      (node (ref "USB2") (pin "4") (pinfunction "GND_4") (pintype "passive"))
      (node (ref "USB3") (pin "4") (pinfunction "GND_4") (pintype "passive"))
    )
    (net (code "101") (name "Net-(ADC-ADCA0)") (class "Default")
      (node (ref "ADC") (pin "1") (pinfunction "ADCA0_1") (pintype "passive"))
      (node (ref "R1") (pin "2") (pinfunction "2_2") (pintype "passive"))
    )
    (net (code "102") (name "Net-(ADC-ADCA1)") (class "Default")
      (node (ref "ADC") (pin "2") (pinfunction "ADCA1_2") (pintype "passive"))
      (node (ref "R2") (pin "2") (pinfunction "2_2") (pintype "passive"))
    )
    (net (code "103") (name "Net-(ADC-ADCA2)") (class "Default")
      (node (ref "ADC") (pin "3") (pinfunction "ADCA2_3") (pintype "passive"))
      (node (ref "R3") (pin "2") (pinfunction "2_2") (pintype "passive"))
    )
    (net (code "104") (name "Net-(ADC-ADCA3)") (class "Default")
      (node (ref "ADC") (pin "4") (pinfunction "ADCA3_4") (pintype "passive"))
      (node (ref "R4") (pin "2") (pinfunction "2_2") (pintype "passive"))
    )
    (net (code "105") (name "Net-(ADC-ADCA4)") (class "Default")
      (node (ref "ADC") (pin "5") (pinfunction "ADCA4_5") (pintype "passive"))
      (node (ref "R5") (pin "2") (pinfunction "2_2") (pintype "passive"))
    )
    (net (code "106") (name "Net-(ADC-ADCA5)") (class "Default")
      (node (ref "ADC") (pin "6") (pinfunction "ADCA5_6") (pintype "passive"))
      (node (ref "R6") (pin "2") (pinfunction "2_2") (pintype "passive"))
    )
    (net (code "107") (name "Net-(ADC-ADCB0)") (class "Default")
      (node (ref "ADC") (pin "7") (pinfunction "ADCB0_7") (pintype "passive"))
      (node (ref "R7") (pin "2") (pinfunction "2_2") (pintype "passive"))
    )
    (net (code "108") (name "Net-(ADC-ADCB1)") (class "Default")
      (node (ref "ADC") (pin "8") (pinfunction "ADCB1_8") (pintype "passive"))
      (node (ref "R8") (pin "2") (pinfunction "2_2") (pintype "passive"))
    )
    (net (code "109") (name "Net-(AN-LIM)") (class "Default")
      (node (ref "AN") (pin "5") (pinfunction "LIM_5") (pintype "passive"))
      (node (ref "R50") (pin "2") (pinfunction "2_2") (pintype "passive"))
    )
    (net (code "110") (name "Net-(C10-Pad2)") (class "Default")
      (node (ref "C10") (pin "2") (pinfunction "2_2") (pintype "passive"))
      (node (ref "R32") (pin "1") (pinfunction "1_1") (pintype "passive"))
    )
    (net (code "111") (name "Net-(C13-Pad2)") (class "Default")
      (node (ref "C13") (pin "2") (pinfunction "2_2") (pintype "passive"))
      (node (ref "R29") (pin "1") (pinfunction "1_1") (pintype "passive"))
    )
    (net (code "112") (name "Net-(C25-Pad2)") (class "Default")
      (node (ref "C25") (pin "2") (pinfunction "2_2") (pintype "passive"))
      (node (ref "R33") (pin "1") (pinfunction "1_1") (pintype "passive"))
    )
    (net (code "113") (name "Net-(C28-Pad2)") (class "Default")
      (node (ref "C28") (pin "2") (pinfunction "2_2") (pintype "passive"))
      (node (ref "R34") (pin "1") (pinfunction "1_1") (pintype "passive"))
    )
    (net (code "114") (name "Net-(C40-Pad2)") (class "Default")
      (node (ref "C40") (pin "2") (pinfunction "2_2") (pintype "passive"))
      (node (ref "R37") (pin "1") (pinfunction "1_1") (pintype "passive"))
    )
    (net (code "115") (name "Net-(C43-Pad2)") (class "Default")
      (node (ref "C43") (pin "2") (pinfunction "2_2") (pintype "passive"))
      (node (ref "R38") (pin "1") (pinfunction "1_1") (pintype "passive"))
    )
    (net (code "116") (name "Net-(CM4AA-PI_LED_nPWR)") (class "Default")
      (node (ref "CM4A") (pin "95") (pinfunction "PI_LED_nPWR_95") (pintype "passive"))
      (node (ref "LED2") (pin "1") (pinfunction "1_1") (pintype "passive"))
    )
    (net (code "117") (name "Net-(CM4AA-Pi_nLED_Activity)") (class "Default")
      (node (ref "CM4A") (pin "21") (pinfunction "Pi_nLED_Activity_21") (pintype "passive"))
      (node (ref "LED1") (pin "2") (pinfunction "2_2") (pintype "passive"))
    )
    (net (code "118") (name "Net-(JTAG-EMU0)") (class "Default")
      (node (ref "JTAG") (pin "13") (pinfunction "EMU0_13") (pintype "passive"))
      (node (ref "R10") (pin "2") (pinfunction "2_2") (pintype "passive"))
    )
    (net (code "119") (name "Net-(JTAG-EMU1)") (class "Default")
      (node (ref "JTAG") (pin "14") (pinfunction "EMU1_14") (pintype "passive"))
      (node (ref "R9") (pin "2") (pinfunction "2_2") (pintype "passive"))
    )
    (net (code "120") (name "Net-(L1-T4)") (class "Default")
      (node (ref "L1") (pin "1") (pinfunction "T4_1") (pintype "passive"))
      (node (ref "PSU1") (pin "8") (pinfunction "SW_8") (pintype "passive"))
      (node (ref "R32") (pin "2") (pinfunction "2_2") (pintype "passive"))
    )
    (net (code "121") (name "Net-(L2-T4)") (class "Default")
      (node (ref "L2") (pin "1") (pinfunction "T4_1") (pintype "passive"))
      (node (ref "PSU2") (pin "8") (pinfunction "SW_8") (pintype "passive"))
      (node (ref "R33") (pin "2") (pinfunction "2_2") (pintype "passive"))
    )
    (net (code "122") (name "Net-(L3-T4)") (class "Default")
      (node (ref "L3") (pin "1") (pinfunction "T4_1") (pintype "passive"))
      (node (ref "PSU3") (pin "8") (pinfunction "SW_8") (pintype "passive"))
      (node (ref "R37") (pin "2") (pinfunction "2_2") (pintype "passive"))
    )
    (net (code "123") (name "Net-(LED1-Pad1)") (class "Default")
      (node (ref "LED1") (pin "1") (pinfunction "1_1") (pintype "passive"))
      (node (ref "R52") (pin "2") (pinfunction "2_2") (pintype "passive"))
    )
    (net (code "124") (name "Net-(LED2-Pad2)") (class "Default")
      (node (ref "LED2") (pin "2") (pinfunction "2_2") (pintype "passive"))
      (node (ref "R51") (pin "1") (pinfunction "1_1") (pintype "passive"))
    )
    (net (code "125") (name "Net-(PSU1-BST)") (class "Default")
      (node (ref "C10") (pin "1") (pinfunction "1_1") (pintype "passive"))
      (node (ref "PSU1") (pin "1") (pinfunction "BST_1") (pintype "passive"))
    )
    (net (code "126") (name "Net-(PSU1-COMP)") (class "Default")
      (node (ref "C12") (pin "2") (pinfunction "2_2") (pintype "passive"))
      (node (ref "PSU1") (pin "6") (pinfunction "COMP_6") (pintype "passive"))
      (node (ref "R29") (pin "2") (pinfunction "2_2") (pintype "passive"))
    )
    (net (code "127") (name "Net-(PSU1-FB)") (class "Default")
      (node (ref "C14") (pin "1") (pinfunction "1_1") (pintype "passive"))
      (node (ref "PSU1") (pin "5") (pinfunction "FB_5") (pintype "passive"))
      (node (ref "R30") (pin "1") (pinfunction "1_1") (pintype "passive"))
      (node (ref "R31") (pin "2") (pinfunction "2_2") (pintype "passive"))
    )
    (net (code "128") (name "Net-(PSU1-SS)") (class "Default")
      (node (ref "C11") (pin "2") (pinfunction "2_2") (pintype "passive"))
      (node (ref "PSU1") (pin "4") (pinfunction "SS_4") (pintype "passive"))
    )
    (net (code "129") (name "Net-(PSU2-BST)") (class "Default")
      (node (ref "C25") (pin "1") (pinfunction "1_1") (pintype "passive"))
      (node (ref "PSU2") (pin "1") (pinfunction "BST_1") (pintype "passive"))
    )
    (net (code "130") (name "Net-(PSU2-COMP)") (class "Default")
      (node (ref "C27") (pin "2") (pinfunction "2_2") (pintype "passive"))
      (node (ref "PSU2") (pin "6") (pinfunction "COMP_6") (pintype "passive"))
      (node (ref "R34") (pin "2") (pinfunction "2_2") (pintype "passive"))
    )
    (net (code "131") (name "Net-(PSU2-FB)") (class "Default")
      (node (ref "C29") (pin "1") (pinfunction "1_1") (pintype "passive"))
      (node (ref "PSU2") (pin "5") (pinfunction "FB_5") (pintype "passive"))
      (node (ref "R35") (pin "1") (pinfunction "1_1") (pintype "passive"))
      (node (ref "R36") (pin "2") (pinfunction "2_2") (pintype "passive"))
    )
    (net (code "132") (name "Net-(PSU2-SS)") (class "Default")
      (node (ref "C26") (pin "2") (pinfunction "2_2") (pintype "passive"))
      (node (ref "PSU2") (pin "4") (pinfunction "SS_4") (pintype "passive"))
    )
    (net (code "133") (name "Net-(PSU3-BST)") (class "Default")
      (node (ref "C40") (pin "1") (pinfunction "1_1") (pintype "passive"))
      (node (ref "PSU3") (pin "1") (pinfunction "BST_1") (pintype "passive"))
    )
    (net (code "134") (name "Net-(PSU3-COMP)") (class "Default")
      (node (ref "C42") (pin "2") (pinfunction "2_2") (pintype "passive"))
      (node (ref "PSU3") (pin "6") (pinfunction "COMP_6") (pintype "passive"))
      (node (ref "R38") (pin "2") (pinfunction "2_2") (pintype "passive"))
    )
    (net (code "135") (name "Net-(PSU3-FB)") (class "Default")
      (node (ref "C44") (pin "1") (pinfunction "1_1") (pintype "passive"))
      (node (ref "PSU3") (pin "5") (pinfunction "FB_5") (pintype "passive"))
      (node (ref "R39") (pin "1") (pinfunction "1_1") (pintype "passive"))
      (node (ref "R40") (pin "2") (pinfunction "2_2") (pintype "passive"))
    )
    (net (code "136") (name "Net-(PSU3-SS)") (class "Default")
      (node (ref "C41") (pin "2") (pinfunction "2_2") (pintype "passive"))
      (node (ref "PSU3") (pin "4") (pinfunction "SS_4") (pintype "passive"))
    )
    (net (code "137") (name "Net-(R14-Pad1)") (class "Default")
      (node (ref "R14") (pin "1") (pinfunction "1_1") (pintype "passive"))
      (node (ref "R15") (pin "2") (pinfunction "2_2") (pintype "passive"))
      (node (ref "SI1") (pin "1") (pinfunction "B_1") (pintype "passive"))
    )
    (net (code "138") (name "Net-(R16-Pad1)") (class "Default")
      (node (ref "R16") (pin "1") (pinfunction "1_1") (pintype "passive"))
      (node (ref "R17") (pin "2") (pinfunction "2_2") (pintype "passive"))
      (node (ref "SI2") (pin "1") (pinfunction "B_1") (pintype "passive"))
    )
    (net (code "139") (name "Net-(R18-Pad1)") (class "Default")
      (node (ref "R18") (pin "1") (pinfunction "1_1") (pintype "passive"))
      (node (ref "R19") (pin "2") (pinfunction "2_2") (pintype "passive"))
      (node (ref "SI3") (pin "1") (pinfunction "B_1") (pintype "passive"))
    )
    (net (code "140") (name "Net-(R20-Pad1)") (class "Default")
      (node (ref "R20") (pin "1") (pinfunction "1_1") (pintype "passive"))
      (node (ref "R21") (pin "1") (pinfunction "1_1") (pintype "passive"))
      (node (ref "RGB") (pin "1") (pinfunction "VCC_1") (pintype "passive"))
    )
    (net (code "141") (name "Net-(R20-Pad2)") (class "Default")
      (node (ref "R20") (pin "2") (pinfunction "2_2") (pintype "passive"))
      (node (ref "R21") (pin "2") (pinfunction "2_2") (pintype "passive"))
      (node (ref "SI1") (pin "3") (pinfunction "B_3") (pintype "passive"))
    )
    (net (code "142") (name "Net-(R22-Pad1)") (class "Default")
      (node (ref "R22") (pin "1") (pinfunction "1_1") (pintype "passive"))
      (node (ref "R23") (pin "1") (pinfunction "1_1") (pintype "passive"))
      (node (ref "RGB") (pin "3") (pinfunction "VCC_3") (pintype "passive"))
    )
    (net (code "143") (name "Net-(R22-Pad2)") (class "Default")
      (node (ref "R22") (pin "2") (pinfunction "2_2") (pintype "passive"))
      (node (ref "R23") (pin "2") (pinfunction "2_2") (pintype "passive"))
      (node (ref "SI2") (pin "3") (pinfunction "B_3") (pintype "passive"))
    )
    (net (code "144") (name "Net-(R24-Pad1)") (class "Default")
      (node (ref "R24") (pin "1") (pinfunction "1_1") (pintype "passive"))
      (node (ref "R25") (pin "1") (pinfunction "1_1") (pintype "passive"))
      (node (ref "RGB") (pin "5") (pinfunction "VCC_5") (pintype "passive"))
    )
    (net (code "145") (name "Net-(R24-Pad2)") (class "Default")
      (node (ref "R24") (pin "2") (pinfunction "2_2") (pintype "passive"))
      (node (ref "R25") (pin "2") (pinfunction "2_2") (pintype "passive"))
      (node (ref "SI3") (pin "3") (pinfunction "B_3") (pintype "passive"))
    )
    (net (code "146") (name "Net-(R27-Pad1)") (class "Default")
      (node (ref "R27") (pin "1") (pinfunction "1_1") (pintype "passive"))
      (node (ref "R28") (pin "1") (pinfunction "1_1") (pintype "passive"))
      (node (ref "SI4") (pin "1") (pinfunction "B_1") (pintype "passive"))
    )
    (net (code "147") (name "Net-(SBUS-SBUS)") (class "Default")
      (node (ref "R27") (pin "2") (pinfunction "2_2") (pintype "passive"))
      (node (ref "SBUS") (pin "3") (pinfunction "SBUS_3") (pintype "passive"))
    )
    (net (code "148") (name "Net-(USBHUNB4-HS_IND)") (class "Default")
      (node (ref "R46") (pin "2") (pinfunction "2_2") (pintype "passive"))
      (node (ref "USBHUNB4") (pin "25") (pinfunction "HS_IND_25") (pintype "passive"))
    )
    (net (code "149") (name "Net-(USBHUNB4-RBIAS)") (class "Default")
      (node (ref "R45") (pin "2") (pinfunction "2_2") (pintype "passive"))
      (node (ref "USBHUNB4") (pin "35") (pinfunction "RBIAS_35") (pintype "passive"))
    )
    (net (code "150") (name "Net-(USBHUNB4-SCL)") (class "Default")
      (node (ref "R49") (pin "2") (pinfunction "2_2") (pintype "passive"))
      (node (ref "USBHUNB4") (pin "24") (pinfunction "SCL_24") (pintype "passive"))
    )
    (net (code "151") (name "Net-(USBHUNB4-SDA)") (class "Default")
      (node (ref "R48") (pin "2") (pinfunction "2_2") (pintype "passive"))
      (node (ref "USBHUNB4") (pin "22") (pinfunction "SDA_22") (pintype "passive"))
    )
    (net (code "152") (name "Net-(USBHUNB4-SUSP_IND)") (class "Default")
      (node (ref "R47") (pin "2") (pinfunction "2_2") (pintype "passive"))
      (node (ref "USBHUNB4") (pin "28") (pinfunction "SUSP_IND_28") (pintype "passive"))
    )
    (net (code "153") (name "Net-(USBHUNB4-XTIN)") (class "Default")
      (node (ref "C52") (pin "2") (pinfunction "2_2") (pintype "passive"))
      (node (ref "USBHUNB4") (pin "33") (pinfunction "XTIN_33") (pintype "passive"))
      (node (ref "XT1") (pin "1") (pinfunction "1_1") (pintype "passive"))
    )
    (net (code "154") (name "Net-(USBHUNB4-XTOUT)") (class "Default")
      (node (ref "C53") (pin "2") (pinfunction "2_2") (pintype "passive"))
      (node (ref "USBHUNB4") (pin "32") (pinfunction "XTOUT_32") (pintype "passive"))
      (node (ref "XT1") (pin "2") (pinfunction "2_2") (pintype "passive"))
    )
    (net (code "155") (name "unconnected-(C2000A-EM1D13{slash}CANTXA{slash}SCIRXDB{slash}SPICLKC{slash}GPIO71-PadA27)") (class "Default")
      (node (ref "C2000") (pin "A27") (pinfunction "EM1D13/CANTXA/SCIRXDB/SPICLKC/GPIO71_A27") (pintype "passive"))
    )
    (net (code "156") (name "unconnected-(C2000A-EM1D14{slash}CANRXA{slash}SCITXDB{slash}SPISOMIC{slash}GPIO70-PadA29)") (class "Default")
      (node (ref "C2000") (pin "A29") (pinfunction "EM1D14/CANRXA/SCITXDB/SPISOMIC/GPIO70_A29") (pintype "passive"))
    )
    (net (code "157") (name "unconnected-(C2000A-EM1D15{slash}SCLB{slash}SPISIMOC{slash}GPIO69-PadA31)") (class "Default")
      (node (ref "C2000") (pin "A31") (pinfunction "EM1D15/SCLB/SPISIMOC/GPIO69_A31") (pintype "passive"))
    )
    (net (code "158") (name "unconnected-(C2000A-EM1D16{slash}EM2D0{slash}GPIO68-PadA33)") (class "Default")
      (node (ref "C2000") (pin "A33") (pinfunction "EM1D16/EM2D0/GPIO68_A33") (pintype "passive"))
    )
    (net (code "159") (name "unconnected-(C2000A-EM1D17{slash}EM2D1{slash}GPIO67-PadA35)") (class "Default")
      (node (ref "C2000") (pin "A35") (pinfunction "EM1D17/EM2D1/GPIO67_A35") (pintype "passive"))
    )
    (net (code "160") (name "unconnected-(C2000A-EM1D18{slash}EM2D2{slash}SDAB{slash}~{SPISTEB}{slash}GPIO66-PadA37)") (class "Default")
      (node (ref "C2000") (pin "A37") (pinfunction "EM1D18/EM2D2/SDAB/~{SPISTEB}/GPIO66_A37") (pintype "passive"))
    )
    (net (code "161") (name "unconnected-(C2000A-EM1D19{slash}EM2D3{slash}EQEP3I{slash}SCITXDA{slash}SPICLKB{slash}GPIO65-PadA39)") (class "Default")
      (node (ref "C2000") (pin "A39") (pinfunction "EM1D19/EM2D3/EQEP3I/SCITXDA/SPICLKB/GPIO65_A39") (pintype "passive"))
    )
    (net (code "162") (name "unconnected-(C2000A-EM1D20{slash}EM2D4{slash}EQEP3S{slash}SCIRXDA{slash}SPISOMIB{slash}GPIO64-PadA41)") (class "Default")
      (node (ref "C2000") (pin "A41") (pinfunction "EM1D20/EM2D4/EQEP3S/SCIRXDA/SPISOMIB/GPIO64_A41") (pintype "passive"))
    )
    (net (code "163") (name "unconnected-(C2000A-GPIO72{slash}EM1D12{slash}CANTXB{slash}SCITXDC{slash}~{SPISTEC}-PadA25)") (class "Default")
      (node (ref "C2000") (pin "A25") (pinfunction "GPIO72/EM1D12/CANTXB/SCITXDC/~{SPISTEC}_A25") (pintype "passive"))
    )
    (net (code "164") (name "unconnected-(C2000A-GPIO73{slash}EM1D11{slash}XCLKOUT{slash}CANRXB{slash}SCIRXDC-PadA23)") (class "Default")
      (node (ref "C2000") (pin "A23") (pinfunction "GPIO73/EM1D11/XCLKOUT/CANRXB/SCIRXDC_A23") (pintype "passive"))
    )
    (net (code "165") (name "unconnected-(C2000A-GPIO74{slash}EM1D10-PadA21)") (class "Default")
      (node (ref "C2000") (pin "A21") (pinfunction "GPIO74/EM1D10_A21") (pintype "passive"))
    )
    (net (code "166") (name "unconnected-(C2000A-GPIO75{slash}EM1D9-PadA19)") (class "Default")
      (node (ref "C2000") (pin "A19") (pinfunction "GPIO75/EM1D9_A19") (pintype "passive"))
    )
    (net (code "167") (name "unconnected-(C2000A-GPIO76{slash}EM1D8{slash}SCITXDD-PadA17)") (class "Default")
      (node (ref "C2000") (pin "A17") (pinfunction "GPIO76/EM1D8/SCITXDD_A17") (pintype "passive"))
    )
    (net (code "168") (name "unconnected-(C2000A-GPIO77{slash}EM1D7{slash}SCIRXDD-PadA15)") (class "Default")
      (node (ref "C2000") (pin "A15") (pinfunction "GPIO77/EM1D7/SCIRXDD_A15") (pintype "passive"))
    )
    (net (code "169") (name "unconnected-(C2000A-GPIO78{slash}EM1D6{slash}EQEP2A-PadA13)") (class "Default")
      (node (ref "C2000") (pin "A13") (pinfunction "GPIO78/EM1D6/EQEP2A_A13") (pintype "passive"))
    )
    (net (code "170") (name "unconnected-(C2000A-GPIO79{slash}EM1D5{slash}EQEP2B-PadA11)") (class "Default")
      (node (ref "C2000") (pin "A11") (pinfunction "GPIO79/EM1D5/EQEP2B_A11") (pintype "passive"))
    )
    (net (code "171") (name "unconnected-(C2000A-GPIO80{slash}EM1D4{slash}EQEP2S-PadA9)") (class "Default")
      (node (ref "C2000") (pin "A9") (pinfunction "GPIO80/EM1D4/EQEP2S_A9") (pintype "passive"))
    )
    (net (code "172") (name "unconnected-(C2000A-GPIO81{slash}EM1D3{slash}EQEP2I-PadA7)") (class "Default")
      (node (ref "C2000") (pin "A7") (pinfunction "GPIO81/EM1D3/EQEP2I_A7") (pintype "passive"))
    )
    (net (code "173") (name "unconnected-(C2000A-GPIO82{slash}EM1D2-PadA5)") (class "Default")
      (node (ref "C2000") (pin "A5") (pinfunction "GPIO82/EM1D2_A5") (pintype "passive"))
    )
    (net (code "174") (name "unconnected-(C2000A-GPIO83{slash}EM1D1-PadA3)") (class "Default")
      (node (ref "C2000") (pin "A3") (pinfunction "GPIO83/EM1D1_A3") (pintype "passive"))
    )
    (net (code "175") (name "unconnected-(C2000A-GPIO85{slash}EM1D0{slash}SCIRXDA{slash}MDRB{slash}MDRA-PadA1)") (class "Default")
      (node (ref "C2000") (pin "A1") (pinfunction "GPIO85/EM1D0/SCIRXDA/MDRB/MDRA_A1") (pintype "passive"))
    )
    (net (code "176") (name "unconnected-(C2000A-GPIO142{slash}SCITXDD-PadA58)") (class "Default")
      (node (ref "C2000") (pin "A58") (pinfunction "GPIO142/SCITXDD_A58") (pintype "passive"))
    )
    (net (code "177") (name "unconnected-(C2000A-GPIO143-PadA56)") (class "Default")
      (node (ref "C2000") (pin "A56") (pinfunction "GPIO143_A56") (pintype "passive"))
    )
    (net (code "178") (name "unconnected-(C2000A-GPIO144-PadA54)") (class "Default")
      (node (ref "C2000") (pin "A54") (pinfunction "GPIO144_A54") (pintype "passive"))
    )
    (net (code "179") (name "unconnected-(C2000A-GPIO145{slash}EPWM1A-PadA50)") (class "Default")
      (node (ref "C2000") (pin "A50") (pinfunction "GPIO145/EPWM1A_A50") (pintype "passive"))
    )
    (net (code "180") (name "unconnected-(C2000A-GPIO146{slash}EPWM1B-PadA48)") (class "Default")
      (node (ref "C2000") (pin "A48") (pinfunction "GPIO146/EPWM1B_A48") (pintype "passive"))
    )
    (net (code "181") (name "unconnected-(C2000A-GPIO147{slash}EPWM2A-PadA46)") (class "Default")
      (node (ref "C2000") (pin "A46") (pinfunction "GPIO147/EPWM2A_A46") (pintype "passive"))
    )
    (net (code "182") (name "unconnected-(C2000A-GPIO148{slash}EPWM2B-PadA44)") (class "Default")
      (node (ref "C2000") (pin "A44") (pinfunction "GPIO148/EPWM2B_A44") (pintype "passive"))
    )
    (net (code "183") (name "unconnected-(C2000A-GPIO149{slash}EPWM3A-PadA42)") (class "Default")
      (node (ref "C2000") (pin "A42") (pinfunction "GPIO149/EPWM3A_A42") (pintype "passive"))
    )
    (net (code "184") (name "unconnected-(C2000A-GPIO150{slash}EPWM3B-PadA40)") (class "Default")
      (node (ref "C2000") (pin "A40") (pinfunction "GPIO150/EPWM3B_A40") (pintype "passive"))
    )
    (net (code "185") (name "unconnected-(C2000A-GPIO151{slash}EPWM4A-PadA38)") (class "Default")
      (node (ref "C2000") (pin "A38") (pinfunction "GPIO151/EPWM4A_A38") (pintype "passive"))
    )
    (net (code "186") (name "unconnected-(C2000A-GPIO152{slash}EPWM4B-PadA36)") (class "Default")
      (node (ref "C2000") (pin "A36") (pinfunction "GPIO152/EPWM4B_A36") (pintype "passive"))
    )
    (net (code "187") (name "unconnected-(C2000A-GPIO153{slash}EPWM5A-PadA34)") (class "Default")
      (node (ref "C2000") (pin "A34") (pinfunction "GPIO153/EPWM5A_A34") (pintype "passive"))
    )
    (net (code "188") (name "unconnected-(C2000A-GPIO154{slash}EPWM5B-PadA32)") (class "Default")
      (node (ref "C2000") (pin "A32") (pinfunction "GPIO154/EPWM5B_A32") (pintype "passive"))
    )
    (net (code "189") (name "unconnected-(C2000A-GPIO156{slash}EPWM6B-PadA28)") (class "Default")
      (node (ref "C2000") (pin "A28") (pinfunction "GPIO156/EPWM6B_A28") (pintype "passive"))
    )
    (net (code "190") (name "unconnected-(C2000A-GPIO158{slash}EPWM7B-PadA24)") (class "Default")
      (node (ref "C2000") (pin "A24") (pinfunction "GPIO158/EPWM7B_A24") (pintype "passive"))
    )
    (net (code "191") (name "unconnected-(C2000A-GPIO160{slash}EPWM8B-PadA20)") (class "Default")
      (node (ref "C2000") (pin "A20") (pinfunction "GPIO160/EPWM8B_A20") (pintype "passive"))
    )
    (net (code "192") (name "unconnected-(C2000A-GPIO162{slash}EPWM9B-PadA16)") (class "Default")
      (node (ref "C2000") (pin "A16") (pinfunction "GPIO162/EPWM9B_A16") (pintype "passive"))
    )
    (net (code "193") (name "unconnected-(C2000A-GPIO164{slash}EPWM10B-PadA12)") (class "Default")
      (node (ref "C2000") (pin "A12") (pinfunction "GPIO164/EPWM10B_A12") (pintype "passive"))
    )
    (net (code "194") (name "unconnected-(C2000A-GPIO166{slash}EPWM11B-PadA8)") (class "Default")
      (node (ref "C2000") (pin "A8") (pinfunction "GPIO166/EPWM11B_A8") (pintype "passive"))
    )
    (net (code "195") (name "unconnected-(C2000A-GPIO168{slash}EPWM12B-PadA4)") (class "Default")
      (node (ref "C2000") (pin "A4") (pinfunction "GPIO168/EPWM12B_A4") (pintype "passive"))
    )
    (net (code "196") (name "unconnected-(C2000A-MCLKRB{slash}EM1D24{slash}EM2D8{slash}OUTPUTXBAR3{slash}SPISIMOB{slash}SD2_D3{slash}SPICLKA{slash}GPIO60-PadA49)") (class "Default")
      (node (ref "C2000") (pin "A49") (pinfunction "MCLKRB/EM1D24/EM2D8/OUTPUTXBAR3/SPISIMOB/SD2_D3/SPICLKA/GPIO60_A49") (pintype "passive"))
    )
    (net (code "197") (name "unconnected-(C2000A-MFSRA{slash}EM1D25{slash}EM2D9{slash}OUTPUTXBAR2{slash}~{SPISTEB}{slash}SD2_C2{slash}SPISOMIA{slash}GPIO59-PadA51)") (class "Default")
      (node (ref "C2000") (pin "A51") (pinfunction "MFSRA/EM1D25/EM2D9/OUTPUTXBAR2/~{SPISTEB}/SD2_C2/SPISOMIA/GPIO59_A51") (pintype "passive"))
    )
    (net (code "198") (name "unconnected-(C2000A-MFSRB{slash}EM1D23{slash}EM2D7{slash}OUTPUTXBAR4{slash}SPISOMIB{slash}SD2_C3{slash}~{SPISTEA}{slash}GPIO61-PadA47)") (class "Default")
      (node (ref "C2000") (pin "A47") (pinfunction "MFSRB/EM1D23/EM2D7/OUTPUTXBAR4/SPISOMIB/SD2_C3/~{SPISTEA}/GPIO61_A47") (pintype "passive"))
    )
    (net (code "199") (name "unconnected-(C2000A-SCIRXDC{slash}EM1D22{slash}EM2D6{slash}EQEP3A{slash}CANRXA{slash}SD2_D4{slash}GPIO62-PadA45)") (class "Default")
      (node (ref "C2000") (pin "A45") (pinfunction "SCIRXDC/EM1D22/EM2D6/EQEP3A/CANRXA/SD2_D4/GPIO62_A45") (pintype "passive"))
    )
    (net (code "200") (name "unconnected-(C2000A-SCITXDC{slash}EM1D21{slash}EM2D5{slash}EQEP3B{slash}CANTXA{slash}SD2_C4{slash}SPISIMOB{slash}GPIO63-PadA43)") (class "Default")
      (node (ref "C2000") (pin "A43") (pinfunction "SCITXDC/EM1D21/EM2D5/EQEP3B/CANTXA/SD2_C4/SPISIMOB/GPIO63_A43") (pintype "passive"))
    )
    (net (code "201") (name "unconnected-(C2000B-EM2A0{slash}EQEP1S{slash}GPIO98-PadB6)") (class "Default")
      (node (ref "C2000") (pin "B6") (pinfunction "EM2A0/EQEP1S/GPIO98_B6") (pintype "passive"))
    )
    (net (code "202") (name "unconnected-(C2000B-EM2A1{slash}EQEP1I{slash}GPIO99-PadB8)") (class "Default")
      (node (ref "C2000") (pin "B8") (pinfunction "EM2A1/EQEP1I/GPIO99_B8") (pintype "passive"))
    )
    (net (code "203") (name "unconnected-(C2000B-EM2A2{slash}EQEP2A{slash}SPISIMOC{slash}GPIO100-PadB14)") (class "Default")
      (node (ref "C2000") (pin "B14") (pinfunction "EM2A2/EQEP2A/SPISIMOC/GPIO100_B14") (pintype "passive"))
    )
    (net (code "204") (name "unconnected-(C2000B-EM2A3{slash}EQEP2B{slash}SPISOMIC{slash}GPIO101-PadB12)") (class "Default")
      (node (ref "C2000") (pin "B12") (pinfunction "EM2A3/EQEP2B/SPISOMIC/GPIO101_B12") (pintype "passive"))
    )
    (net (code "205") (name "unconnected-(C2000B-EM2A4{slash}EQEP2S{slash}SPICLKC{slash}GPIO102-PadB10)") (class "Default")
      (node (ref "C2000") (pin "B10") (pinfunction "EM2A4/EQEP2S/SPICLKC/GPIO102_B10") (pintype "passive"))
    )
    (net (code "206") (name "unconnected-(C2000B-EM2A5{slash}EQEP2I{slash}~{SPISTEC}{slash}GPIO103-PadB16)") (class "Default")
      (node (ref "C2000") (pin "B16") (pinfunction "EM2A5/EQEP2I/~{SPISTEC}/GPIO103_B16") (pintype "passive"))
    )
    (net (code "207") (name "unconnected-(C2000B-EM2DQM0{slash}EQEP1B{slash}GPIO97-PadB4)") (class "Default")
      (node (ref "C2000") (pin "B4") (pinfunction "EM2DQM0/EQEP1B/GPIO97_B4") (pintype "passive"))
    )
    (net (code "208") (name "unconnected-(C2000B-EM2DQM1{slash}EQEP1A{slash}GPIO96-PadB2)") (class "Default")
      (node (ref "C2000") (pin "B2") (pinfunction "EM2DQM1/EQEP1A/GPIO96_B2") (pintype "passive"))
    )
    (net (code "209") (name "unconnected-(C2000B-EPWM1B{slash}MFSRB{slash}SCLA{slash}GPIO1-PadB36)") (class "Default")
      (node (ref "C2000") (pin "B36") (pinfunction "EPWM1B/MFSRB/SCLA/GPIO1_B36") (pintype "passive"))
    )
    (net (code "210") (name "unconnected-(C2000B-EPWM2B{slash}OUTPUTXBAR2{slash}SCLB{slash}MCLKRB{slash}GPIO3-PadB28)") (class "Default")
      (node (ref "C2000") (pin "B28") (pinfunction "EPWM2B/OUTPUTXBAR2/SCLB/MCLKRB/GPIO3_B28") (pintype "passive"))
    )
    (net (code "211") (name "unconnected-(C2000B-EPWM6A{slash}CANRXB{slash}ADCSOCBO{slash}EQEP1A{slash}SCITXDB{slash}UPP-WAIT{slash}GPIO10-PadB59)") (class "Default")
      (node (ref "C2000") (pin "B59") (pinfunction "EPWM6A/CANRXB/ADCSOCBO/EQEP1A/SCITXDB/UPP-WAIT/GPIO10_B59") (pintype "passive"))
    )
    (net (code "212") (name "unconnected-(C2000B-EPWM6B{slash}SCIRXDB{slash}OUTPUTXBAR7{slash}EQEP1B{slash}UPP-STRT{slash}GPIO11-PadB57)") (class "Default")
      (node (ref "C2000") (pin "B57") (pinfunction "EPWM6B/SCIRXDB/OUTPUTXBAR7/EQEP1B/UPP-STRT/GPIO11_B57") (pintype "passive"))
    )
    (net (code "213") (name "unconnected-(C2000B-EPWM7A{slash}CANTXB{slash}MDXB{slash}EQEP1S{slash}SCITXDC{slash}UPP-ENA{slash}GPIO12-PadB55)") (class "Default")
      (node (ref "C2000") (pin "B55") (pinfunction "EPWM7A/CANTXB/MDXB/EQEP1S/SCITXDC/UPP-ENA/GPIO12_B55") (pintype "passive"))
    )
    (net (code "214") (name "unconnected-(C2000B-EPWM7B{slash}CANRXB{slash}MDRB{slash}EQEP1I{slash}SCIRXDC{slash}UPP-D7{slash}GPIO13-PadB58)") (class "Default")
      (node (ref "C2000") (pin "B58") (pinfunction "EPWM7B/CANRXB/MDRB/EQEP1I/SCIRXDC/UPP-D7/GPIO13_B58") (pintype "passive"))
    )
    (net (code "215") (name "unconnected-(C2000B-EPWM8A{slash}SCITXDB{slash}MCLKXB{slash}OUTPUTXBAR3{slash}UPP-D6{slash}GPIO14-PadB56)") (class "Default")
      (node (ref "C2000") (pin "B56") (pinfunction "EPWM8A/SCITXDB/MCLKXB/OUTPUTXBAR3/UPP-D6/GPIO14_B56") (pintype "passive"))
    )
    (net (code "216") (name "unconnected-(C2000B-EPWM8B{slash}SCIRXDB{slash}MFSXB{slash}OUTPUTXBAR4{slash}UPP-D5{slash}GPIO15-PadB54)") (class "Default")
      (node (ref "C2000") (pin "B54") (pinfunction "EPWM8B/SCIRXDB/MFSXB/OUTPUTXBAR4/UPP-D5/GPIO15_B54") (pintype "passive"))
    )
    (net (code "217") (name "unconnected-(C2000B-EPWM9A{slash}SPISIMOA{slash}CANTXB{slash}OUTPUTXBAR7{slash}SD1_D1{slash}UPP-D4{slash}GPIO16-PadB52)") (class "Default")
      (node (ref "C2000") (pin "B52") (pinfunction "EPWM9A/SPISIMOA/CANTXB/OUTPUTXBAR7/SD1_D1/UPP-D4/GPIO16_B52") (pintype "passive"))
    )
    (net (code "218") (name "unconnected-(C2000B-EPWM9B{slash}SPISOMIA{slash}CANRXB{slash}OUTPUTXBAR8{slash}SD1_C1{slash}UPP-D3{slash}GPIO17-PadB50)") (class "Default")
      (node (ref "C2000") (pin "B50") (pinfunction "EPWM9B/SPISOMIA/CANRXB/OUTPUTXBAR8/SD1_C1/UPP-D3/GPIO17_B50") (pintype "passive"))
    )
    (net (code "219") (name "unconnected-(C2000B-EPWM10A{slash}SPICLKA{slash}SCITXDB{slash}CANRXA{slash}SD1_D2{slash}UPP-D2{slash}GPIO18-PadB48)") (class "Default")
      (node (ref "C2000") (pin "B48") (pinfunction "EPWM10A/SPICLKA/SCITXDB/CANRXA/SD1_D2/UPP-D2/GPIO18_B48") (pintype "passive"))
    )
    (net (code "220") (name "unconnected-(C2000B-EPWM10B{slash}~{SPISTEA}{slash}SCIRXDB{slash}CANTXA{slash}SD1_C2{slash}UPP-D1{slash}GPIO19-PadB46)") (class "Default")
      (node (ref "C2000") (pin "B46") (pinfunction "EPWM10B/~{SPISTEA}/SCIRXDB/CANTXA/SD1_C2/UPP-D1/GPIO19_B46") (pintype "passive"))
    )
    (net (code "221") (name "unconnected-(C2000B-EPWM11A{slash}EQEP1A{slash}MDXA{slash}CANTXB{slash}SD1_D3{slash}UPP-D0{slash}GPIO20-PadB44)") (class "Default")
      (node (ref "C2000") (pin "B44") (pinfunction "EPWM11A/EQEP1A/MDXA/CANTXB/SD1_D3/UPP-D0/GPIO20_B44") (pintype "passive"))
    )
    (net (code "222") (name "unconnected-(C2000B-EPWM11B{slash}EQEP1B{slash}MDRA{slash}CANRXB{slash}SD1_C3{slash}UPP-CLK{slash}GPIO21-PadB42)") (class "Default")
      (node (ref "C2000") (pin "B42") (pinfunction "EPWM11B/EQEP1B/MDRA/CANRXB/SD1_C3/UPP-CLK/GPIO21_B42") (pintype "passive"))
    )
    (net (code "223") (name "unconnected-(C2000B-EQEP1A{slash}EM1A10{slash}SPISIMOC{slash}SD1_D2{slash}GPIO50-PadB21)") (class "Default")
      (node (ref "C2000") (pin "B21") (pinfunction "EQEP1A/EM1A10/SPISIMOC/SD1_D2/GPIO50_B21") (pintype "passive"))
    )
    (net (code "224") (name "unconnected-(C2000B-EQEP1B{slash}EM1A11{slash}SPISOMIC{slash}SD1_C2{slash}GPIO51-PadB23)") (class "Default")
      (node (ref "C2000") (pin "B23") (pinfunction "EQEP1B/EM1A11/SPISOMIC/SD1_C2/GPIO51_B23") (pintype "passive"))
    )
    (net (code "225") (name "unconnected-(C2000B-EQEP1S{slash}EM1A12{slash}SPICLKC{slash}SD1_D3{slash}GPIO52-PadB25)") (class "Default")
      (node (ref "C2000") (pin "B25") (pinfunction "EQEP1S/EM1A12/SPICLKC/SD1_D3/GPIO52_B25") (pintype "passive"))
    )
    (net (code "226") (name "unconnected-(C2000B-GPIO25{slash}OUTPUTXBAR2{slash}EQEP2B{slash}MDRB{slash}SPISOMIB{slash}SD2_C1-PadB30)") (class "Default")
      (node (ref "C2000") (pin "B30") (pinfunction "GPIO25/OUTPUTXBAR2/EQEP2B/MDRB/SPISOMIB/SD2_C1_B30") (pintype "passive"))
    )
    (net (code "227") (name "unconnected-(C2000B-GPIO26{slash}OUTPUTXBAR3{slash}EQEP2I{slash}MCLKXB{slash}SPICLKB{slash}SD2_D2-PadB32)") (class "Default")
      (node (ref "C2000") (pin "B32") (pinfunction "GPIO26/OUTPUTXBAR3/EQEP2I/MCLKXB/SPICLKB/SD2_D2_B32") (pintype "passive"))
    )
    (net (code "228") (name "unconnected-(C2000B-GPIO27{slash}OUTPUTXBAR4{slash}EQEP2S{slash}MFSXB{slash}~{SPISTEB}{slash}SD2_C2-PadB38)") (class "Default")
      (node (ref "C2000") (pin "B38") (pinfunction "GPIO27/OUTPUTXBAR4/EQEP2S/MFSXB/~{SPISTEB}/SD2_C2_B38") (pintype "passive"))
    )
    (net (code "229") (name "unconnected-(C2000B-GPIO38{slash}EM1A0{slash}SCITXDC{slash}CANTXB-PadB1)") (class "Default")
      (node (ref "C2000") (pin "B1") (pinfunction "GPIO38/EM1A0/SCITXDC/CANTXB_B1") (pintype "passive"))
    )
    (net (code "230") (name "unconnected-(C2000B-GPIO39{slash}EM1A1{slash}SCIRXDC{slash}CANRXB-PadB3)") (class "Default")
      (node (ref "C2000") (pin "B3") (pinfunction "GPIO39/EM1A1/SCIRXDC/CANRXB_B3") (pintype "passive"))
    )
    (net (code "231") (name "unconnected-(C2000B-GPIO40{slash}EM1A2{slash}SDAB-PadB5)") (class "Default")
      (node (ref "C2000") (pin "B5") (pinfunction "GPIO40/EM1A2/SDAB_B5") (pintype "passive"))
    )
    (net (code "232") (name "unconnected-(C2000B-GPIO41{slash}EM1A3{slash}SCLB-PadB7)") (class "Default")
      (node (ref "C2000") (pin "B7") (pinfunction "GPIO41/EM1A3/SCLB_B7") (pintype "passive"))
    )
    (net (code "233") (name "unconnected-(C2000B-GPIO44{slash}EM1A4-PadB9)") (class "Default")
      (node (ref "C2000") (pin "B9") (pinfunction "GPIO44/EM1A4_B9") (pintype "passive"))
    )
    (net (code "234") (name "unconnected-(C2000B-GPIO45{slash}EM1A5-PadB11)") (class "Default")
      (node (ref "C2000") (pin "B11") (pinfunction "GPIO45/EM1A5_B11") (pintype "passive"))
    )
    (net (code "235") (name "unconnected-(C2000B-GPIO46{slash}EM1A6{slash}SCIRXDD-PadB13)") (class "Default")
      (node (ref "C2000") (pin "B13") (pinfunction "GPIO46/EM1A6/SCIRXDD_B13") (pintype "passive"))
    )
    (net (code "236") (name "unconnected-(C2000B-GPIO47{slash}EM1A7{slash}SCITXDD-PadB15)") (class "Default")
      (node (ref "C2000") (pin "B15") (pinfunction "GPIO47/EM1A7/SCITXDD_B15") (pintype "passive"))
    )
    (net (code "237") (name "unconnected-(C2000B-GPIO86{slash}EM1A13{slash}EM1CAS{slash}SCITXDB{slash}MCLKXB{slash}MCLKXA-PadB27)") (class "Default")
      (node (ref "C2000") (pin "B27") (pinfunction "GPIO86/EM1A13/EM1CAS/SCITXDB/MCLKXB/MCLKXA_B27") (pintype "passive"))
    )
    (net (code "238") (name "unconnected-(C2000B-GPIO87{slash}EM1A14{slash}EM1RAS{slash}SCIRXDB{slash}MFSXB{slash}MFSXA-PadB29)") (class "Default")
      (node (ref "C2000") (pin "B29") (pinfunction "GPIO87/EM1A14/EM1RAS/SCIRXDB/MFSXB/MFSXA_B29") (pintype "passive"))
    )
    (net (code "239") (name "unconnected-(C2000B-GPIO88{slash}EM1A15{slash}EM1DQM0-PadB31)") (class "Default")
      (node (ref "C2000") (pin "B31") (pinfunction "GPIO88/EM1A15/EM1DQM0_B31") (pintype "passive"))
    )
    (net (code "240") (name "unconnected-(C2000B-GPIO89{slash}EM1A16{slash}EM1DQM1{slash}SCITXDC-PadB33)") (class "Default")
      (node (ref "C2000") (pin "B33") (pinfunction "GPIO89/EM1A16/EM1DQM1/SCITXDC_B33") (pintype "passive"))
    )
    (net (code "241") (name "unconnected-(C2000B-GPIO90{slash}EM1A17{slash}EM1DQM2{slash}SCIRXDC-PadB35)") (class "Default")
      (node (ref "C2000") (pin "B35") (pinfunction "GPIO90/EM1A17/EM1DQM2/SCIRXDC_B35") (pintype "passive"))
    )
    (net (code "242") (name "unconnected-(C2000B-GPIO91{slash}EMIA18{slash}EM1DQM3{slash}SDAA-PadB37)") (class "Default")
      (node (ref "C2000") (pin "B37") (pinfunction "GPIO91/EMIA18/EM1DQM3/SDAA_B37") (pintype "passive"))
    )
    (net (code "243") (name "unconnected-(C2000B-GPIO92{slash}EM1A19{slash}EM1BA1{slash}SCLA-PadB39)") (class "Default")
      (node (ref "C2000") (pin "B39") (pinfunction "GPIO92/EM1A19/EM1BA1/SCLA_B39") (pintype "passive"))
    )
    (net (code "244") (name "unconnected-(C2000B-GPIO93{slash}EM1BA0{slash}SCITXDD-PadB47)") (class "Default")
      (node (ref "C2000") (pin "B47") (pinfunction "GPIO93/EM1BA0/SCITXDD_B47") (pintype "passive"))
    )
    (net (code "245") (name "unconnected-(C2000B-GPIO95-PadB51)") (class "Default")
      (node (ref "C2000") (pin "B51") (pinfunction "GPIO95_B51") (pintype "passive"))
    )
    (net (code "246") (name "unconnected-(C2000B-OUTPUTXBAR1{slash}EQEP2A{slash}MDXB{slash}SPISIMOB{slash}SD2_D1{slash}GPIO24-PadB34)") (class "Default")
      (node (ref "C2000") (pin "B34") (pinfunction "OUTPUTXBAR1/EQEP2A/MDXB/SPISIMOB/SD2_D1/GPIO24_B34") (pintype "passive"))
    )
    (net (code "247") (name "unconnected-(C2000B-OUTPUTXBAR3{slash}EM1A8{slash}SCITXDA{slash}SD1_D1{slash}GPIO48-PadB17)") (class "Default")
      (node (ref "C2000") (pin "B17") (pinfunction "OUTPUTXBAR3/EM1A8/SCITXDA/SD1_D1/GPIO48_B17") (pintype "passive"))
    )
    (net (code "248") (name "unconnected-(C2000B-OUTPUTXBAR4{slash}EM1A9{slash}SCIRXDA{slash}SD1_C1{slash}GPIO49-PadB19)") (class "Default")
      (node (ref "C2000") (pin "B19") (pinfunction "OUTPUTXBAR4/EM1A9/SCIRXDA/SD1_C1/GPIO49_B19") (pintype "passive"))
    )
    (net (code "249") (name "unconnected-(C2000C-ADCIN14{slash}CMPIN4P-PadC33)") (class "Default")
      (node (ref "C2000") (pin "C33") (pinfunction "ADCIN14/CMPIN4P_C33") (pintype "passive"))
    )
    (net (code "250") (name "unconnected-(C2000C-ADCIN15{slash}CMPIN4N-PadC31)") (class "Default")
      (node (ref "C2000") (pin "C31") (pinfunction "ADCIN15/CMPIN4N_C31") (pintype "passive"))
    )
    (net (code "251") (name "unconnected-(C2000C-ADCINB2{slash}CMPIN3P-PadC23)") (class "Default")
      (node (ref "C2000") (pin "C23") (pinfunction "ADCINB2/CMPIN3P_C23") (pintype "passive"))
    )
    (net (code "252") (name "unconnected-(C2000C-ADCINB3{slash}CMPIN3N-PadC21)") (class "Default")
      (node (ref "C2000") (pin "C21") (pinfunction "ADCINB3/CMPIN3N_C21") (pintype "passive"))
    )
    (net (code "253") (name "unconnected-(C2000C-ADCINB4-PadC19)") (class "Default")
      (node (ref "C2000") (pin "C19") (pinfunction "ADCINB4_C19") (pintype "passive"))
    )
    (net (code "254") (name "unconnected-(C2000C-ADCINB5-PadC17)") (class "Default")
      (node (ref "C2000") (pin "C17") (pinfunction "ADCINB5_C17") (pintype "passive"))
    )
    (net (code "255") (name "unconnected-(C2000C-ADCINC2{slash}CMPIN6P-PadC51)") (class "Default")
      (node (ref "C2000") (pin "C51") (pinfunction "ADCINC2/CMPIN6P_C51") (pintype "passive"))
    )
    (net (code "256") (name "unconnected-(C2000C-ADCINC3{slash}CMPIN6N-PadC53)") (class "Default")
      (node (ref "C2000") (pin "C53") (pinfunction "ADCINC3/CMPIN6N_C53") (pintype "passive"))
    )
    (net (code "257") (name "unconnected-(C2000C-ADCINC4{slash}CMPIN5P-PadC55)") (class "Default")
      (node (ref "C2000") (pin "C55") (pinfunction "ADCINC4/CMPIN5P_C55") (pintype "passive"))
    )
    (net (code "258") (name "unconnected-(C2000C-ADCINC5{slash}CMPIN5N-PadC57)") (class "Default")
      (node (ref "C2000") (pin "C57") (pinfunction "ADCINC5/CMPIN5N_C57") (pintype "passive"))
    )
    (net (code "259") (name "unconnected-(C2000C-ADCIND0{slash}CMPIN7P-PadC13)") (class "Default")
      (node (ref "C2000") (pin "C13") (pinfunction "ADCIND0/CMPIN7P_C13") (pintype "passive"))
    )
    (net (code "260") (name "unconnected-(C2000C-ADCIND1{slash}CMPIN7N-PadC11)") (class "Default")
      (node (ref "C2000") (pin "C11") (pinfunction "ADCIND1/CMPIN7N_C11") (pintype "passive"))
    )
    (net (code "261") (name "unconnected-(C2000C-ADCIND2{slash}CMPIN8P-PadC9)") (class "Default")
      (node (ref "C2000") (pin "C9") (pinfunction "ADCIND2/CMPIN8P_C9") (pintype "passive"))
    )
    (net (code "262") (name "unconnected-(C2000C-ADCIND3{slash}CMPIN8N-PadC7)") (class "Default")
      (node (ref "C2000") (pin "C7") (pinfunction "ADCIND3/CMPIN8N_C7") (pintype "passive"))
    )
    (net (code "263") (name "unconnected-(C2000C-ADCIND4-PadC5)") (class "Default")
      (node (ref "C2000") (pin "C5") (pinfunction "ADCIND4_C5") (pintype "passive"))
    )
    (net (code "264") (name "unconnected-(C2000C-ADCIND5-PadC3)") (class "Default")
      (node (ref "C2000") (pin "C3") (pinfunction "ADCIND5_C3") (pintype "passive"))
    )
    (net (code "265") (name "unconnected-(C2000C-EM2BA0{slash}GPIO111-PadC48)") (class "Default")
      (node (ref "C2000") (pin "C48") (pinfunction "EM2BA0/GPIO111_C48") (pintype "passive"))
    )
    (net (code "266") (name "unconnected-(C2000C-EM2BA1{slash}GPIO112-PadC52)") (class "Default")
      (node (ref "C2000") (pin "C52") (pinfunction "EM2BA1/GPIO112_C52") (pintype "passive"))
    )
    (net (code "267") (name "unconnected-(C2000C-EM2CAS{slash}GPIO113-PadC44)") (class "Default")
      (node (ref "C2000") (pin "C44") (pinfunction "EM2CAS/GPIO113_C44") (pintype "passive"))
    )
    (net (code "268") (name "unconnected-(C2000C-EM2RAS{slash}GPIO114-PadC46)") (class "Default")
      (node (ref "C2000") (pin "C46") (pinfunction "EM2RAS/GPIO114_C46") (pintype "passive"))
    )
    (net (code "269") (name "unconnected-(C2000C-EM2WAIT{slash}GPIO110-PadC54)") (class "Default")
      (node (ref "C2000") (pin "C54") (pinfunction "EM2WAIT/GPIO110_C54") (pintype "passive"))
    )
    (net (code "270") (name "unconnected-(C2000C-EPWM3A{slash}OUTPUTXBAR3{slash}CANTXA{slash}GPIO4-PadC38)") (class "Default")
      (node (ref "C2000") (pin "C38") (pinfunction "EPWM3A/OUTPUTXBAR3/CANTXA/GPIO4_C38") (pintype "passive"))
    )
    (net (code "271") (name "unconnected-(C2000C-EPWM3B{slash}OUTPUTXBAR3{slash}CANRXA{slash}MFSRA{slash}GPIO5-PadC36)") (class "Default")
      (node (ref "C2000") (pin "C36") (pinfunction "EPWM3B/OUTPUTXBAR3/CANRXA/MFSRA/GPIO5_C36") (pintype "passive"))
    )
    (net (code "272") (name "unconnected-(C2000C-EPWM4B{slash}MCLKRA{slash}OUTPUTXBAR5{slash}EQEP3B{slash}CANRXB{slash}GPIO7-PadC30)") (class "Default")
      (node (ref "C2000") (pin "C30") (pinfunction "EPWM4B/MCLKRA/OUTPUTXBAR5/EQEP3B/CANRXB/GPIO7_C30") (pintype "passive"))
    )
    (net (code "273") (name "unconnected-(C2000C-EPWM5A{slash}CANTXB{slash}ADCSOCAO{slash}EQEP3S{slash}SCITXDA{slash}GPIO8-PadC32)") (class "Default")
      (node (ref "C2000") (pin "C32") (pinfunction "EPWM5A/CANTXB/ADCSOCAO/EQEP3S/SCITXDA/GPIO8_C32") (pintype "passive"))
    )
    (net (code "274") (name "unconnected-(C2000C-GPIO28{slash}SCIRXDA{slash}EM1CS4{slash}OUTPUTXBAR5{slash}EQEP3A{slash}SD2_D3-PadC16)") (class "Default")
      (node (ref "C2000") (pin "C16") (pinfunction "GPIO28/SCIRXDA/EM1CS4/OUTPUTXBAR5/EQEP3A/SD2_D3_C16") (pintype "passive"))
    )
    (net (code "275") (name "unconnected-(C2000C-GPIO29{slash}SCITXDA{slash}EM1SDCKE{slash}OUTPUTXBAR6{slash}EQEP3B{slash}SD2_C3-PadC18)") (class "Default")
      (node (ref "C2000") (pin "C18") (pinfunction "GPIO29/SCITXDA/EM1SDCKE/OUTPUTXBAR6/EQEP3B/SD2_C3_C18") (pintype "passive"))
    )
    (net (code "276") (name "unconnected-(C2000C-GPIO84{slash}SCITXDA{slash}MDXB{slash}MDXA-PadC42)") (class "Default")
      (node (ref "C2000") (pin "C42") (pinfunction "GPIO84/SCITXDA/MDXB/MDXA_C42") (pintype "passive"))
    )
    (net (code "277") (name "unconnected-(C2000C-GPIO108{slash}EM2A10-PadC56)") (class "Default")
      (node (ref "C2000") (pin "C56") (pinfunction "GPIO108/EM2A10_C56") (pintype "passive"))
    )
    (net (code "278") (name "unconnected-(C2000C-GPIO109{slash}EM2A11-PadC50)") (class "Default")
      (node (ref "C2000") (pin "C50") (pinfunction "GPIO109/EM2A11_C50") (pintype "passive"))
    )
    (net (code "279") (name "unconnected-(C2000C-~{EM2CS0}{slash}GPIO115-PadC58)") (class "Default")
      (node (ref "C2000") (pin "C58") (pinfunction "~{EM2CS0}/GPIO115_C58") (pintype "passive"))
    )
    (net (code "280") (name "unconnected-(C2000D-EM2CLK{slash}GPIO118-PadD49)") (class "Default")
      (node (ref "C2000") (pin "D49") (pinfunction "EM2CLK/GPIO118_D49") (pintype "passive"))
    )
    (net (code "281") (name "unconnected-(C2000D-EM2SDCKE{slash}GPIO117-PadD47)") (class "Default")
      (node (ref "C2000") (pin "D47") (pinfunction "EM2SDCKE/GPIO117_D47") (pintype "passive"))
    )
    (net (code "282") (name "unconnected-(C2000D-EPWM1A{slash}SDAA{slash}GPIO0-PadD14)") (class "Default")
      (node (ref "C2000") (pin "D14") (pinfunction "EPWM1A/SDAA/GPIO0_D14") (pintype "passive"))
    )
    (net (code "283") (name "unconnected-(C2000D-EPWM2A{slash}OUTPUTXBAR1{slash}SDAB{slash}GPIO2-PadD16)") (class "Default")
      (node (ref "C2000") (pin "D16") (pinfunction "EPWM2A/OUTPUTXBAR1/SDAB/GPIO2_D16") (pintype "passive"))
    )
    (net (code "284") (name "unconnected-(C2000D-EPWM4A{slash}OUTPUTXBAR4{slash}EPWMSYNC0{slash}EQEP3A{slash}CANTXB{slash}GPIO6-PadD18)") (class "Default")
      (node (ref "C2000") (pin "D18") (pinfunction "EPWM4A/OUTPUTXBAR4/EPWMSYNC0/EQEP3A/CANTXB/GPIO6_D18") (pintype "passive"))
    )
    (net (code "285") (name "unconnected-(C2000D-EPWM5B{slash}OUTPUTXBAR6{slash}EQEP3I{slash}SCITXDB{slash}SCIRXDA{slash}GPIO9-PadD20)") (class "Default")
      (node (ref "C2000") (pin "D20") (pinfunction "EPWM5B/OUTPUTXBAR6/EQEP3I/SCITXDB/SCIRXDA/GPIO9_D20") (pintype "passive"))
    )
    (net (code "286") (name "unconnected-(C2000D-EQEP1I{slash}EM1D31{slash}EM2D15{slash}~{SPISTEC}{slash}SD1_C3{slash}GPIO53-PadD59)") (class "Default")
      (node (ref "C2000") (pin "D59") (pinfunction "EQEP1I/EM1D31/EM2D15/~{SPISTEC}/SD1_C3/GPIO53_D59") (pintype "passive"))
    )
    (net (code "287") (name "unconnected-(C2000D-GPIO30{slash}CANRXA{slash}EM1CLK{slash}OUTPUTXBAR7{slash}EQEP3S{slash}SD2_D4-PadD46)") (class "Default")
      (node (ref "C2000") (pin "D46") (pinfunction "GPIO30/CANRXA/EM1CLK/OUTPUTXBAR7/EQEP3S/SD2_D4_D46") (pintype "passive"))
    )
    (net (code "288") (name "unconnected-(C2000D-GPIO31{slash}CANTXA{slash}~{EM1WE}{slash}OUTPUTXBAR8{slash}EQEP3I{slash}SD2_C4-PadD48)") (class "Default")
      (node (ref "C2000") (pin "D48") (pinfunction "GPIO31/CANTXA/~{EM1WE}/OUTPUTXBAR8/EQEP3I/SD2_C4_D48") (pintype "passive"))
    )
    (net (code "289") (name "unconnected-(C2000D-GPIO32{slash}SDAA{slash}~{EM1CS0}-PadD33)") (class "Default")
      (node (ref "C2000") (pin "D33") (pinfunction "GPIO32/SDAA/~{EM1CS0}_D33") (pintype "passive"))
    )
    (net (code "290") (name "unconnected-(C2000D-GPIO33{slash}SCLA{slash}EM1RNW-PadD31)") (class "Default")
      (node (ref "C2000") (pin "D31") (pinfunction "GPIO33/SCLA/EM1RNW_D31") (pintype "passive"))
    )
    (net (code "291") (name "unconnected-(C2000D-GPIO34{slash}OUTPUTXBAR1{slash}~{EM1CS2}{slash}SDAB-PadD50)") (class "Default")
      (node (ref "C2000") (pin "D50") (pinfunction "GPIO34/OUTPUTXBAR1/~{EM1CS2}/SDAB_D50") (pintype "passive"))
    )
    (net (code "292") (name "unconnected-(C2000D-GPIO35{slash}SCIRXDA{slash}~{EM1CS3}{slash}SCLB-PadD52)") (class "Default")
      (node (ref "C2000") (pin "D52") (pinfunction "GPIO35/SCIRXDA/~{EM1CS3}/SCLB_D52") (pintype "passive"))
    )
    (net (code "293") (name "unconnected-(C2000D-GPIO36{slash}SCITXDA{slash}EM1WAIT{slash}CANRXA-PadD54)") (class "Default")
      (node (ref "C2000") (pin "D54") (pinfunction "GPIO36/SCITXDA/EM1WAIT/CANRXA_D54") (pintype "passive"))
    )
    (net (code "294") (name "unconnected-(C2000D-GPIO37{slash}OUTPUTXBAR2{slash}~{EM1OE}{slash}CANTXA-PadD56)") (class "Default")
      (node (ref "C2000") (pin "D56") (pinfunction "GPIO37/OUTPUTXBAR2/~{EM1OE}/CANTXA_D56") (pintype "passive"))
    )
    (net (code "295") (name "unconnected-(C2000D-GPIO42{slash}SDAA{slash}SCITXDA{slash}USB0DM-PadD10)") (class "Default")
      (node (ref "C2000") (pin "D10") (pinfunction "GPIO42/SDAA/SCITXDA/USB0DM_D10") (pintype "passive"))
    )
    (net (code "296") (name "unconnected-(C2000D-GPIO43{slash}SCLA{slash}SCIRXDA{slash}USB0DP-PadD8)") (class "Default")
      (node (ref "C2000") (pin "D8") (pinfunction "GPIO43/SCLA/SCIRXDA/USB0DP_D8") (pintype "passive"))
    )
    (net (code "297") (name "unconnected-(C2000D-GPIO119{slash}EM2RNW-PadD51)") (class "Default")
      (node (ref "C2000") (pin "D51") (pinfunction "GPIO119/EM2RNW_D51") (pintype "passive"))
    )
    (net (code "298") (name "unconnected-(C2000D-GPIO120{slash}~{EM2WE}{slash}USB0PFLT-PadD4)") (class "Default")
      (node (ref "C2000") (pin "D4") (pinfunction "GPIO120/~{EM2WE}/USB0PFLT_D4") (pintype "passive"))
    )
    (net (code "299") (name "unconnected-(C2000D-GPIO121{slash}USB0EPEN{slash}~{EM2OE}-PadD2)") (class "Default")
      (node (ref "C2000") (pin "D2") (pinfunction "GPIO121/USB0EPEN/~{EM2OE}_D2") (pintype "passive"))
    )
    (net (code "300") (name "unconnected-(C2000D-GPIO126{slash}SD1_D3-PadD43)") (class "Default")
      (node (ref "C2000") (pin "D43") (pinfunction "GPIO126/SD1_D3_D43") (pintype "passive"))
    )
    (net (code "301") (name "unconnected-(C2000D-GPIO127{slash}SD1_C3-PadD39)") (class "Default")
      (node (ref "C2000") (pin "D39") (pinfunction "GPIO127/SD1_C3_D39") (pintype "passive"))
    )
    (net (code "302") (name "unconnected-(C2000D-GPIO128{slash}SD1_D4-PadD41)") (class "Default")
      (node (ref "C2000") (pin "D41") (pinfunction "GPIO128/SD1_D4_D41") (pintype "passive"))
    )
    (net (code "303") (name "unconnected-(C2000D-GPIO129{slash}SD1_C4-PadD45)") (class "Default")
      (node (ref "C2000") (pin "D45") (pinfunction "GPIO129/SD1_C4_D45") (pintype "passive"))
    )
    (net (code "304") (name "unconnected-(C2000D-GPIO130{slash}SD2_D1-PadD1)") (class "Default")
      (node (ref "C2000") (pin "D1") (pinfunction "GPIO130/SD2_D1_D1") (pintype "passive"))
    )
    (net (code "305") (name "unconnected-(C2000D-GPIO131{slash}SD2_C1-PadD3)") (class "Default")
      (node (ref "C2000") (pin "D3") (pinfunction "GPIO131/SD2_C1_D3") (pintype "passive"))
    )
    (net (code "306") (name "unconnected-(C2000D-GPIO132{slash}SD2_D2-PadD5)") (class "Default")
      (node (ref "C2000") (pin "D5") (pinfunction "GPIO132/SD2_D2_D5") (pintype "passive"))
    )
    (net (code "307") (name "unconnected-(C2000D-GPIO133{slash}AUXCLKIN{slash}SD2_C2-PadD7)") (class "Default")
      (node (ref "C2000") (pin "D7") (pinfunction "GPIO133/AUXCLKIN/SD2_C2_D7") (pintype "passive"))
    )
    (net (code "308") (name "unconnected-(C2000D-GPIO134{slash}SD2_D3-PadD9)") (class "Default")
      (node (ref "C2000") (pin "D9") (pinfunction "GPIO134/SD2_D3_D9") (pintype "passive"))
    )
    (net (code "309") (name "unconnected-(C2000D-GPIO137{slash}SD2_C4{slash}SCITXDB-PadD15)") (class "Default")
      (node (ref "C2000") (pin "D15") (pinfunction "GPIO137/SD2_C4/SCITXDB_D15") (pintype "passive"))
    )
    (net (code "310") (name "unconnected-(C2000D-GPIO138{slash}SCIRXDB-PadD53)") (class "Default")
      (node (ref "C2000") (pin "D53") (pinfunction "GPIO138/SCIRXDB_D53") (pintype "passive"))
    )
    (net (code "311") (name "unconnected-(C2000D-GPIO139{slash}SCIRXDC-PadD22)") (class "Default")
      (node (ref "C2000") (pin "D22") (pinfunction "GPIO139/SCIRXDC_D22") (pintype "passive"))
    )
    (net (code "312") (name "unconnected-(C2000D-GPIO140{slash}SCITXDC-PadD24)") (class "Default")
      (node (ref "C2000") (pin "D24") (pinfunction "GPIO140/SCITXDC_D24") (pintype "passive"))
    )
    (net (code "313") (name "unconnected-(C2000D-GPIO141{slash}SCIRXDD-PadD26)") (class "Default")
      (node (ref "C2000") (pin "D26") (pinfunction "GPIO141/SCIRXDD_D26") (pintype "passive"))
    )
    (net (code "314") (name "unconnected-(C2000D-MONITOR_1V2OUT-PadD40)") (class "Default")
      (node (ref "C2000") (pin "D40") (pinfunction "MONITOR_1V2OUT_D40") (pintype "passive"))
    )
    (net (code "315") (name "unconnected-(C2000D-SPISIMOA{slash}EM1D30{slash}EM2D14{slash}EQEP2A{slash}SCITXDB{slash}SD1_D4{slash}GPIO54-PadD57)") (class "Default")
      (node (ref "C2000") (pin "D57") (pinfunction "SPISIMOA/EM1D30/EM2D14/EQEP2A/SCITXDB/SD1_D4/GPIO54_D57") (pintype "passive"))
    )
    (net (code "316") (name "unconnected-(C2000D-SYS_RESET_OUTPUT-PadD32)") (class "Default")
      (node (ref "C2000") (pin "D32") (pinfunction "SYS_RESET_OUTPUT_D32") (pintype "passive"))
    )
    (net (code "317") (name "unconnected-(C2000D-~{EM2CS2}{slash}GPIO116-PadD37)") (class "Default")
      (node (ref "C2000") (pin "D37") (pinfunction "~{EM2CS2}/GPIO116_D37") (pintype "passive"))
    )
    (net (code "318") (name "unconnected-(CAM0-Pad12)") (class "Default")
      (node (ref "CAM0") (pin "12") (pinfunction "12_12") (pintype "passive"))
    )
    (net (code "319") (name "unconnected-(CAM1-Pad12)") (class "Default")
      (node (ref "CAM1") (pin "12") (pinfunction "12_12") (pintype "passive"))
    )
    (net (code "320") (name "unconnected-(CM4AA-AnalogIP0-Pad96)") (class "Default")
      (node (ref "CM4A") (pin "96") (pinfunction "AnalogIP0_96") (pintype "passive"))
    )
    (net (code "321") (name "unconnected-(CM4AA-AnalogIP1-Pad94)") (class "Default")
      (node (ref "CM4A") (pin "94") (pinfunction "AnalogIP1_94") (pintype "passive"))
    )
    (net (code "322") (name "unconnected-(CM4AA-BT_nDisable-Pad91)") (class "Default")
      (node (ref "CM4A") (pin "91") (pinfunction "BT_nDisable_91") (pintype "passive"))
    )
    (net (code "323") (name "unconnected-(CM4AA-CM4_1.8V(Output)-Pad88)") (class "Default")
      (node (ref "CM4A") (pin "88") (pinfunction "CM4_1.8V(Output)_88") (pintype "passive"))
    )
    (net (code "324") (name "unconnected-(CM4AA-CM4_1.8V(Output)-Pad90)") (class "Default")
      (node (ref "CM4A") (pin "90") (pinfunction "CM4_1.8V(Output)_90") (pintype "passive"))
    )
    (net (code "325") (name "unconnected-(CM4AA-EEPROM_nWP-Pad20)") (class "Default")
      (node (ref "CM4A") (pin "20") (pinfunction "EEPROM_nWP_20") (pintype "passive"))
    )
    (net (code "326") (name "unconnected-(CM4AA-Ethernet_Pair0_N-Pad10)") (class "Default")
      (node (ref "CM4A") (pin "10") (pinfunction "Ethernet_Pair0_N_10") (pintype "passive"))
    )
    (net (code "327") (name "unconnected-(CM4AA-Ethernet_Pair0_P-Pad12)") (class "Default")
      (node (ref "CM4A") (pin "12") (pinfunction "Ethernet_Pair0_P_12") (pintype "passive"))
    )
    (net (code "328") (name "unconnected-(CM4AA-Ethernet_Pair1_N-Pad6)") (class "Default")
      (node (ref "CM4A") (pin "6") (pinfunction "Ethernet_Pair1_N_6") (pintype "passive"))
    )
    (net (code "329") (name "unconnected-(CM4AA-Ethernet_Pair1_P-Pad4)") (class "Default")
      (node (ref "CM4A") (pin "4") (pinfunction "Ethernet_Pair1_P_4") (pintype "passive"))
    )
    (net (code "330") (name "unconnected-(CM4AA-Ethernet_Pair2_N-Pad9)") (class "Default")
      (node (ref "CM4A") (pin "9") (pinfunction "Ethernet_Pair2_N_9") (pintype "passive"))
    )
    (net (code "331") (name "unconnected-(CM4AA-Ethernet_Pair2_P-Pad11)") (class "Default")
      (node (ref "CM4A") (pin "11") (pinfunction "Ethernet_Pair2_P_11") (pintype "passive"))
    )
    (net (code "332") (name "unconnected-(CM4AA-Ethernet_Pair3_N-Pad5)") (class "Default")
      (node (ref "CM4A") (pin "5") (pinfunction "Ethernet_Pair3_N_5") (pintype "passive"))
    )
    (net (code "333") (name "unconnected-(CM4AA-Ethernet_Pair3_P-Pad3)") (class "Default")
      (node (ref "CM4A") (pin "3") (pinfunction "Ethernet_Pair3_P_3") (pintype "passive"))
    )
    (net (code "334") (name "unconnected-(CM4AA-Ethernet_SYNC_IN-Pad16)") (class "Default")
      (node (ref "CM4A") (pin "16") (pinfunction "Ethernet_SYNC_IN_16") (pintype "passive"))
    )
    (net (code "335") (name "unconnected-(CM4AA-Ethernet_SYNC_OUT-Pad18)") (class "Default")
      (node (ref "CM4A") (pin "18") (pinfunction "Ethernet_SYNC_OUT_18") (pintype "passive"))
    )
    (net (code "336") (name "unconnected-(CM4AA-Ethernet_nLED1-Pad19)") (class "Default")
      (node (ref "CM4A") (pin "19") (pinfunction "Ethernet_nLED1_19") (pintype "passive"))
    )
    (net (code "337") (name "unconnected-(CM4AA-Ethernet_nLED2-Pad17)") (class "Default")
      (node (ref "CM4A") (pin "17") (pinfunction "Ethernet_nLED2_17") (pintype "passive"))
    )
    (net (code "338") (name "unconnected-(CM4AA-Ethernet_nLED3-Pad15)") (class "Default")
      (node (ref "CM4A") (pin "15") (pinfunction "Ethernet_nLED3_15") (pintype "passive"))
    )
    (net (code "339") (name "unconnected-(CM4AA-GLOBAL_EN-Pad99)") (class "Default")
      (node (ref "CM4A") (pin "99") (pinfunction "GLOBAL_EN_99") (pintype "passive"))
    )
    (net (code "340") (name "unconnected-(CM4AA-GPIO4-Pad54)") (class "Default")
      (node (ref "CM4A") (pin "54") (pinfunction "GPIO4_54") (pintype "passive"))
    )
    (net (code "341") (name "unconnected-(CM4AA-GPIO5-Pad34)") (class "Default")
      (node (ref "CM4A") (pin "34") (pinfunction "GPIO5_34") (pintype "passive"))
    )
    (net (code "342") (name "unconnected-(CM4AA-GPIO6-Pad30)") (class "Default")
      (node (ref "CM4A") (pin "30") (pinfunction "GPIO6_30") (pintype "passive"))
    )
    (net (code "343") (name "unconnected-(CM4AA-GPIO7-Pad37)") (class "Default")
      (node (ref "CM4A") (pin "37") (pinfunction "GPIO7_37") (pintype "passive"))
    )
    (net (code "344") (name "unconnected-(CM4AA-GPIO12-Pad31)") (class "Default")
      (node (ref "CM4A") (pin "31") (pinfunction "GPIO12_31") (pintype "passive"))
    )
    (net (code "345") (name "unconnected-(CM4AA-GPIO13-Pad28)") (class "Default")
      (node (ref "CM4A") (pin "28") (pinfunction "GPIO13_28") (pintype "passive"))
    )
    (net (code "346") (name "unconnected-(CM4AA-GPIO16-Pad29)") (class "Default")
      (node (ref "CM4A") (pin "29") (pinfunction "GPIO16_29") (pintype "passive"))
    )
    (net (code "347") (name "unconnected-(CM4AA-GPIO17-Pad50)") (class "Default")
      (node (ref "CM4A") (pin "50") (pinfunction "GPIO17_50") (pintype "passive"))
    )
    (net (code "348") (name "unconnected-(CM4AA-GPIO18-Pad49)") (class "Default")
      (node (ref "CM4A") (pin "49") (pinfunction "GPIO18_49") (pintype "passive"))
    )
    (net (code "349") (name "unconnected-(CM4AA-GPIO19-Pad26)") (class "Default")
      (node (ref "CM4A") (pin "26") (pinfunction "GPIO19_26") (pintype "passive"))
    )
    (net (code "350") (name "unconnected-(CM4AA-GPIO20-Pad27)") (class "Default")
      (node (ref "CM4A") (pin "27") (pinfunction "GPIO20_27") (pintype "passive"))
    )
    (net (code "351") (name "unconnected-(CM4AA-GPIO21-Pad25)") (class "Default")
      (node (ref "CM4A") (pin "25") (pinfunction "GPIO21_25") (pintype "passive"))
    )
    (net (code "352") (name "unconnected-(CM4AA-GPIO22-Pad46)") (class "Default")
      (node (ref "CM4A") (pin "46") (pinfunction "GPIO22_46") (pintype "passive"))
    )
    (net (code "353") (name "unconnected-(CM4AA-GPIO23-Pad47)") (class "Default")
      (node (ref "CM4A") (pin "47") (pinfunction "GPIO23_47") (pintype "passive"))
    )
    (net (code "354") (name "unconnected-(CM4AA-GPIO24-Pad45)") (class "Default")
      (node (ref "CM4A") (pin "45") (pinfunction "GPIO24_45") (pintype "passive"))
    )
    (net (code "355") (name "unconnected-(CM4AA-GPIO25-Pad41)") (class "Default")
      (node (ref "CM4A") (pin "41") (pinfunction "GPIO25_41") (pintype "passive"))
    )
    (net (code "356") (name "unconnected-(CM4AA-GPIO26-Pad24)") (class "Default")
      (node (ref "CM4A") (pin "24") (pinfunction "GPIO26_24") (pintype "passive"))
    )
    (net (code "357") (name "unconnected-(CM4AA-GPIO27-Pad48)") (class "Default")
      (node (ref "CM4A") (pin "48") (pinfunction "GPIO27_48") (pintype "passive"))
    )
    (net (code "358") (name "unconnected-(CM4AA-RUN_PG-Pad92)") (class "Default")
      (node (ref "CM4A") (pin "92") (pinfunction "RUN_PG_92") (pintype "passive"))
    )
    (net (code "359") (name "unconnected-(CM4AA-Reserved-Pad76)") (class "Default")
      (node (ref "CM4A") (pin "76") (pinfunction "Reserved_76") (pintype "passive"))
    )
    (net (code "360") (name "unconnected-(CM4AA-SD_DAT4-Pad68)") (class "Default")
      (node (ref "CM4A") (pin "68") (pinfunction "SD_DAT4_68") (pintype "passive"))
    )
    (net (code "361") (name "unconnected-(CM4AA-SD_DAT5-Pad64)") (class "Default")
      (node (ref "CM4A") (pin "64") (pinfunction "SD_DAT5_64") (pintype "passive"))
    )
    (net (code "362") (name "unconnected-(CM4AA-SD_DAT6-Pad72)") (class "Default")
      (node (ref "CM4A") (pin "72") (pinfunction "SD_DAT6_72") (pintype "passive"))
    )
    (net (code "363") (name "unconnected-(CM4AA-SD_DAT7-Pad70)") (class "Default")
      (node (ref "CM4A") (pin "70") (pinfunction "SD_DAT7_70") (pintype "passive"))
    )
    (net (code "364") (name "unconnected-(CM4AA-SD_PWR_ON-Pad75)") (class "Default")
      (node (ref "CM4A") (pin "75") (pinfunction "SD_PWR_ON_75") (pintype "passive"))
    )
    (net (code "365") (name "unconnected-(CM4AA-SD_VDD_Override-Pad73)") (class "Default")
      (node (ref "CM4A") (pin "73") (pinfunction "SD_VDD_Override_73") (pintype "passive"))
    )
    (net (code "366") (name "unconnected-(CM4AA-WL_nDisable-Pad89)") (class "Default")
      (node (ref "CM4A") (pin "89") (pinfunction "WL_nDisable_89") (pintype "passive"))
    )
    (net (code "367") (name "unconnected-(CM4AA-nRPIBOUT-Pad93)") (class "Default")
      (node (ref "CM4A") (pin "93") (pinfunction "nRPIBOUT_93") (pintype "passive"))
    )
    (net (code "368") (name "unconnected-(CM4AB-CAM1_D2_N-Pad133)") (class "Default")
      (node (ref "CM4A") (pin "133") (pinfunction "CAM1_D2_N_133") (pintype "passive"))
    )
    (net (code "369") (name "unconnected-(CM4AB-CAM1_D2_P-Pad135)") (class "Default")
      (node (ref "CM4A") (pin "135") (pinfunction "CAM1_D2_P_135") (pintype "passive"))
    )
    (net (code "370") (name "unconnected-(CM4AB-CAM1_D3_N-Pad139)") (class "Default")
      (node (ref "CM4A") (pin "139") (pinfunction "CAM1_D3_N_139") (pintype "passive"))
    )
    (net (code "371") (name "unconnected-(CM4AB-CAM1_D3_P-Pad141)") (class "Default")
      (node (ref "CM4A") (pin "141") (pinfunction "CAM1_D3_P_141") (pintype "passive"))
    )
    (net (code "372") (name "unconnected-(CM4AB-DSI0_C_N-Pad169)") (class "Default")
      (node (ref "CM4A") (pin "169") (pinfunction "DSI0_C_N_169") (pintype "passive"))
    )
    (net (code "373") (name "unconnected-(CM4AB-DSI0_C_P-Pad171)") (class "Default")
      (node (ref "CM4A") (pin "171") (pinfunction "DSI0_C_P_171") (pintype "passive"))
    )
    (net (code "374") (name "unconnected-(CM4AB-DSI0_D0_N-Pad157)") (class "Default")
      (node (ref "CM4A") (pin "157") (pinfunction "DSI0_D0_N_157") (pintype "passive"))
    )
    (net (code "375") (name "unconnected-(CM4AB-DSI0_D0_P-Pad159)") (class "Default")
      (node (ref "CM4A") (pin "159") (pinfunction "DSI0_D0_P_159") (pintype "passive"))
    )
    (net (code "376") (name "unconnected-(CM4AB-DSI0_D1_N-Pad163)") (class "Default")
      (node (ref "CM4A") (pin "163") (pinfunction "DSI0_D1_N_163") (pintype "passive"))
    )
    (net (code "377") (name "unconnected-(CM4AB-DSI0_D1_P-Pad165)") (class "Default")
      (node (ref "CM4A") (pin "165") (pinfunction "DSI0_D1_P_165") (pintype "passive"))
    )
    (net (code "378") (name "unconnected-(CM4AB-DSI1_C_N-Pad187)") (class "Default")
      (node (ref "CM4A") (pin "187") (pinfunction "DSI1_C_N_187") (pintype "passive"))
    )
    (net (code "379") (name "unconnected-(CM4AB-DSI1_C_P-Pad189)") (class "Default")
      (node (ref "CM4A") (pin "189") (pinfunction "DSI1_C_P_189") (pintype "passive"))
    )
    (net (code "380") (name "unconnected-(CM4AB-DSI1_D0_N-Pad175)") (class "Default")
      (node (ref "CM4A") (pin "175") (pinfunction "DSI1_D0_N_175") (pintype "passive"))
    )
    (net (code "381") (name "unconnected-(CM4AB-DSI1_D0_P-Pad177)") (class "Default")
      (node (ref "CM4A") (pin "177") (pinfunction "DSI1_D0_P_177") (pintype "passive"))
    )
    (net (code "382") (name "unconnected-(CM4AB-DSI1_D1_N-Pad181)") (class "Default")
      (node (ref "CM4A") (pin "181") (pinfunction "DSI1_D1_N_181") (pintype "passive"))
    )
    (net (code "383") (name "unconnected-(CM4AB-DSI1_D1_P-Pad183)") (class "Default")
      (node (ref "CM4A") (pin "183") (pinfunction "DSI1_D1_P_183") (pintype "passive"))
    )
    (net (code "384") (name "unconnected-(CM4AB-DSI1_D2_N-Pad193)") (class "Default")
      (node (ref "CM4A") (pin "193") (pinfunction "DSI1_D2_N_193") (pintype "passive"))
    )
    (net (code "385") (name "unconnected-(CM4AB-DSI1_D2_P-Pad195)") (class "Default")
      (node (ref "CM4A") (pin "195") (pinfunction "DSI1_D2_P_195") (pintype "passive"))
    )
    (net (code "386") (name "unconnected-(CM4AB-DSI1_D3_N-Pad194)") (class "Default")
      (node (ref "CM4A") (pin "194") (pinfunction "DSI1_D3_N_194") (pintype "passive"))
    )
    (net (code "387") (name "unconnected-(CM4AB-DSI1_D3_P-Pad196)") (class "Default")
      (node (ref "CM4A") (pin "196") (pinfunction "DSI1_D3_P_196") (pintype "passive"))
    )
    (net (code "388") (name "unconnected-(CM4AB-HDMI1_CEC-Pad149)") (class "Default")
      (node (ref "CM4A") (pin "149") (pinfunction "HDMI1_CEC_149") (pintype "passive"))
    )
    (net (code "389") (name "unconnected-(CM4AB-HDMI1_CLK_N-Pad166)") (class "Default")
      (node (ref "CM4A") (pin "166") (pinfunction "HDMI1_CLK_N_166") (pintype "passive"))
    )
    (net (code "390") (name "unconnected-(CM4AB-HDMI1_CLK_P-Pad164)") (class "Default")
      (node (ref "CM4A") (pin "164") (pinfunction "HDMI1_CLK_P_164") (pintype "passive"))
    )
    (net (code "391") (name "unconnected-(CM4AB-HDMI1_HOTPLUG-Pad143)") (class "Default")
      (node (ref "CM4A") (pin "143") (pinfunction "HDMI1_HOTPLUG_143") (pintype "passive"))
    )
    (net (code "392") (name "unconnected-(CM4AB-HDMI1_SCL-Pad147)") (class "Default")
      (node (ref "CM4A") (pin "147") (pinfunction "HDMI1_SCL_147") (pintype "passive"))
    )
    (net (code "393") (name "unconnected-(CM4AB-HDMI1_SDA-Pad145)") (class "Default")
      (node (ref "CM4A") (pin "145") (pinfunction "HDMI1_SDA_145") (pintype "passive"))
    )
    (net (code "394") (name "unconnected-(CM4AB-HDMI1_TX0_N-Pad160)") (class "Default")
      (node (ref "CM4A") (pin "160") (pinfunction "HDMI1_TX0_N_160") (pintype "passive"))
    )
    (net (code "395") (name "unconnected-(CM4AB-HDMI1_TX0_P-Pad158)") (class "Default")
      (node (ref "CM4A") (pin "158") (pinfunction "HDMI1_TX0_P_158") (pintype "passive"))
    )
    (net (code "396") (name "unconnected-(CM4AB-HDMI1_TX1_N-Pad154)") (class "Default")
      (node (ref "CM4A") (pin "154") (pinfunction "HDMI1_TX1_N_154") (pintype "passive"))
    )
    (net (code "397") (name "unconnected-(CM4AB-HDMI1_TX1_P-Pad152)") (class "Default")
      (node (ref "CM4A") (pin "152") (pinfunction "HDMI1_TX1_P_152") (pintype "passive"))
    )
    (net (code "398") (name "unconnected-(CM4AB-HDMI1_TX2_N-Pad148)") (class "Default")
      (node (ref "CM4A") (pin "148") (pinfunction "HDMI1_TX2_N_148") (pintype "passive"))
    )
    (net (code "399") (name "unconnected-(CM4AB-HDMI1_TX2_P-Pad146)") (class "Default")
      (node (ref "CM4A") (pin "146") (pinfunction "HDMI1_TX2_P_146") (pintype "passive"))
    )
    (net (code "400") (name "unconnected-(CM4AB-PCIe_CLK_N-Pad112)") (class "Default")
      (node (ref "CM4A") (pin "112") (pinfunction "PCIe_CLK_N_112") (pintype "passive"))
    )
    (net (code "401") (name "unconnected-(CM4AB-PCIe_CLK_P-Pad110)") (class "Default")
      (node (ref "CM4A") (pin "110") (pinfunction "PCIe_CLK_P_110") (pintype "passive"))
    )
    (net (code "402") (name "unconnected-(CM4AB-PCIe_CLK_nREQ-Pad102)") (class "Default")
      (node (ref "CM4A") (pin "102") (pinfunction "PCIe_CLK_nREQ_102") (pintype "passive"))
    )
    (net (code "403") (name "unconnected-(CM4AB-PCIe_RX_N-Pad118)") (class "Default")
      (node (ref "CM4A") (pin "118") (pinfunction "PCIe_RX_N_118") (pintype "passive"))
    )
    (net (code "404") (name "unconnected-(CM4AB-PCIe_RX_P-Pad116)") (class "Default")
      (node (ref "CM4A") (pin "116") (pinfunction "PCIe_RX_P_116") (pintype "passive"))
    )
    (net (code "405") (name "unconnected-(CM4AB-PCIe_TX_N-Pad124)") (class "Default")
      (node (ref "CM4A") (pin "124") (pinfunction "PCIe_TX_N_124") (pintype "passive"))
    )
    (net (code "406") (name "unconnected-(CM4AB-PCIe_TX_P-Pad122)") (class "Default")
      (node (ref "CM4A") (pin "122") (pinfunction "PCIe_TX_P_122") (pintype "passive"))
    )
    (net (code "407") (name "unconnected-(CM4AB-PCIe_nRST-Pad109)") (class "Default")
      (node (ref "CM4A") (pin "109") (pinfunction "PCIe_nRST_109") (pintype "passive"))
    )
    (net (code "408") (name "unconnected-(CM4AB-Reserved-Pad104)") (class "Default")
      (node (ref "CM4A") (pin "104") (pinfunction "Reserved_104") (pintype "passive"))
    )
    (net (code "409") (name "unconnected-(CM4AB-Reserved-Pad106)") (class "Default")
      (node (ref "CM4A") (pin "106") (pinfunction "Reserved_106") (pintype "passive"))
    )
    (net (code "410") (name "unconnected-(CM4AB-USB_OTG_ID-Pad101)") (class "Default")
      (node (ref "CM4A") (pin "101") (pinfunction "USB_OTG_ID_101") (pintype "passive"))
    )
    (net (code "411") (name "unconnected-(CM4AB-VDAC_COMP-Pad111)") (class "Default")
      (node (ref "CM4A") (pin "111") (pinfunction "VDAC_COMP_111") (pintype "passive"))
    )
    (net (code "412") (name "unconnected-(HDMI-NC-Pad0)") (class "Default")
      (node (ref "HDMI") (pin "0") (pinfunction "NC_0") (pintype "passive"))
    )
    (net (code "413") (name "unconnected-(HDMI-NC-Pad14)") (class "Default")
      (node (ref "HDMI") (pin "14") (pinfunction "NC_14") (pintype "passive"))
    )
    (net (code "414") (name "unconnected-(SD-K-Pad9)") (class "Default")
      (node (ref "SD") (pin "9") (pinfunction "K_9") (pintype "passive"))
    )
    (net (code "415") (name "unconnected-(TYPE-C-CC1-PadA5)") (class "Default")
      (node (ref "TYPE-C") (pin "A5") (pinfunction "CC1_A5") (pintype "passive"))
    )
    (net (code "416") (name "unconnected-(TYPE-C-CC2-PadB5)") (class "Default")
      (node (ref "TYPE-C") (pin "B5") (pinfunction "CC2_B5") (pintype "passive"))
    )
    (net (code "417") (name "unconnected-(USBHUNB4-CRFILT-Pad14)") (class "Default")
      (node (ref "USBHUNB4") (pin "14") (pinfunction "CRFILT_14") (pintype "passive"))
    )
    (net (code "418") (name "unconnected-(USBHUNB4-PLL-Pad34)") (class "Default")
      (node (ref "USBHUNB4") (pin "34") (pinfunction "PLL_34") (pintype "passive"))
    )
    (net (code "419") (name "unconnected-(USBHUNB4-PWR2-Pad16)") (class "Default")
      (node (ref "USBHUNB4") (pin "16") (pinfunction "PWR2_16") (pintype "passive"))
    )
    (net (code "420") (name "unconnected-(USBHUNB4-PWR3-Pad18)") (class "Default")
      (node (ref "USBHUNB4") (pin "18") (pinfunction "PWR3_18") (pintype "passive"))
    )
    (net (code "421") (name "unconnected-(USBHUNB4-PWR4-Pad20)") (class "Default")
      (node (ref "USBHUNB4") (pin "20") (pinfunction "PWR4_20") (pintype "passive"))
    )
    (net (code "422") (name "unconnected-(USBHUNB4-TEST-Pad11)") (class "Default")
      (node (ref "USBHUNB4") (pin "11") (pinfunction "TEST_11") (pintype "passive"))
    )
  )
)
